# Blade.net
KiCad netlist of a schematic drawn in EAGLE
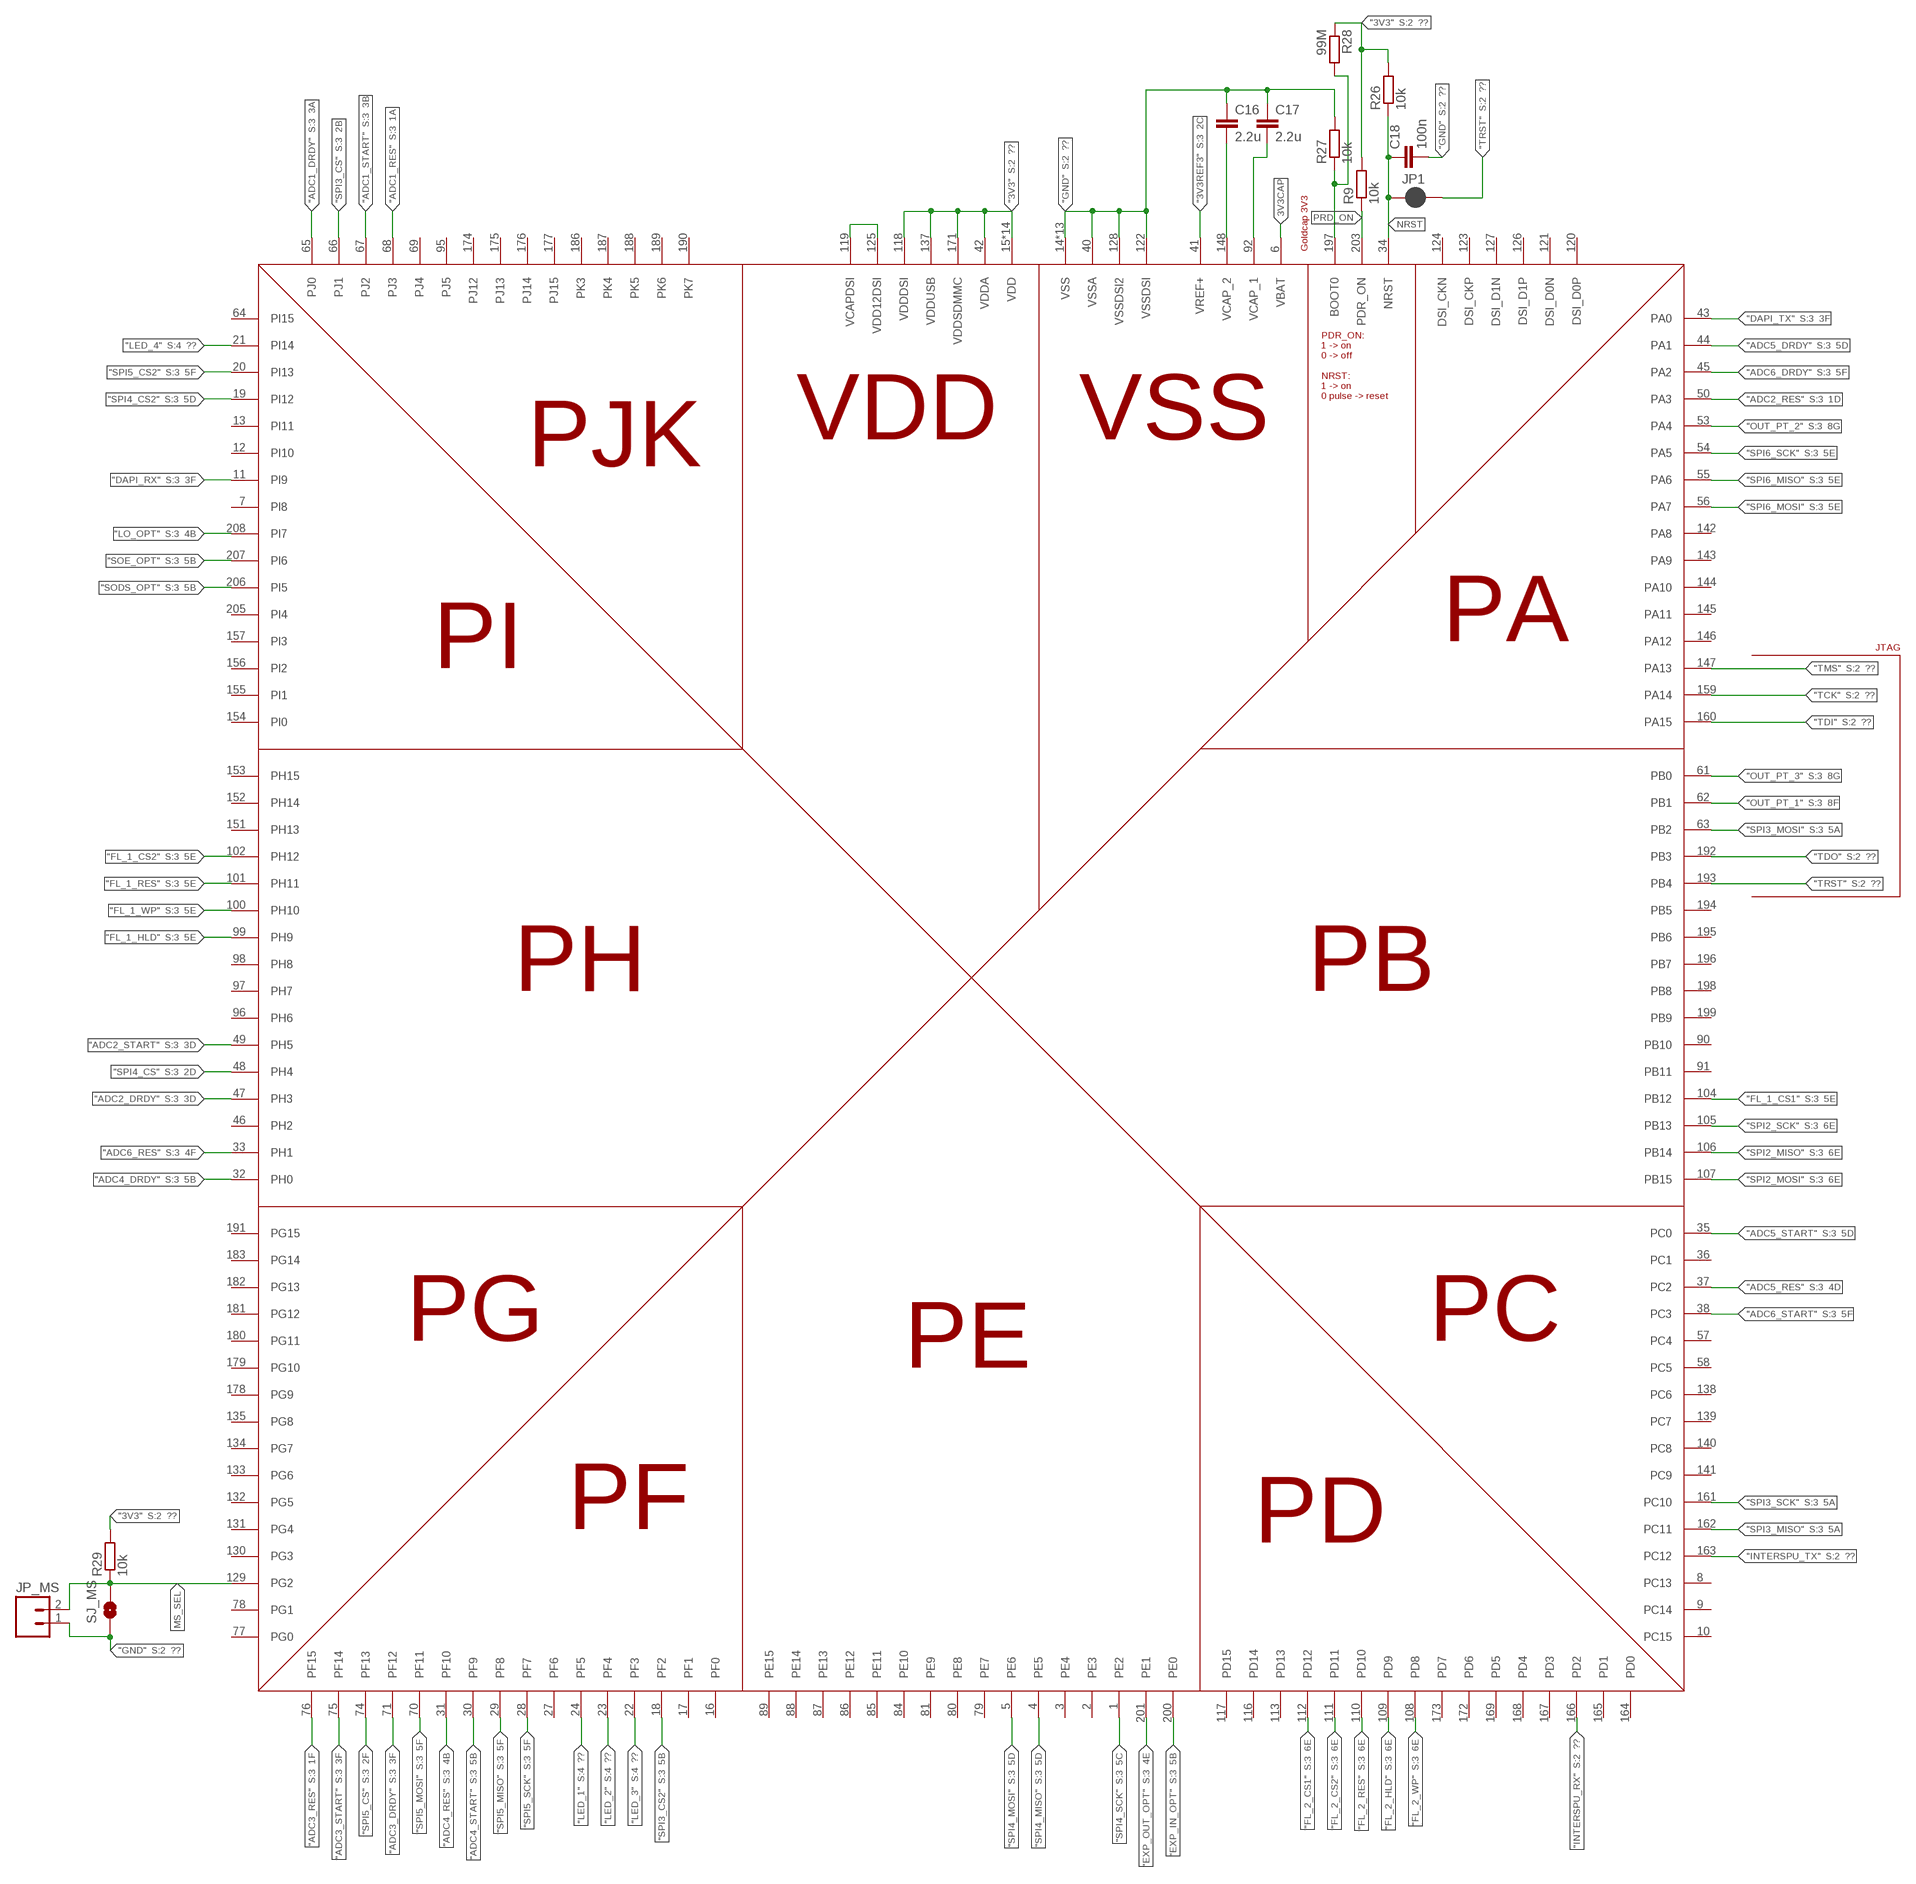
[diagram p0: schematic, sheet 1]
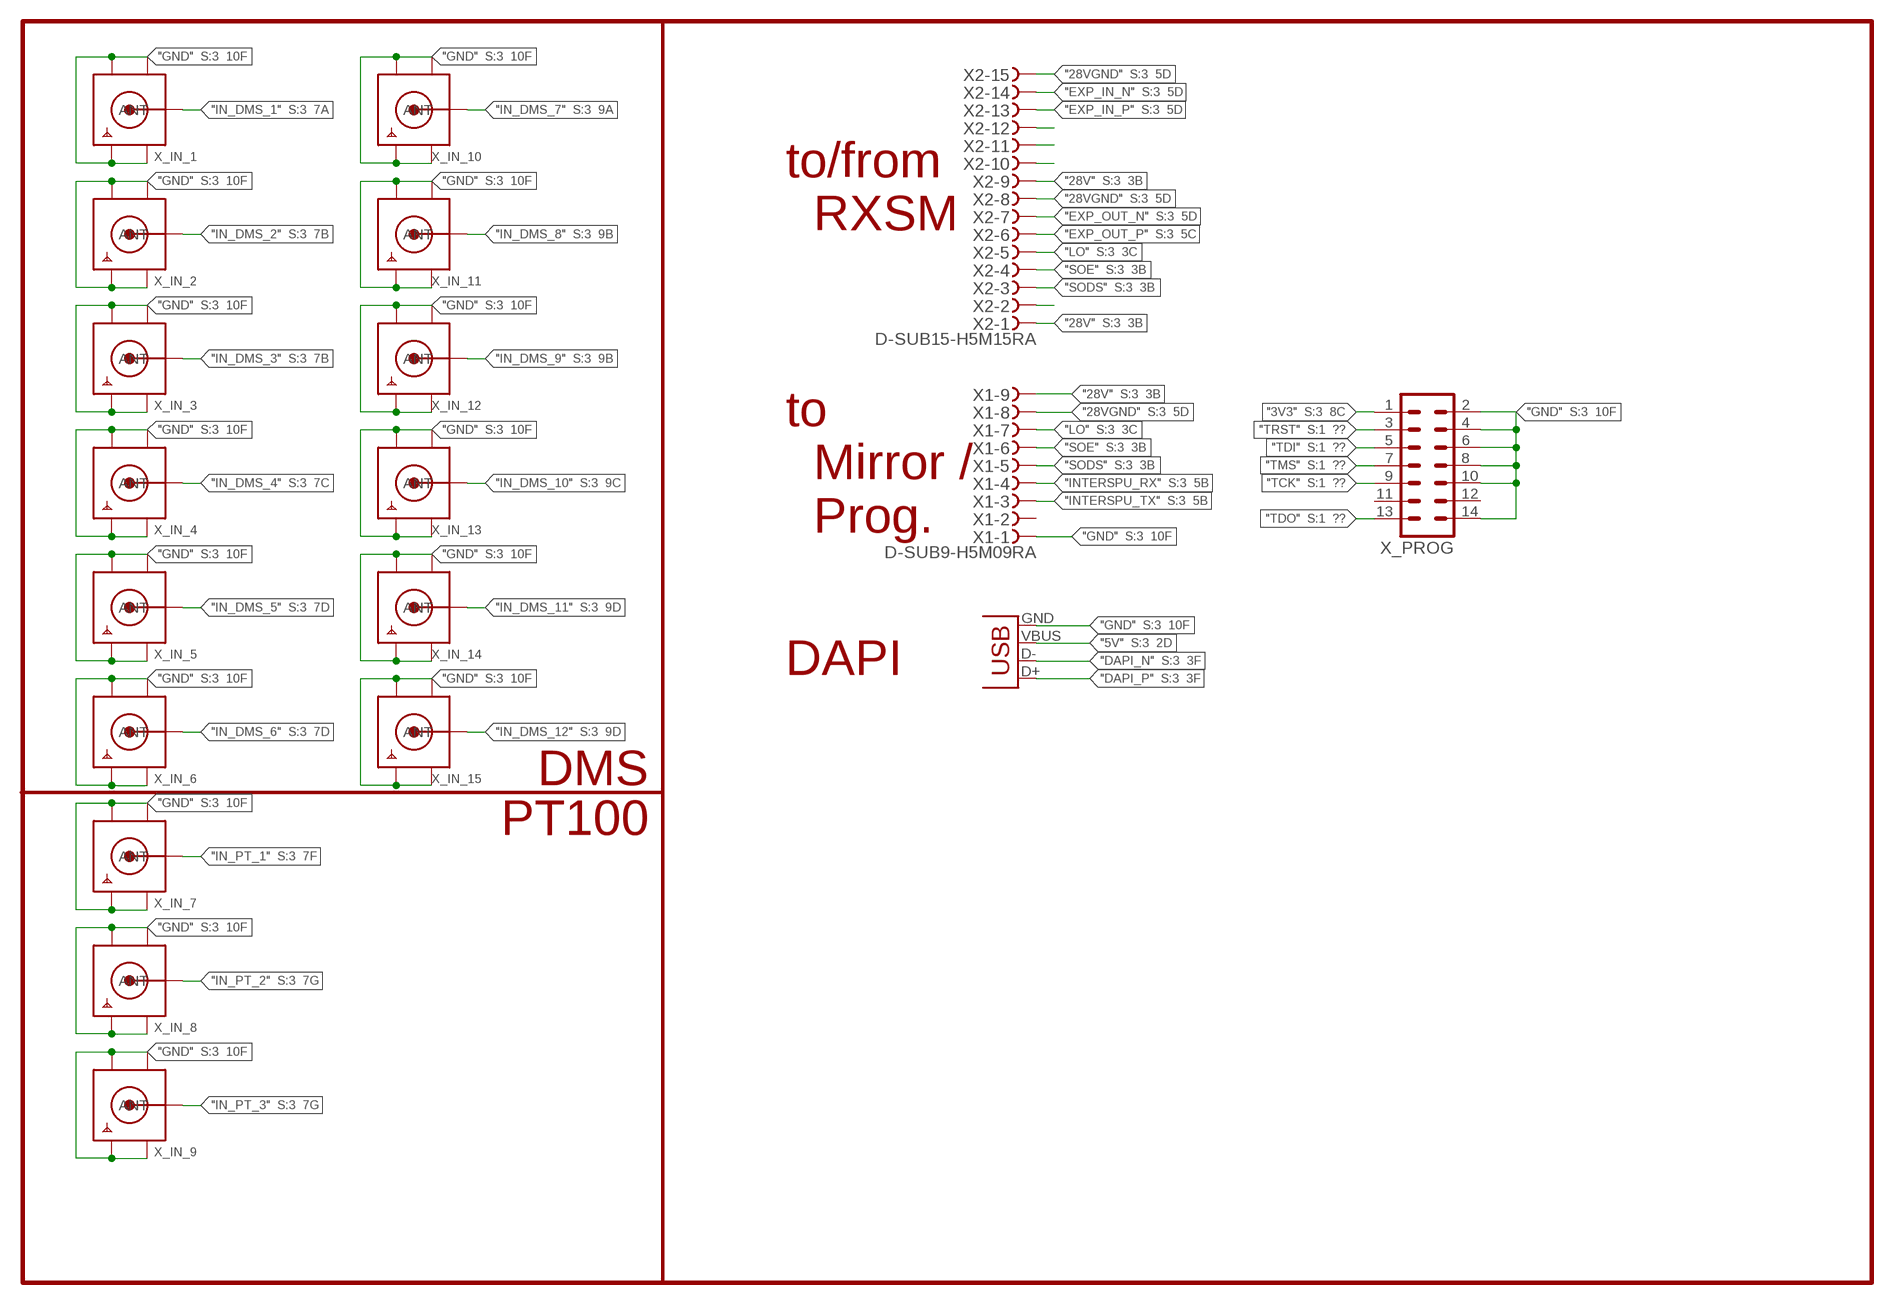
[diagram p1: schematic, sheet 2]
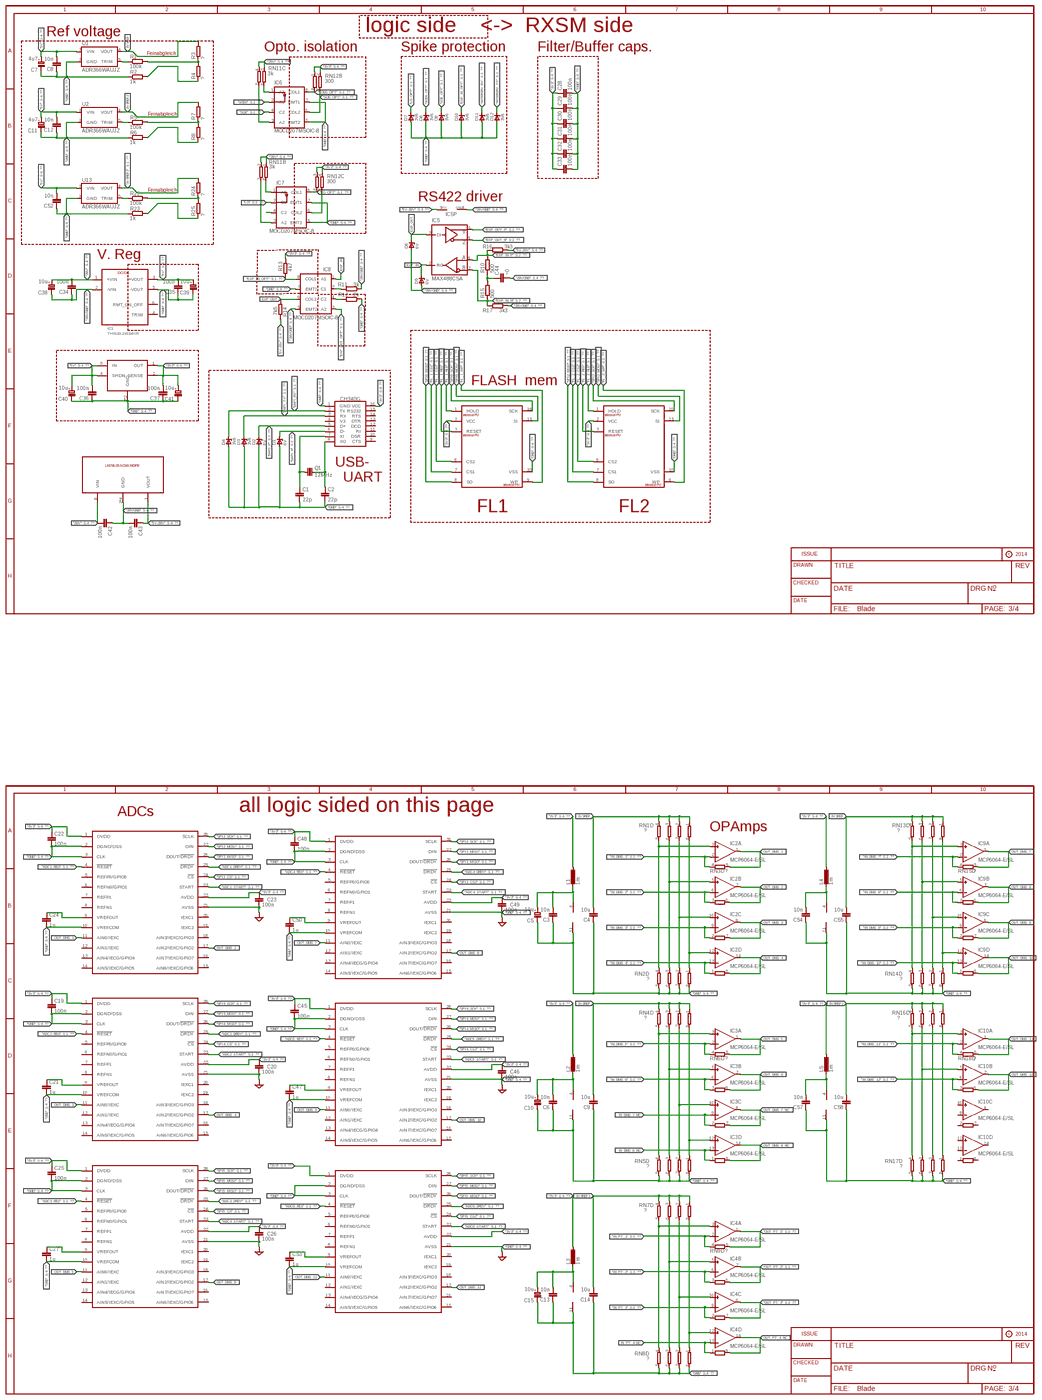
[diagram p2: schematic, sheet 3, overview]
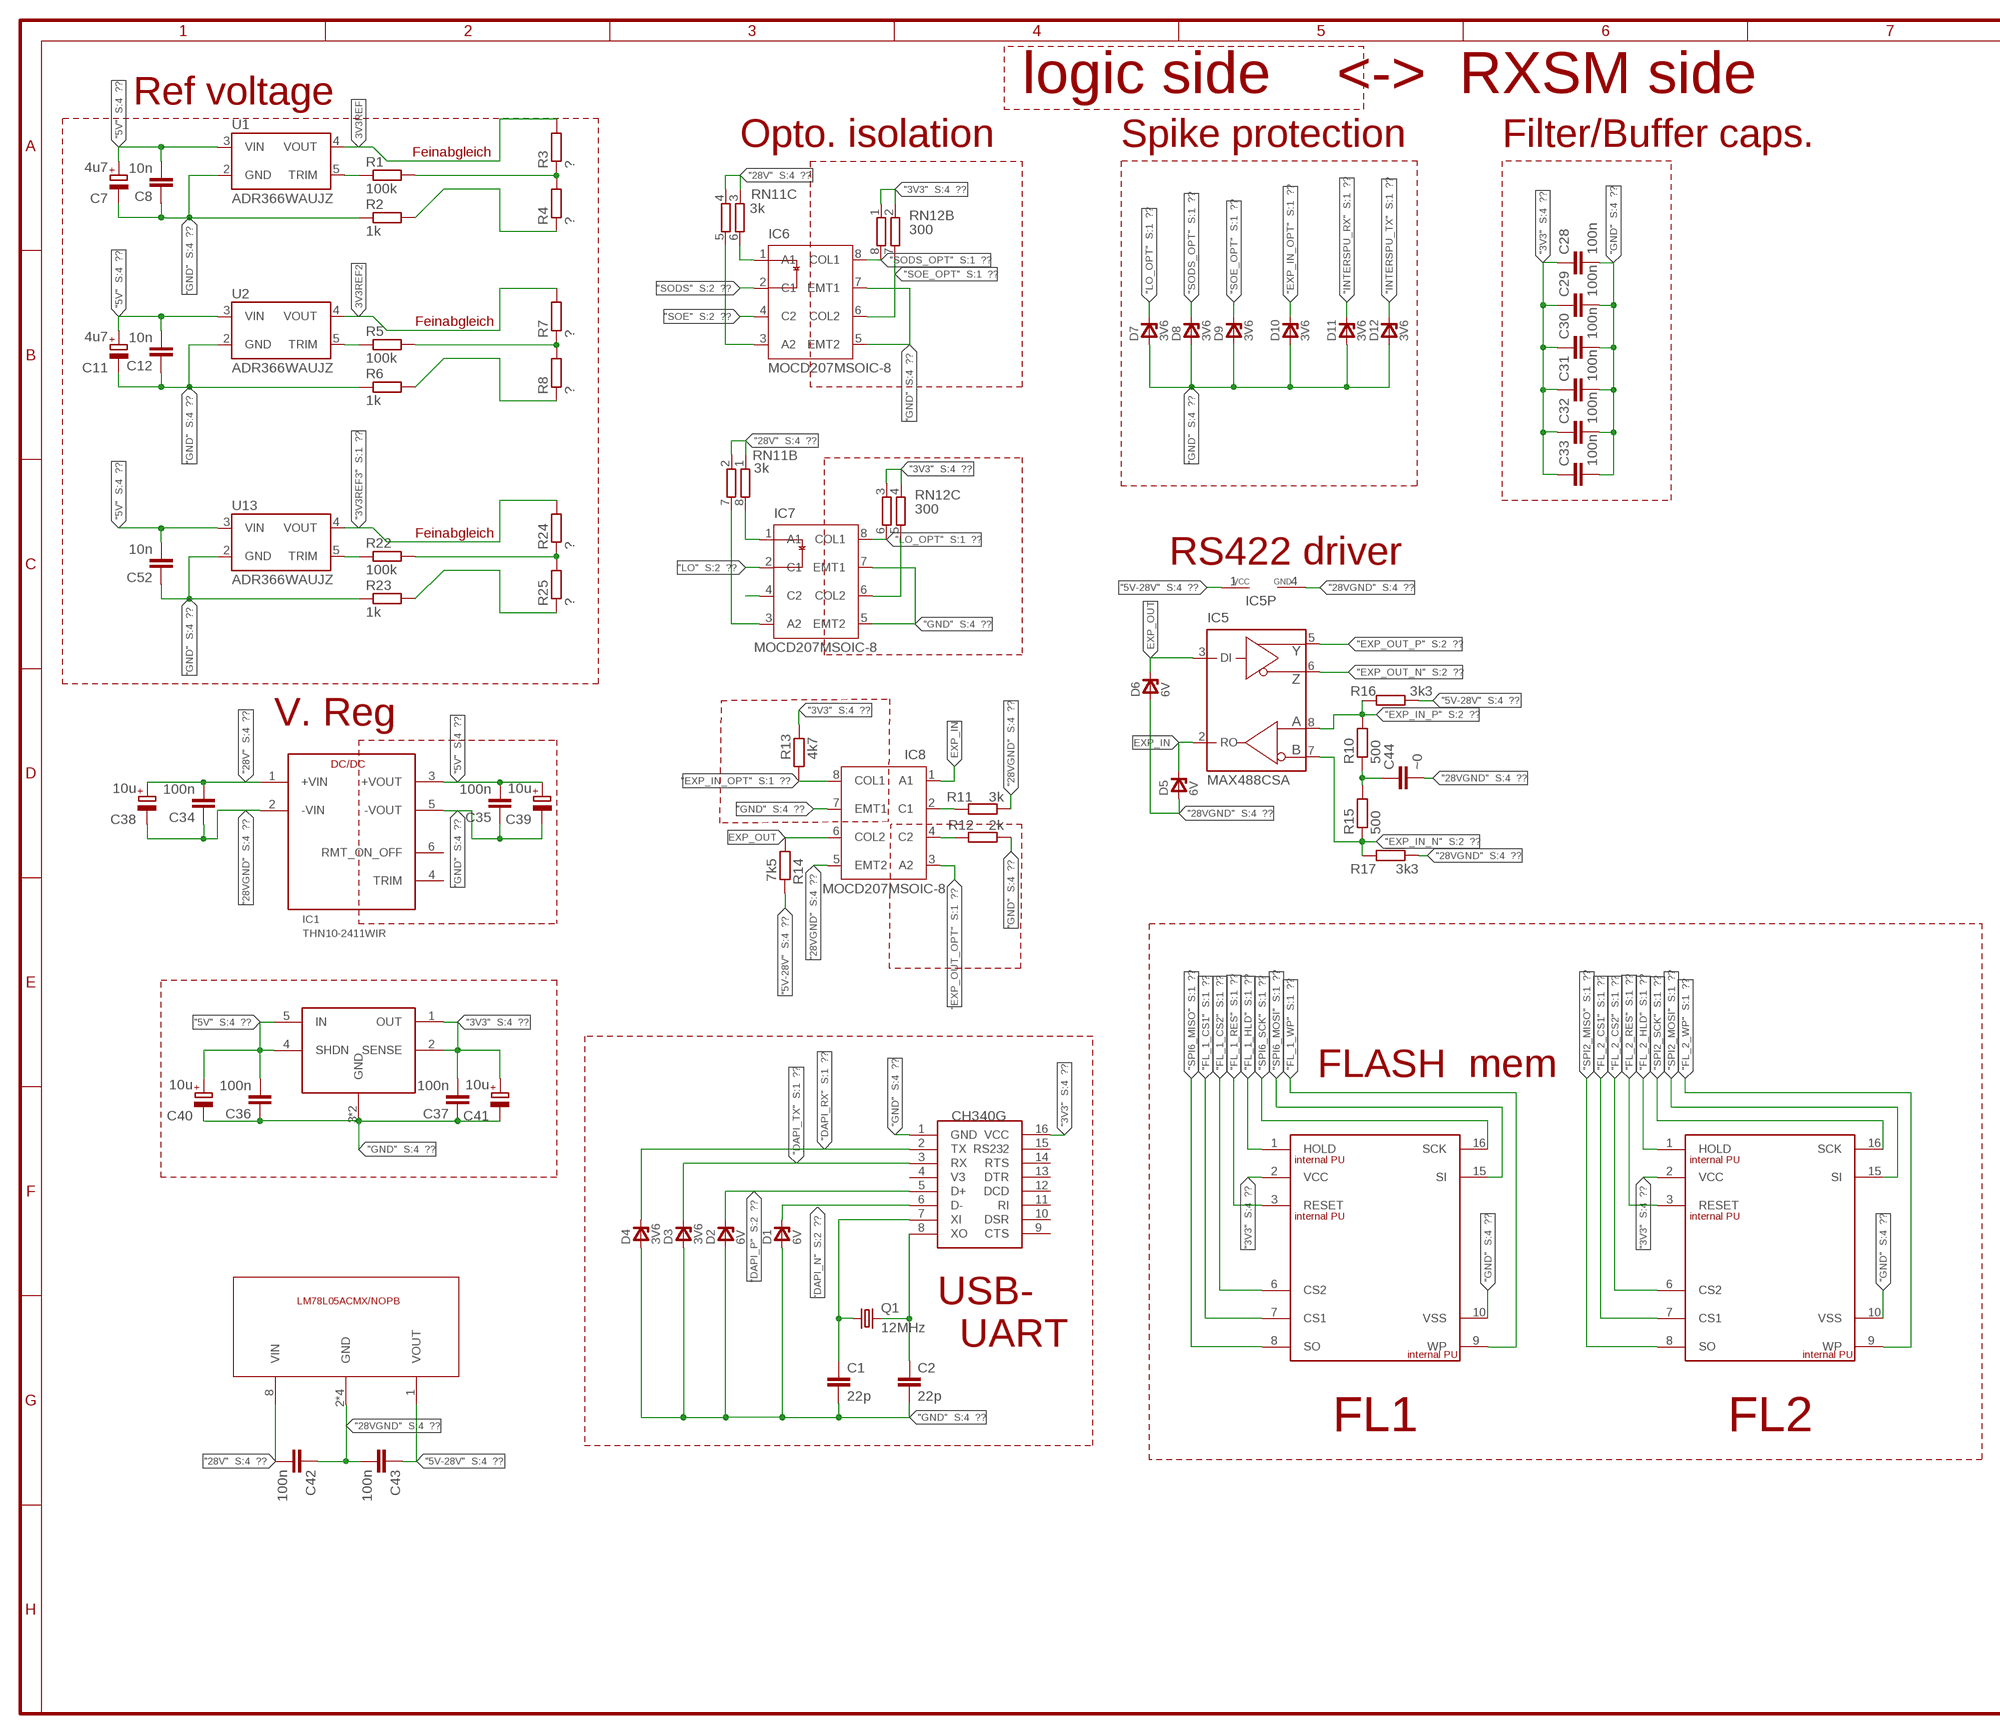
[diagram p3: schematic, sheet 3, part 1 of 4]
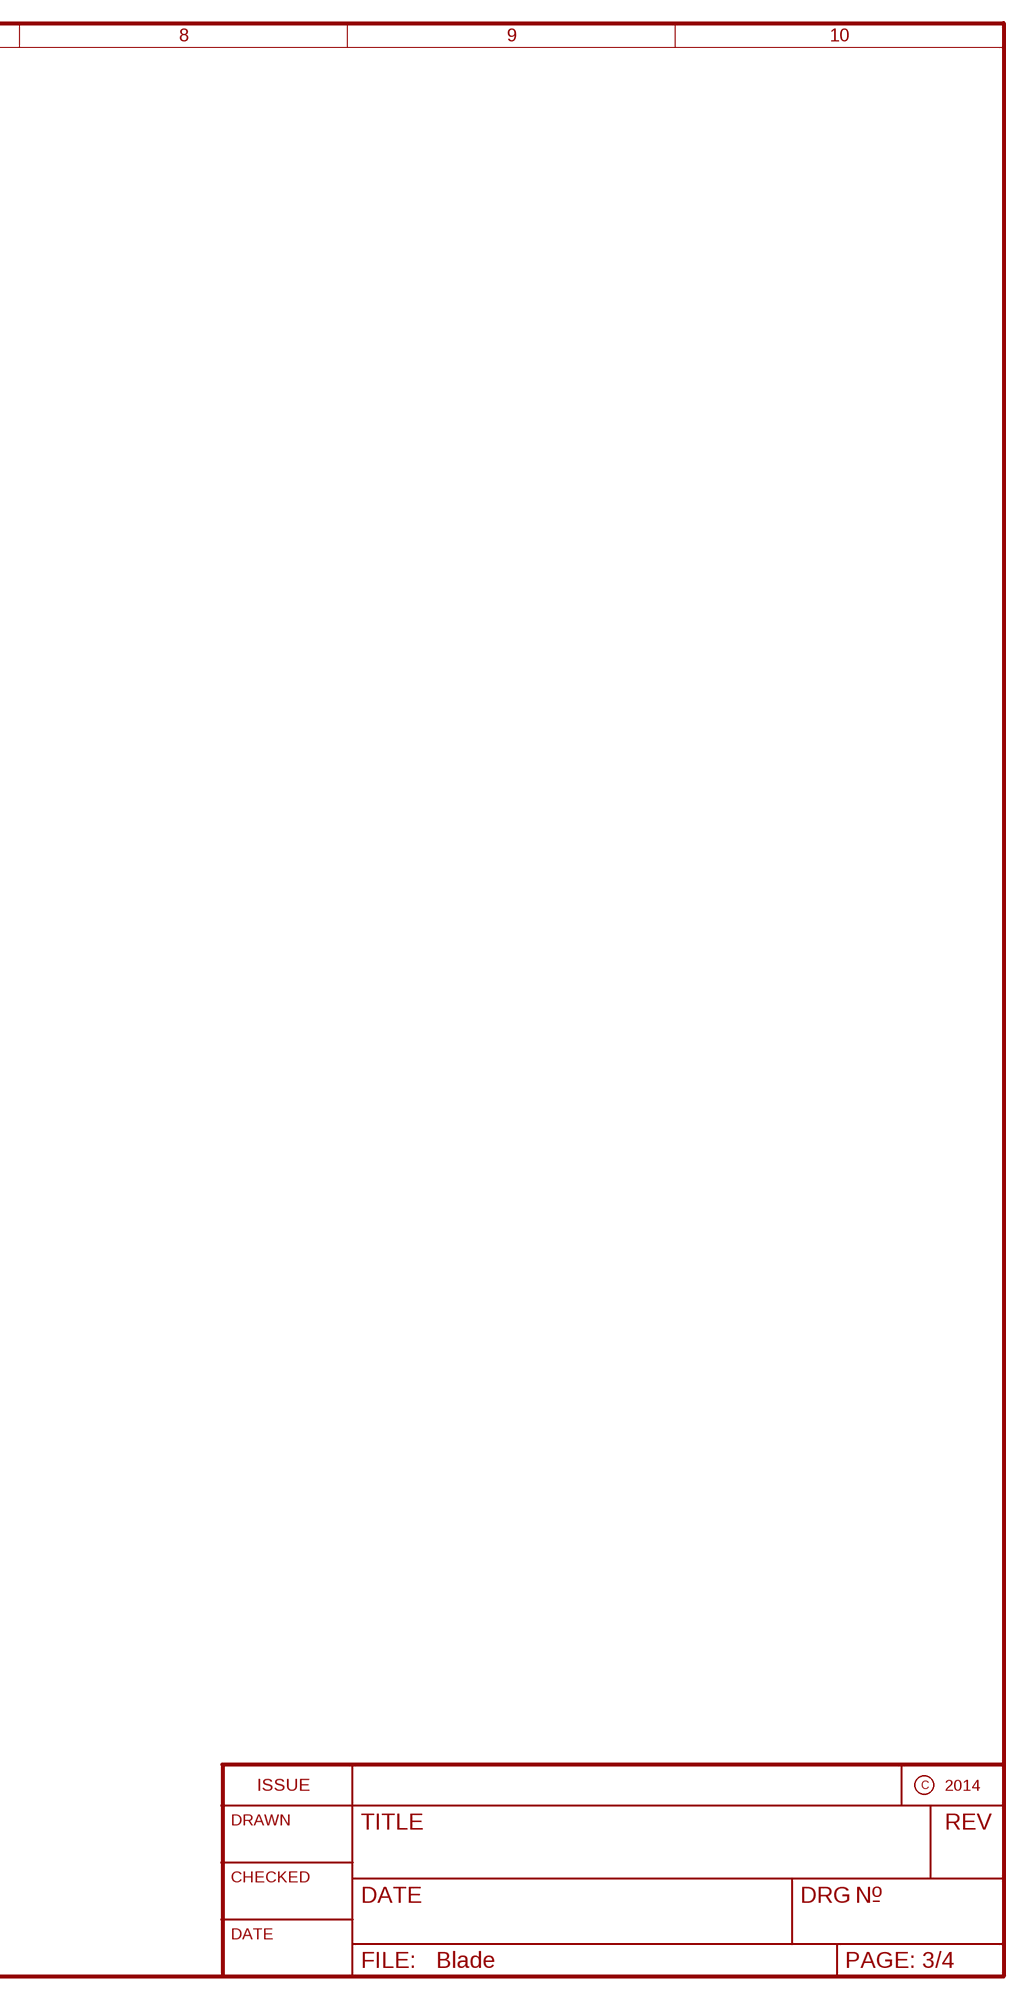
[diagram p4: schematic, sheet 3, part 2 of 4]
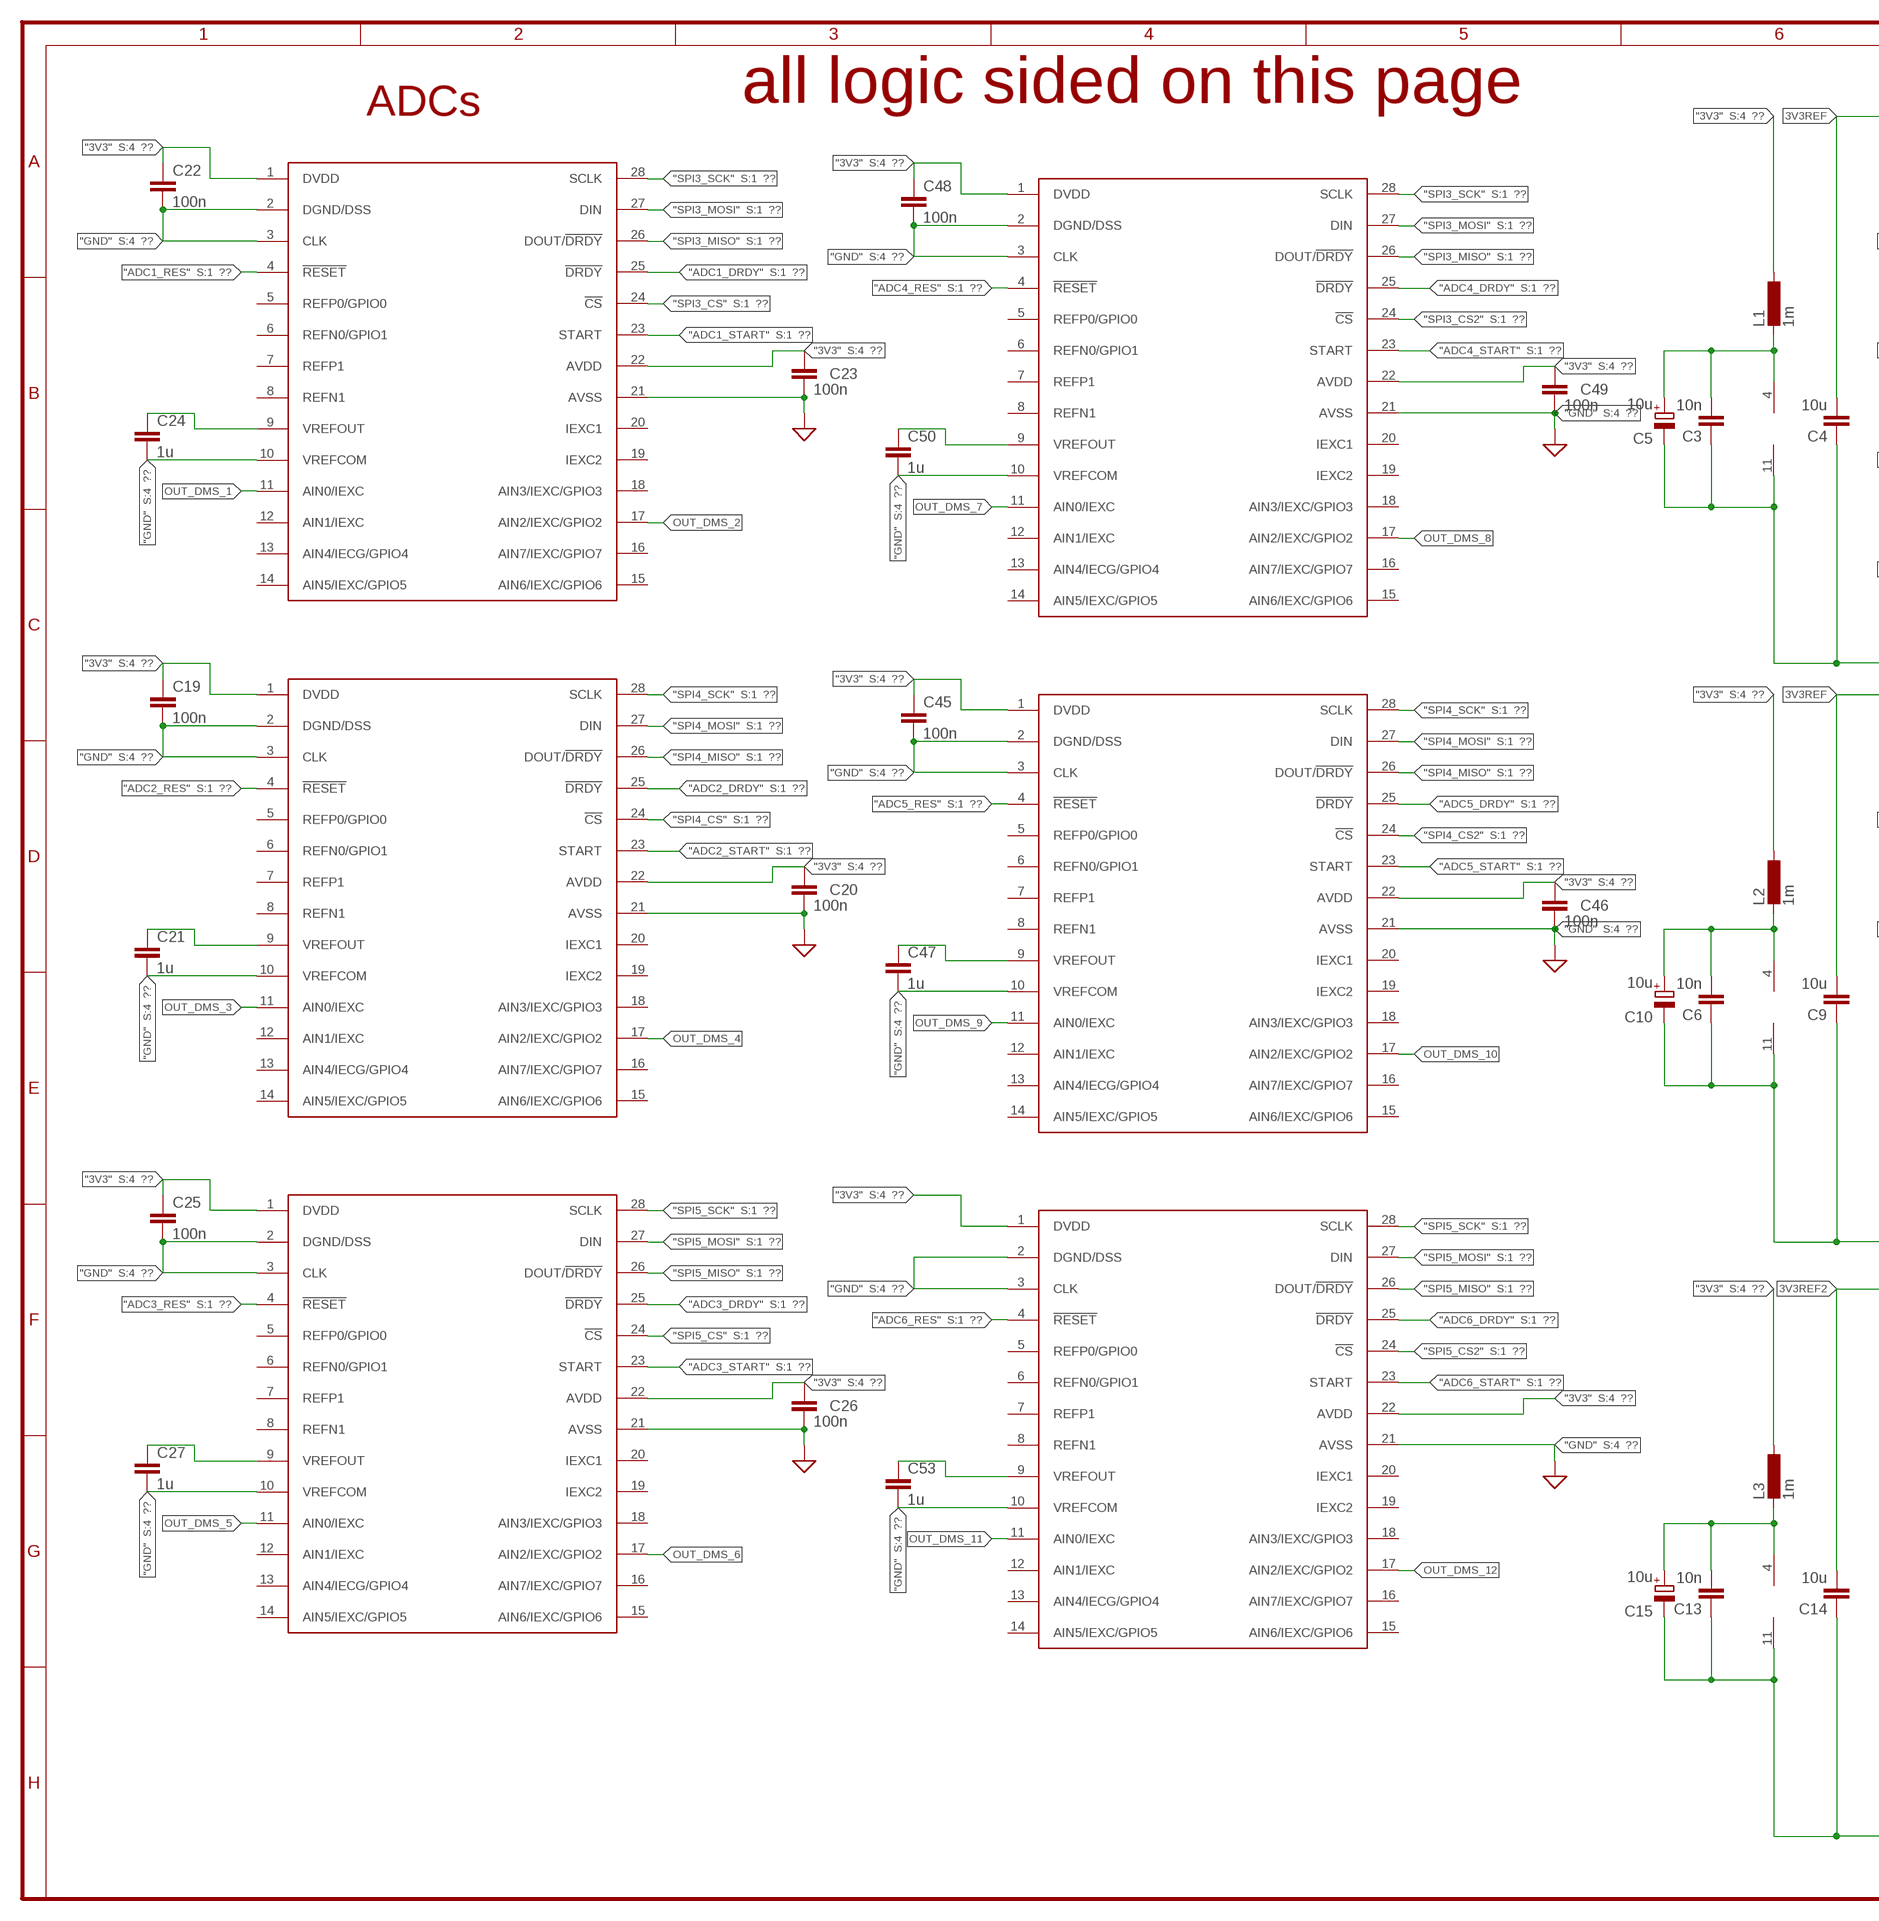
[diagram p5: schematic, sheet 3, part 3 of 4]
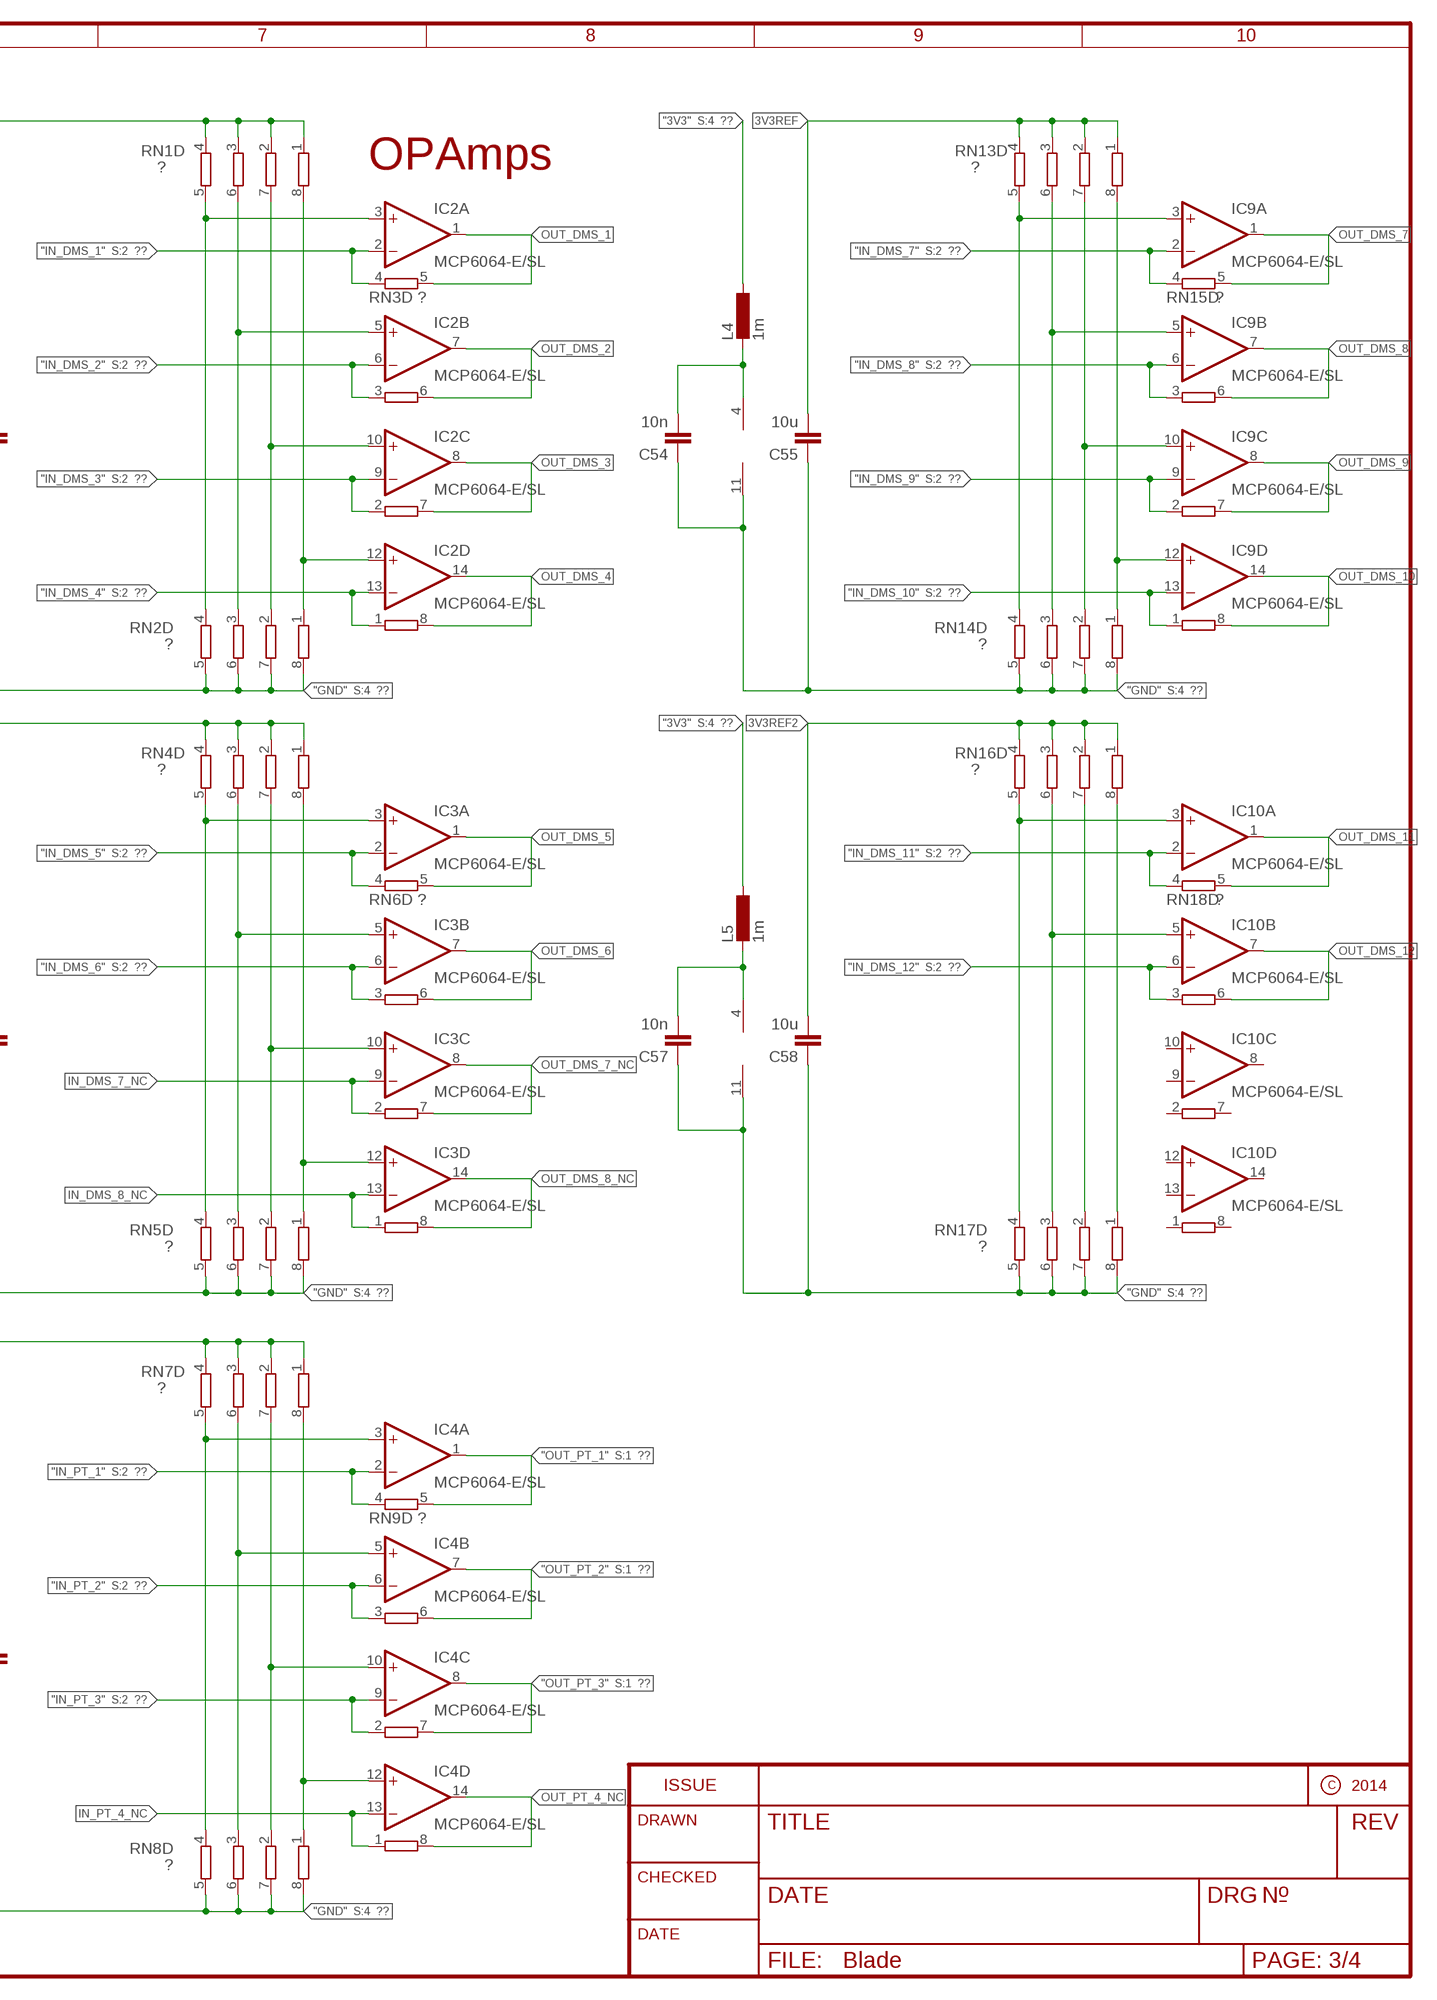
[diagram p6: schematic, sheet 3, part 4 of 4]
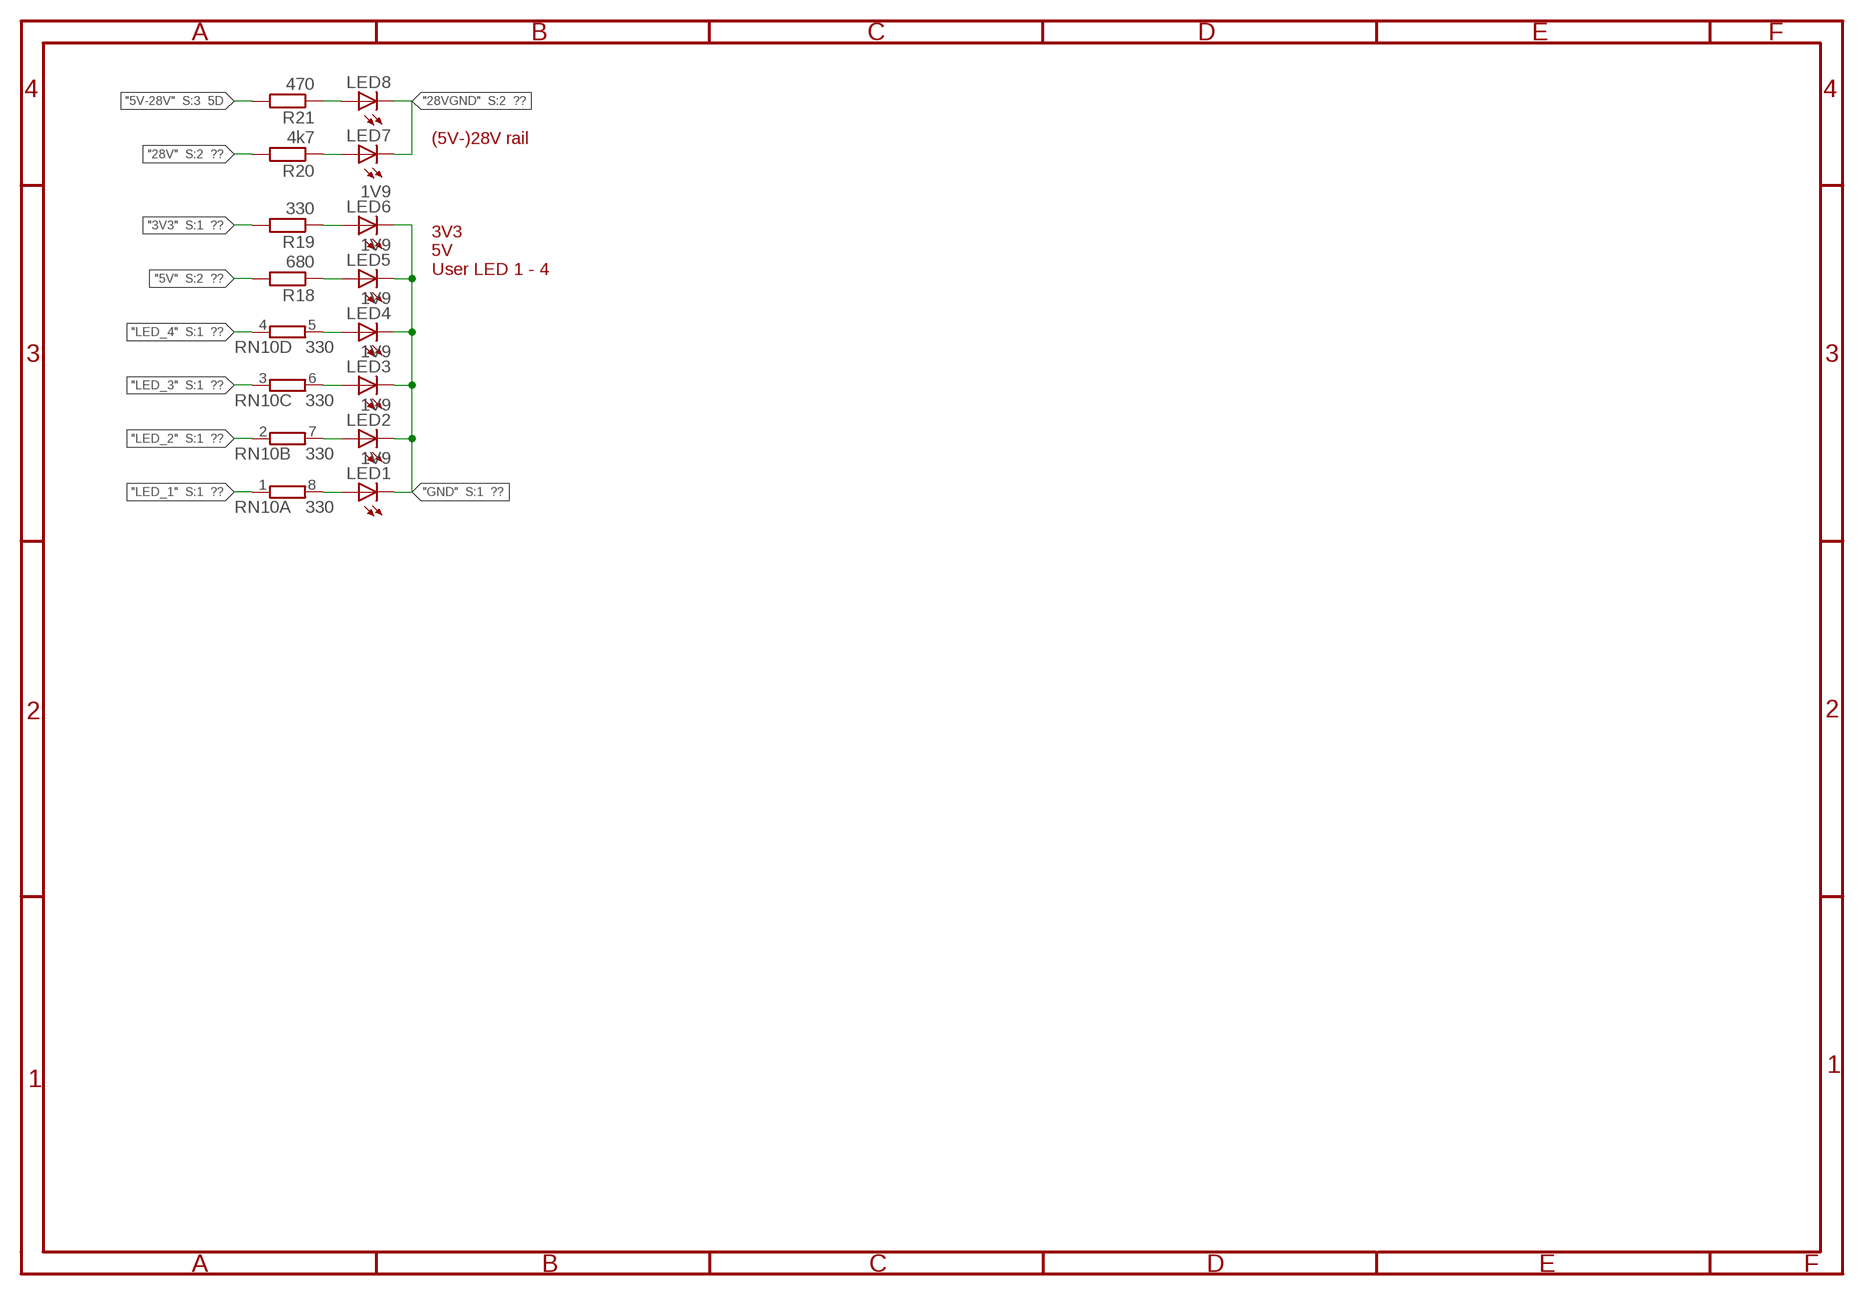
[diagram p7: schematic, sheet 4]

(export (version "E")
  (design (tool "Eeschema 10.0.6"))
  (components
    (comp (ref "LED1")
      (value "1V9")
      (footprint "eagle-import:CHIP-LED0603")
      (libsource (lib "eagle-import") (part "LEDCHIP-LED0603"))
    )
    (comp (ref "LED2")
      (value "1V9")
      (footprint "eagle-import:CHIP-LED0603")
      (libsource (lib "eagle-import") (part "LEDCHIP-LED0603"))
    )
    (comp (ref "LED3")
      (value "1V9")
      (footprint "eagle-import:CHIP-LED0603")
      (libsource (lib "eagle-import") (part "LEDCHIP-LED0603"))
    )
    (comp (ref "LED4")
      (value "1V9")
      (footprint "eagle-import:CHIP-LED0603")
      (libsource (lib "eagle-import") (part "LEDCHIP-LED0603"))
    )
    (comp (ref "LED5")
      (value "1V9")
      (footprint "eagle-import:CHIP-LED0603")
      (libsource (lib "eagle-import") (part "LEDCHIP-LED0603"))
    )
    (comp (ref "LED6")
      (value "1V9")
      (footprint "eagle-import:CHIP-LED0603")
      (libsource (lib "eagle-import") (part "LEDCHIP-LED0603"))
    )
    (comp (ref "LED7")
      (value "LEDCHIP-LED0603")
      (footprint "eagle-import:CHIP-LED0603")
      (libsource (lib "eagle-import") (part "LEDCHIP-LED0603"))
    )
    (comp (ref "LED8")
      (value "LEDCHIP-LED0603")
      (footprint "eagle-import:CHIP-LED0603")
      (libsource (lib "eagle-import") (part "LEDCHIP-LED0603"))
    )
    (comp (ref "R18")
      (value "680")
      (footprint "eagle-import:R0805")
      (libsource (lib "eagle-import") (part "rcl_334_R-EU_R0805"))
    )
    (comp (ref "R19")
      (value "330")
      (footprint "eagle-import:R0805")
      (libsource (lib "eagle-import") (part "rcl_334_R-EU_R0805"))
    )
    (comp (ref "R20")
      (value "4k7")
      (footprint "eagle-import:R0805")
      (libsource (lib "eagle-import") (part "rcl_334_R-EU_R0805"))
    )
    (comp (ref "R21")
      (value "470")
      (footprint "eagle-import:R0805")
      (libsource (lib "eagle-import") (part "rcl_334_R-EU_R0805"))
    )
    (comp (ref "RN10")
      (value "330")
      (footprint "eagle-import:EXBS8V")
      (libsource (lib "eagle-import") (part "4R-NEXBS8V"))
    )
    (comp (ref "X1")
      (value "D-SUB9-H5M09RA")
      (footprint "eagle-import:H5M09RA")
      (libsource (lib "eagle-import") (part "D-SUB9-H5M09RA"))
    )
    (comp (ref "X2")
      (value "D-SUB15-H5M15RA")
      (footprint "eagle-import:H5M15RA")
      (fields (field (name "MF") "TYCO ELECTRONICS") (field (name "MPN") "H5M15RA29C"))
      (libsource (lib "eagle-import") (part "D-SUB15-H5M15RA"))
    )
    (comp (ref "X3")
      (value "USBPTH")
      (footprint "eagle-import:USB-B-PTH")
      (libsource (lib "eagle-import") (part "USBPTH"))
    )
    (comp (ref "X_IN_1")
      (value "SMACONNECTOR_EDGE")
      (footprint "eagle-import:SMA_EDGELAUNCH")
      (libsource (lib "eagle-import") (part "SMACONNECTOR_EDGE"))
    )
    (comp (ref "X_IN_2")
      (value "SMACONNECTOR_EDGE")
      (footprint "eagle-import:SMA_EDGELAUNCH")
      (libsource (lib "eagle-import") (part "SMACONNECTOR_EDGE"))
    )
    (comp (ref "X_IN_3")
      (value "SMACONNECTOR_EDGE")
      (footprint "eagle-import:SMA_EDGELAUNCH")
      (libsource (lib "eagle-import") (part "SMACONNECTOR_EDGE"))
    )
    (comp (ref "X_IN_4")
      (value "SMACONNECTOR_EDGE")
      (footprint "eagle-import:SMA_EDGELAUNCH")
      (libsource (lib "eagle-import") (part "SMACONNECTOR_EDGE"))
    )
    (comp (ref "X_IN_5")
      (value "SMACONNECTOR_EDGE")
      (footprint "eagle-import:SMA_EDGELAUNCH")
      (libsource (lib "eagle-import") (part "SMACONNECTOR_EDGE"))
    )
    (comp (ref "X_IN_6")
      (value "SMACONNECTOR_EDGE")
      (footprint "eagle-import:SMA_EDGELAUNCH")
      (libsource (lib "eagle-import") (part "SMACONNECTOR_EDGE"))
    )
    (comp (ref "X_IN_7")
      (value "SMACONNECTOR_EDGE")
      (footprint "eagle-import:SMA_EDGELAUNCH")
      (libsource (lib "eagle-import") (part "SMACONNECTOR_EDGE"))
    )
    (comp (ref "X_IN_8")
      (value "SMACONNECTOR_EDGE")
      (footprint "eagle-import:SMA_EDGELAUNCH")
      (libsource (lib "eagle-import") (part "SMACONNECTOR_EDGE"))
    )
    (comp (ref "X_IN_9")
      (value "SMACONNECTOR_EDGE")
      (footprint "eagle-import:SMA_EDGELAUNCH")
      (libsource (lib "eagle-import") (part "SMACONNECTOR_EDGE"))
    )
    (comp (ref "X_IN_10")
      (value "SMACONNECTOR_EDGE")
      (footprint "eagle-import:SMA_EDGELAUNCH")
      (libsource (lib "eagle-import") (part "SMACONNECTOR_EDGE"))
    )
    (comp (ref "X_IN_11")
      (value "SMACONNECTOR_EDGE")
      (footprint "eagle-import:SMA_EDGELAUNCH")
      (libsource (lib "eagle-import") (part "SMACONNECTOR_EDGE"))
    )
    (comp (ref "X_IN_12")
      (value "SMACONNECTOR_EDGE")
      (footprint "eagle-import:SMA_EDGELAUNCH")
      (libsource (lib "eagle-import") (part "SMACONNECTOR_EDGE"))
    )
    (comp (ref "X_IN_13")
      (value "SMACONNECTOR_EDGE")
      (footprint "eagle-import:SMA_EDGELAUNCH")
      (libsource (lib "eagle-import") (part "SMACONNECTOR_EDGE"))
    )
    (comp (ref "X_IN_14")
      (value "SMACONNECTOR_EDGE")
      (footprint "eagle-import:SMA_EDGELAUNCH")
      (libsource (lib "eagle-import") (part "SMACONNECTOR_EDGE"))
    )
    (comp (ref "X_IN_15")
      (value "SMACONNECTOR_EDGE")
      (footprint "eagle-import:SMA_EDGELAUNCH")
      (libsource (lib "eagle-import") (part "SMACONNECTOR_EDGE"))
    )
    (comp (ref "X_PROG")
      (value "MA07-2")
      (footprint "eagle-import:MA07-2")
      (libsource (lib "eagle-import") (part "MA07-2"))
    )
    (comp (ref "C16")
      (value "2.2u")
      (footprint "eagle-import:C1206")
      (libsource (lib "eagle-import") (part "rcl_334_C-EUC1206"))
    )
    (comp (ref "C17")
      (value "2.2u")
      (footprint "eagle-import:C1206")
      (libsource (lib "eagle-import") (part "rcl_334_C-EUC1206"))
    )
    (comp (ref "C18")
      (value "100n")
      (footprint "eagle-import:0603-CAP")
      (libsource (lib "eagle-import") (part "CAP0603-CAP"))
    )
    (comp (ref "JP1")
      (value "JUMPER-SMT_2_NC_PASTE_SILK")
      (footprint "eagle-import:SMT-JUMPER_2_NC_PASTE_SILK")
      (libsource (lib "eagle-import") (part "JUMPER-SMT_2_NC_PASTE_SILK"))
    )
    (comp (ref "JP_MS")
      (value "M02PTH")
      (footprint "eagle-import:1X02")
      (libsource (lib "eagle-import") (part "M02PTH"))
    )
    (comp (ref "R9")
      (value "10k")
      (footprint "eagle-import:R0805")
      (libsource (lib "eagle-import") (part "rcl_334_R-EU_R0805"))
    )
    (comp (ref "R26")
      (value "10k")
      (footprint "eagle-import:R0805")
      (libsource (lib "eagle-import") (part "rcl_334_R-EU_R0805"))
    )
    (comp (ref "R27")
      (value "10k")
      (footprint "eagle-import:R0805")
      (libsource (lib "eagle-import") (part "rcl_334_R-EU_R0805"))
    )
    (comp (ref "R28")
      (value "99M")
      (footprint "eagle-import:R0805")
      (libsource (lib "eagle-import") (part "rcl_334_R-EU_R0805"))
    )
    (comp (ref "R29")
      (value "10k")
      (footprint "eagle-import:R0805")
      (libsource (lib "eagle-import") (part "rcl_334_R-EU_R0805"))
    )
    (comp (ref "SJ_MS")
      (value "SOLDERJUMPERNO")
      (footprint "eagle-import:SJ_2S-NO")
      (libsource (lib "eagle-import") (part "SOLDERJUMPERNO"))
    )
    (comp (ref "U9")
      (value "STM32F77XXXLQFP208")
      (footprint "eagle-import:QFP50P3060X3060X385-208")
      (libsource (lib "eagle-import") (part "STM32F77XXXLQFP208"))
    )
    (comp (ref "C1")
      (value "22p")
      (footprint "eagle-import:C0603")
      (libsource (lib "eagle-import") (part "C-EUC0603"))
    )
    (comp (ref "C2")
      (value "22p")
      (footprint "eagle-import:C0603")
      (libsource (lib "eagle-import") (part "C-EUC0603"))
    )
    (comp (ref "C3")
      (value "10n")
      (footprint "eagle-import:C0805")
      (libsource (lib "eagle-import") (part "rcl_334_C-EUC0805"))
    )
    (comp (ref "C4")
      (value "10u")
      (footprint "eagle-import:C0805")
      (libsource (lib "eagle-import") (part "rcl_334_C-EUC0805"))
    )
    (comp (ref "C5")
      (value "10u")
      (footprint "eagle-import:153CLV-0810")
      (libsource (lib "eagle-import") (part "CPOL-EU153CLV-0810"))
    )
    (comp (ref "C6")
      (value "10n")
      (footprint "eagle-import:C0805")
      (libsource (lib "eagle-import") (part "rcl_334_C-EUC0805"))
    )
    (comp (ref "C7")
      (value "4u7")
      (footprint "eagle-import:153CLV-0810")
      (libsource (lib "eagle-import") (part "CPOL-EU153CLV-0810"))
    )
    (comp (ref "C8")
      (value "10n")
      (footprint "eagle-import:C0805")
      (libsource (lib "eagle-import") (part "rcl_334_C-EUC0805"))
    )
    (comp (ref "C9")
      (value "10u")
      (footprint "eagle-import:C0805")
      (libsource (lib "eagle-import") (part "rcl_334_C-EUC0805"))
    )
    (comp (ref "C10")
      (value "10u")
      (footprint "eagle-import:153CLV-0810")
      (libsource (lib "eagle-import") (part "CPOL-EU153CLV-0810"))
    )
    (comp (ref "C11")
      (value "4u7")
      (footprint "eagle-import:153CLV-0810")
      (libsource (lib "eagle-import") (part "CPOL-EU153CLV-0810"))
    )
    (comp (ref "C12")
      (value "10n")
      (footprint "eagle-import:C0805")
      (libsource (lib "eagle-import") (part "rcl_334_C-EUC0805"))
    )
    (comp (ref "C13")
      (value "10n")
      (footprint "eagle-import:C0805")
      (libsource (lib "eagle-import") (part "rcl_334_C-EUC0805"))
    )
    (comp (ref "C14")
      (value "10u")
      (footprint "eagle-import:C0805")
      (libsource (lib "eagle-import") (part "rcl_334_C-EUC0805"))
    )
    (comp (ref "C15")
      (value "10u")
      (footprint "eagle-import:153CLV-0810")
      (libsource (lib "eagle-import") (part "CPOL-EU153CLV-0810"))
    )
    (comp (ref "C19")
      (value "100n")
      (footprint "eagle-import:C0805")
      (libsource (lib "eagle-import") (part "rcl_334_C-EUC0805"))
    )
    (comp (ref "C20")
      (value "100n")
      (footprint "eagle-import:C0805")
      (libsource (lib "eagle-import") (part "rcl_334_C-EUC0805"))
    )
    (comp (ref "C21")
      (value "1u")
      (footprint "eagle-import:C0805")
      (libsource (lib "eagle-import") (part "rcl_334_C-EUC0805"))
    )
    (comp (ref "C22")
      (value "100n")
      (footprint "eagle-import:C0805")
      (libsource (lib "eagle-import") (part "rcl_334_C-EUC0805"))
    )
    (comp (ref "C23")
      (value "100n")
      (footprint "eagle-import:C0805")
      (libsource (lib "eagle-import") (part "rcl_334_C-EUC0805"))
    )
    (comp (ref "C24")
      (value "1u")
      (footprint "eagle-import:C0805")
      (libsource (lib "eagle-import") (part "rcl_334_C-EUC0805"))
    )
    (comp (ref "C25")
      (value "100n")
      (footprint "eagle-import:C0805")
      (libsource (lib "eagle-import") (part "rcl_334_C-EUC0805"))
    )
    (comp (ref "C26")
      (value "100n")
      (footprint "eagle-import:C0805")
      (libsource (lib "eagle-import") (part "rcl_334_C-EUC0805"))
    )
    (comp (ref "C27")
      (value "1u")
      (footprint "eagle-import:C0805")
      (libsource (lib "eagle-import") (part "rcl_334_C-EUC0805"))
    )
    (comp (ref "C28")
      (value "100n")
      (footprint "eagle-import:C0805")
      (libsource (lib "eagle-import") (part "rcl_334_C-EUC0805"))
    )
    (comp (ref "C29")
      (value "100n")
      (footprint "eagle-import:C0805")
      (libsource (lib "eagle-import") (part "rcl_334_C-EUC0805"))
    )
    (comp (ref "C30")
      (value "100n")
      (footprint "eagle-import:C0805")
      (libsource (lib "eagle-import") (part "rcl_334_C-EUC0805"))
    )
    (comp (ref "C31")
      (value "100n")
      (footprint "eagle-import:C0805")
      (libsource (lib "eagle-import") (part "rcl_334_C-EUC0805"))
    )
    (comp (ref "C32")
      (value "100n")
      (footprint "eagle-import:C0805")
      (libsource (lib "eagle-import") (part "rcl_334_C-EUC0805"))
    )
    (comp (ref "C33")
      (value "100n")
      (footprint "eagle-import:C0805")
      (libsource (lib "eagle-import") (part "rcl_334_C-EUC0805"))
    )
    (comp (ref "C34")
      (value "100n")
      (footprint "eagle-import:C0805")
      (libsource (lib "eagle-import") (part "rcl_334_C-EUC0805"))
    )
    (comp (ref "C35")
      (value "100n")
      (footprint "eagle-import:C0805")
      (libsource (lib "eagle-import") (part "rcl_334_C-EUC0805"))
    )
    (comp (ref "C36")
      (value "100n")
      (footprint "eagle-import:C0805")
      (libsource (lib "eagle-import") (part "rcl_334_C-EUC0805"))
    )
    (comp (ref "C37")
      (value "100n")
      (footprint "eagle-import:C0805")
      (libsource (lib "eagle-import") (part "rcl_334_C-EUC0805"))
    )
    (comp (ref "C38")
      (value "10u")
      (footprint "eagle-import:153CLV-0810")
      (libsource (lib "eagle-import") (part "CPOL-EU153CLV-0810"))
    )
    (comp (ref "C39")
      (value "10u")
      (footprint "eagle-import:153CLV-0810")
      (libsource (lib "eagle-import") (part "CPOL-EU153CLV-0810"))
    )
    (comp (ref "C40")
      (value "10u")
      (footprint "eagle-import:153CLV-0810")
      (libsource (lib "eagle-import") (part "CPOL-EU153CLV-0810"))
    )
    (comp (ref "C41")
      (value "10u")
      (footprint "eagle-import:153CLV-0810")
      (libsource (lib "eagle-import") (part "CPOL-EU153CLV-0810"))
    )
    (comp (ref "C42")
      (value "100n")
      (footprint "eagle-import:C0805")
      (libsource (lib "eagle-import") (part "rcl_334_C-EUC0805"))
    )
    (comp (ref "C43")
      (value "100n")
      (footprint "eagle-import:C0805")
      (libsource (lib "eagle-import") (part "rcl_334_C-EUC0805"))
    )
    (comp (ref "C44")
      (value "~0")
      (footprint "eagle-import:C0805")
      (libsource (lib "eagle-import") (part "rcl_334_C-EUC0805"))
    )
    (comp (ref "C45")
      (value "100n")
      (footprint "eagle-import:C0805")
      (libsource (lib "eagle-import") (part "rcl_334_C-EUC0805"))
    )
    (comp (ref "C46")
      (value "100n")
      (footprint "eagle-import:C0805")
      (libsource (lib "eagle-import") (part "rcl_334_C-EUC0805"))
    )
    (comp (ref "C47")
      (value "1u")
      (footprint "eagle-import:C0805")
      (libsource (lib "eagle-import") (part "rcl_334_C-EUC0805"))
    )
    (comp (ref "C48")
      (value "100n")
      (footprint "eagle-import:C0805")
      (libsource (lib "eagle-import") (part "rcl_334_C-EUC0805"))
    )
    (comp (ref "C49")
      (value "100n")
      (footprint "eagle-import:C0805")
      (libsource (lib "eagle-import") (part "rcl_334_C-EUC0805"))
    )
    (comp (ref "C50")
      (value "1u")
      (footprint "eagle-import:C0805")
      (libsource (lib "eagle-import") (part "rcl_334_C-EUC0805"))
    )
    (comp (ref "C52")
      (value "10n")
      (footprint "eagle-import:C0805")
      (libsource (lib "eagle-import") (part "rcl_334_C-EUC0805"))
    )
    (comp (ref "C53")
      (value "1u")
      (footprint "eagle-import:C0805")
      (libsource (lib "eagle-import") (part "rcl_334_C-EUC0805"))
    )
    (comp (ref "C54")
      (value "10n")
      (footprint "eagle-import:C0805")
      (libsource (lib "eagle-import") (part "rcl_334_C-EUC0805"))
    )
    (comp (ref "C55")
      (value "10u")
      (footprint "eagle-import:C0805")
      (libsource (lib "eagle-import") (part "rcl_334_C-EUC0805"))
    )
    (comp (ref "C57")
      (value "10n")
      (footprint "eagle-import:C0805")
      (libsource (lib "eagle-import") (part "rcl_334_C-EUC0805"))
    )
    (comp (ref "C58")
      (value "10u")
      (footprint "eagle-import:C0805")
      (libsource (lib "eagle-import") (part "rcl_334_C-EUC0805"))
    )
    (comp (ref "D1")
      (value "6V")
      (footprint "eagle-import:DMELF")
      (libsource (lib "eagle-import") (part "DZMELF"))
    )
    (comp (ref "D2")
      (value "6V")
      (footprint "eagle-import:DMELF")
      (libsource (lib "eagle-import") (part "DZMELF"))
    )
    (comp (ref "D3")
      (value "3V6")
      (footprint "eagle-import:DMELF")
      (libsource (lib "eagle-import") (part "DZMELF"))
    )
    (comp (ref "D4")
      (value "3V6")
      (footprint "eagle-import:DMELF")
      (libsource (lib "eagle-import") (part "DZMELF"))
    )
    (comp (ref "D5")
      (value "6V")
      (footprint "eagle-import:DMELF")
      (libsource (lib "eagle-import") (part "DZMELF"))
    )
    (comp (ref "D6")
      (value "6V")
      (footprint "eagle-import:DMELF")
      (libsource (lib "eagle-import") (part "DZMELF"))
    )
    (comp (ref "D7")
      (value "3V6")
      (footprint "eagle-import:DMELF")
      (libsource (lib "eagle-import") (part "DZMELF"))
    )
    (comp (ref "D8")
      (value "3V6")
      (footprint "eagle-import:DMELF")
      (libsource (lib "eagle-import") (part "DZMELF"))
    )
    (comp (ref "D9")
      (value "3V6")
      (footprint "eagle-import:DMELF")
      (libsource (lib "eagle-import") (part "DZMELF"))
    )
    (comp (ref "D10")
      (value "3V6")
      (footprint "eagle-import:DMELF")
      (libsource (lib "eagle-import") (part "DZMELF"))
    )
    (comp (ref "D11")
      (value "3V6")
      (footprint "eagle-import:DMELF")
      (libsource (lib "eagle-import") (part "DZMELF"))
    )
    (comp (ref "D12")
      (value "3V6")
      (footprint "eagle-import:DMELF")
      (libsource (lib "eagle-import") (part "DZMELF"))
    )
    (comp (ref "IC1")
      (value "THN10-2411WIR")
      (footprint "eagle-import:THL_20WI_SERIES")
      (libsource (lib "eagle-import") (part "THL_20WI_SERIES"))
    )
    (comp (ref "IC2")
      (value "MCP6064-E/SL")
      (footprint "eagle-import:SO14")
      (libsource (lib "eagle-import") (part "MCP604SL"))
    )
    (comp (ref "IC3")
      (value "MCP6064-E/SL")
      (footprint "eagle-import:SO14")
      (libsource (lib "eagle-import") (part "MCP604SL"))
    )
    (comp (ref "IC4")
      (value "MCP6064-E/SL")
      (footprint "eagle-import:SO14")
      (libsource (lib "eagle-import") (part "MCP604SL"))
    )
    (comp (ref "IC5")
      (value "MAX488CSA")
      (footprint "eagle-import:SO08")
      (fields (field (name "MF") "MAXIM"))
      (libsource (lib "eagle-import") (part "MAX488CSA"))
    )
    (comp (ref "IC6")
      (value "MOCD207MSOIC-8")
      (footprint "eagle-import:SOIC127P594X363-8N")
      (fields (field (name "MANUFACTURER") "ON Semiconductor") (field (name "MPN") "MOCD207M"))
      (libsource (lib "eagle-import") (part "MOCD207MSOIC-8"))
    )
    (comp (ref "IC7")
      (value "MOCD207MSOIC-8")
      (footprint "eagle-import:SOIC127P594X363-8N")
      (fields (field (name "MANUFACTURER") "ON Semiconductor") (field (name "MPN") "MOCD207M"))
      (libsource (lib "eagle-import") (part "MOCD207MSOIC-8"))
    )
    (comp (ref "IC8")
      (value "MOCD207MSOIC-8")
      (footprint "eagle-import:SOIC127P594X363-8N")
      (fields (field (name "MANUFACTURER") "ON Semiconductor") (field (name "MPN") "MOCD207M"))
      (libsource (lib "eagle-import") (part "MOCD207MSOIC-8"))
    )
    (comp (ref "IC9")
      (value "MCP6064-E/SL")
      (footprint "eagle-import:SO14")
      (libsource (lib "eagle-import") (part "MCP604SL"))
    )
    (comp (ref "IC10")
      (value "MCP6064-E/SL")
      (footprint "eagle-import:SO14")
      (libsource (lib "eagle-import") (part "MCP604SL"))
    )
    (comp (ref "IC12")
      (value "LM78L05ACMX/NOPB")
      (footprint "eagle-import:SOIC8")
      (libsource (lib "eagle-import") (part "LM78L05ACMX/NOPB"))
    )
    (comp (ref "IC13")
      (value "CH340G")
      (footprint "eagle-import:SOIC16")
      (libsource (lib "eagle-import") (part "CH340G"))
    )
    (comp (ref "L1")
      (value "1m")
      (footprint "eagle-import:L5650M")
      (libsource (lib "eagle-import") (part "L-EUL5650M"))
    )
    (comp (ref "L2")
      (value "1m")
      (footprint "eagle-import:L5650M")
      (libsource (lib "eagle-import") (part "L-EUL5650M"))
    )
    (comp (ref "L3")
      (value "1m")
      (footprint "eagle-import:L5650M")
      (libsource (lib "eagle-import") (part "L-EUL5650M"))
    )
    (comp (ref "L4")
      (value "1m")
      (footprint "eagle-import:L5650M")
      (libsource (lib "eagle-import") (part "L-EUL5650M"))
    )
    (comp (ref "L5")
      (value "1m")
      (footprint "eagle-import:L5650M")
      (libsource (lib "eagle-import") (part "L-EUL5650M"))
    )
    (comp (ref "Q1")
      (value "12MHz")
      (footprint "eagle-import:SM49")
      (libsource (lib "eagle-import") (part "CRYSTALSM49"))
    )
    (comp (ref "R1")
      (value "100k")
      (footprint "eagle-import:R0805")
      (libsource (lib "eagle-import") (part "rcl_334_R-EU_R0805"))
    )
    (comp (ref "R2")
      (value "1k")
      (footprint "eagle-import:R0805")
      (libsource (lib "eagle-import") (part "rcl_334_R-EU_R0805"))
    )
    (comp (ref "R3")
      (value "?")
      (footprint "eagle-import:R0805")
      (libsource (lib "eagle-import") (part "rcl_334_R-EU_R0805"))
    )
    (comp (ref "R4")
      (value "?")
      (footprint "eagle-import:R0805")
      (libsource (lib "eagle-import") (part "rcl_334_R-EU_R0805"))
    )
    (comp (ref "R5")
      (value "100k")
      (footprint "eagle-import:R0805")
      (libsource (lib "eagle-import") (part "rcl_334_R-EU_R0805"))
    )
    (comp (ref "R6")
      (value "1k")
      (footprint "eagle-import:R0805")
      (libsource (lib "eagle-import") (part "rcl_334_R-EU_R0805"))
    )
    (comp (ref "R7")
      (value "?")
      (footprint "eagle-import:R0805")
      (libsource (lib "eagle-import") (part "rcl_334_R-EU_R0805"))
    )
    (comp (ref "R8")
      (value "?")
      (footprint "eagle-import:R0805")
      (libsource (lib "eagle-import") (part "rcl_334_R-EU_R0805"))
    )
    (comp (ref "R10")
      (value "500")
      (footprint "eagle-import:R0805")
      (libsource (lib "eagle-import") (part "R-EU_R0805"))
    )
    (comp (ref "R11")
      (value "3k")
      (footprint "eagle-import:R0805")
      (libsource (lib "eagle-import") (part "rcl_334_R-EU_R0805"))
    )
    (comp (ref "R12")
      (value "2k")
      (footprint "eagle-import:R0805")
      (libsource (lib "eagle-import") (part "rcl_334_R-EU_R0805"))
    )
    (comp (ref "R13")
      (value "4k7")
      (footprint "eagle-import:R0805")
      (libsource (lib "eagle-import") (part "rcl_334_R-EU_R0805"))
    )
    (comp (ref "R14")
      (value "7k5")
      (footprint "eagle-import:R0805")
      (libsource (lib "eagle-import") (part "rcl_334_R-EU_R0805"))
    )
    (comp (ref "R15")
      (value "500")
      (footprint "eagle-import:R0805")
      (libsource (lib "eagle-import") (part "R-EU_R0805"))
    )
    (comp (ref "R16")
      (value "3k3")
      (footprint "eagle-import:R0805")
      (libsource (lib "eagle-import") (part "R-EU_R0805"))
    )
    (comp (ref "R17")
      (value "3k3")
      (footprint "eagle-import:R0805")
      (libsource (lib "eagle-import") (part "R-EU_R0805"))
    )
    (comp (ref "R22")
      (value "100k")
      (footprint "eagle-import:R0805")
      (libsource (lib "eagle-import") (part "rcl_334_R-EU_R0805"))
    )
    (comp (ref "R23")
      (value "1k")
      (footprint "eagle-import:R0805")
      (libsource (lib "eagle-import") (part "rcl_334_R-EU_R0805"))
    )
    (comp (ref "R24")
      (value "?")
      (footprint "eagle-import:R0805")
      (libsource (lib "eagle-import") (part "rcl_334_R-EU_R0805"))
    )
    (comp (ref "R25")
      (value "?")
      (footprint "eagle-import:R0805")
      (libsource (lib "eagle-import") (part "rcl_334_R-EU_R0805"))
    )
    (comp (ref "RN1")
      (value "?")
      (footprint "eagle-import:EXBS8V")
      (libsource (lib "eagle-import") (part "4R-NEXBS8V"))
    )
    (comp (ref "RN2")
      (value "?")
      (footprint "eagle-import:EXBS8V")
      (libsource (lib "eagle-import") (part "4R-NEXBS8V"))
    )
    (comp (ref "RN3")
      (value "?")
      (footprint "eagle-import:EXBS8V")
      (libsource (lib "eagle-import") (part "4R-NEXBS8V"))
    )
    (comp (ref "RN4")
      (value "?")
      (footprint "eagle-import:EXBS8V")
      (libsource (lib "eagle-import") (part "4R-NEXBS8V"))
    )
    (comp (ref "RN5")
      (value "?")
      (footprint "eagle-import:EXBS8V")
      (libsource (lib "eagle-import") (part "4R-NEXBS8V"))
    )
    (comp (ref "RN6")
      (value "?")
      (footprint "eagle-import:EXBS8V")
      (libsource (lib "eagle-import") (part "4R-NEXBS8V"))
    )
    (comp (ref "RN7")
      (value "?")
      (footprint "eagle-import:EXBS8V")
      (libsource (lib "eagle-import") (part "4R-NEXBS8V"))
    )
    (comp (ref "RN8")
      (value "?")
      (footprint "eagle-import:EXBS8V")
      (libsource (lib "eagle-import") (part "4R-NEXBS8V"))
    )
    (comp (ref "RN9")
      (value "?")
      (footprint "eagle-import:EXBS8V")
      (libsource (lib "eagle-import") (part "4R-NEXBS8V"))
    )
    (comp (ref "RN11")
      (value "3k")
      (footprint "eagle-import:EXBS8V")
      (libsource (lib "eagle-import") (part "4R-NEXBS8V"))
    )
    (comp (ref "RN12")
      (value "300")
      (footprint "eagle-import:EXBS8V")
      (libsource (lib "eagle-import") (part "4R-NEXBS8V"))
    )
    (comp (ref "RN13")
      (value "?")
      (footprint "eagle-import:EXBS8V")
      (libsource (lib "eagle-import") (part "4R-NEXBS8V"))
    )
    (comp (ref "RN14")
      (value "?")
      (footprint "eagle-import:EXBS8V")
      (libsource (lib "eagle-import") (part "4R-NEXBS8V"))
    )
    (comp (ref "RN15")
      (value "?")
      (footprint "eagle-import:EXBS8V")
      (libsource (lib "eagle-import") (part "4R-NEXBS8V"))
    )
    (comp (ref "RN16")
      (value "?")
      (footprint "eagle-import:EXBS8V")
      (libsource (lib "eagle-import") (part "4R-NEXBS8V"))
    )
    (comp (ref "RN17")
      (value "?")
      (footprint "eagle-import:EXBS8V")
      (libsource (lib "eagle-import") (part "4R-NEXBS8V"))
    )
    (comp (ref "RN18")
      (value "?")
      (footprint "eagle-import:EXBS8V")
      (libsource (lib "eagle-import") (part "4R-NEXBS8V"))
    )
    (comp (ref "U1")
      (value "ADR366WAUJZ")
      (footprint "eagle-import:SOT23-5")
      (libsource (lib "eagle-import") (part "ADR36UJZ_"))
    )
    (comp (ref "U2")
      (value "ADR366WAUJZ")
      (footprint "eagle-import:SOT23-5")
      (libsource (lib "eagle-import") (part "ADR36UJZ_"))
    )
    (comp (ref "U3")
      (value "ADS1148QPWRQ1")
      (footprint "eagle-import:TSSOP28")
      (libsource (lib "eagle-import") (part "ADS1148QPWRQ1"))
    )
    (comp (ref "U4")
      (value "ADS1148QPWRQ1")
      (footprint "eagle-import:TSSOP28")
      (libsource (lib "eagle-import") (part "ADS1148QPWRQ1"))
    )
    (comp (ref "U5")
      (value "ADS1148QPWRQ1")
      (footprint "eagle-import:TSSOP28")
      (libsource (lib "eagle-import") (part "ADS1148QPWRQ1"))
    )
    (comp (ref "U6")
      (value "LT1528")
      (footprint "eagle-import:Q5-DD")
      (libsource (lib "eagle-import") (part "LT1528"))
    )
    (comp (ref "U7")
      (value "S70FL01GS")
      (footprint "eagle-import:SO16")
      (libsource (lib "eagle-import") (part "S70FL01GS"))
    )
    (comp (ref "U8")
      (value "S70FL01GS")
      (footprint "eagle-import:SO16")
      (libsource (lib "eagle-import") (part "S70FL01GS"))
    )
    (comp (ref "U10")
      (value "ADS1148QPWRQ1")
      (footprint "eagle-import:TSSOP28")
      (libsource (lib "eagle-import") (part "ADS1148QPWRQ1"))
    )
    (comp (ref "U11")
      (value "ADS1148QPWRQ1")
      (footprint "eagle-import:TSSOP28")
      (libsource (lib "eagle-import") (part "ADS1148QPWRQ1"))
    )
    (comp (ref "U12")
      (value "ADS1148QPWRQ1")
      (footprint "eagle-import:TSSOP28")
      (libsource (lib "eagle-import") (part "ADS1148QPWRQ1"))
    )
    (comp (ref "U13")
      (value "ADR366WAUJZ")
      (footprint "eagle-import:SOT23-5")
      (libsource (lib "eagle-import") (part "ADR36UJZ_"))
    )
  )
  (nets
    (net (code "1") (name "3V3") (class "Default")
      (node (ref "C19") (pin "1") (pinfunction "1_1") (pintype "passive"))
      (node (ref "C20") (pin "1") (pinfunction "1_1") (pintype "passive"))
      (node (ref "C22") (pin "1") (pinfunction "1_1") (pintype "passive"))
      (node (ref "C23") (pin "1") (pinfunction "1_1") (pintype "passive"))
      (node (ref "C25") (pin "1") (pinfunction "1_1") (pintype "passive"))
      (node (ref "C26") (pin "1") (pinfunction "1_1") (pintype "passive"))
      (node (ref "C28") (pin "1") (pinfunction "1_1") (pintype "passive"))
      (node (ref "C29") (pin "1") (pinfunction "1_1") (pintype "passive"))
      (node (ref "C30") (pin "1") (pinfunction "1_1") (pintype "passive"))
      (node (ref "C31") (pin "1") (pinfunction "1_1") (pintype "passive"))
      (node (ref "C32") (pin "1") (pinfunction "1_1") (pintype "passive"))
      (node (ref "C33") (pin "1") (pinfunction "1_1") (pintype "passive"))
      (node (ref "C37") (pin "2") (pinfunction "2_2") (pintype "passive"))
      (node (ref "C41") (pin "+") (pinfunction "+_+") (pintype "passive"))
      (node (ref "C45") (pin "1") (pinfunction "1_1") (pintype "passive"))
      (node (ref "C46") (pin "1") (pinfunction "1_1") (pintype "passive"))
      (node (ref "C48") (pin "1") (pinfunction "1_1") (pintype "passive"))
      (node (ref "C49") (pin "1") (pinfunction "1_1") (pintype "passive"))
      (node (ref "IC13") (pin "16") (pinfunction "VCC_16") (pintype "bidirectional"))
      (node (ref "L1") (pin "1") (pinfunction "1_1") (pintype "passive"))
      (node (ref "L2") (pin "1") (pinfunction "1_1") (pintype "passive"))
      (node (ref "L3") (pin "1") (pinfunction "1_1") (pintype "passive"))
      (node (ref "L4") (pin "1") (pinfunction "1_1") (pintype "passive"))
      (node (ref "L5") (pin "1") (pinfunction "1_1") (pintype "passive"))
      (node (ref "R13") (pin "2") (pinfunction "2_2") (pintype "passive"))
      (node (ref "R19") (pin "2") (pinfunction "2_2") (pintype "passive"))
      (node (ref "R26") (pin "2") (pinfunction "2_2") (pintype "passive"))
      (node (ref "R28") (pin "1") (pinfunction "1_1") (pintype "passive"))
      (node (ref "R29") (pin "2") (pinfunction "2_2") (pintype "passive"))
      (node (ref "R9") (pin "2") (pinfunction "2_2") (pintype "passive"))
      (node (ref "RN12") (pin "1") (pinfunction "1_1") (pintype "passive"))
      (node (ref "RN12") (pin "2") (pinfunction "1_2") (pintype "passive"))
      (node (ref "RN12") (pin "3") (pinfunction "1_3") (pintype "passive"))
      (node (ref "RN12") (pin "4") (pinfunction "1_4") (pintype "passive"))
      (node (ref "U10") (pin "1") (pinfunction "DVDD_1") (pintype "bidirectional"))
      (node (ref "U10") (pin "22") (pinfunction "AVDD_22") (pintype "bidirectional"))
      (node (ref "U11") (pin "1") (pinfunction "DVDD_1") (pintype "bidirectional"))
      (node (ref "U11") (pin "22") (pinfunction "AVDD_22") (pintype "bidirectional"))
      (node (ref "U12") (pin "1") (pinfunction "DVDD_1") (pintype "bidirectional"))
      (node (ref "U12") (pin "22") (pinfunction "AVDD_22") (pintype "bidirectional"))
      (node (ref "U3") (pin "1") (pinfunction "DVDD_1") (pintype "bidirectional"))
      (node (ref "U3") (pin "22") (pinfunction "AVDD_22") (pintype "bidirectional"))
      (node (ref "U4") (pin "1") (pinfunction "DVDD_1") (pintype "bidirectional"))
      (node (ref "U4") (pin "22") (pinfunction "AVDD_22") (pintype "bidirectional"))
      (node (ref "U5") (pin "1") (pinfunction "DVDD_1") (pintype "bidirectional"))
      (node (ref "U5") (pin "22") (pinfunction "AVDD_22") (pintype "bidirectional"))
      (node (ref "U6") (pin "1") (pinfunction "OUT_1") (pintype "bidirectional"))
      (node (ref "U6") (pin "2") (pinfunction "SENSE_2") (pintype "bidirectional"))
      (node (ref "U7") (pin "2") (pinfunction "VCC_2") (pintype "bidirectional"))
      (node (ref "U8") (pin "2") (pinfunction "VCC_2") (pintype "bidirectional"))
      (node (ref "U9") (pin "103") (pinfunction "VDD_103") (pintype "bidirectional"))
      (node (ref "U9") (pin "115") (pinfunction "VDD_115") (pintype "bidirectional"))
      (node (ref "U9") (pin "118") (pinfunction "VDDDSI_118") (pintype "bidirectional"))
      (node (ref "U9") (pin "137") (pinfunction "VDDUSB_137") (pintype "bidirectional"))
      (node (ref "U9") (pin "15") (pinfunction "VDD_15") (pintype "bidirectional"))
      (node (ref "U9") (pin "150") (pinfunction "VDD_150") (pintype "bidirectional"))
      (node (ref "U9") (pin "158") (pinfunction "VDD_158") (pintype "bidirectional"))
      (node (ref "U9") (pin "171") (pinfunction "VDDSDMMC_171") (pintype "bidirectional"))
      (node (ref "U9") (pin "185") (pinfunction "VDD_185") (pintype "bidirectional"))
      (node (ref "U9") (pin "204") (pinfunction "VDD_204") (pintype "bidirectional"))
      (node (ref "U9") (pin "26") (pinfunction "VDD_26") (pintype "bidirectional"))
      (node (ref "U9") (pin "39") (pinfunction "VDD_39") (pintype "bidirectional"))
      (node (ref "U9") (pin "42") (pinfunction "VDDA_42") (pintype "bidirectional"))
      (node (ref "U9") (pin "52") (pinfunction "VDD_52") (pintype "bidirectional"))
      (node (ref "U9") (pin "59") (pinfunction "VDD_59") (pintype "bidirectional"))
      (node (ref "U9") (pin "73") (pinfunction "VDD_73") (pintype "bidirectional"))
      (node (ref "U9") (pin "83") (pinfunction "VDD_83") (pintype "bidirectional"))
      (node (ref "U9") (pin "94") (pinfunction "VDD_94") (pintype "bidirectional"))
      (node (ref "X_PROG") (pin "1") (pinfunction "1_1") (pintype "passive"))
    )
    (net (code "2") (name "3V3CAP") (class "Default")
      (node (ref "U9") (pin "6") (pinfunction "VBAT_6") (pintype "bidirectional"))
    )
    (net (code "3") (name "3V3REF") (class "Default")
      (node (ref "C4") (pin "2") (pinfunction "2_2") (pintype "passive"))
      (node (ref "C55") (pin "2") (pinfunction "2_2") (pintype "passive"))
      (node (ref "C9") (pin "2") (pinfunction "2_2") (pintype "passive"))
      (node (ref "R3") (pin "2") (pinfunction "2_2") (pintype "passive"))
      (node (ref "RN1") (pin "1") (pinfunction "1_1") (pintype "passive"))
      (node (ref "RN1") (pin "2") (pinfunction "1_2") (pintype "passive"))
      (node (ref "RN1") (pin "3") (pinfunction "1_3") (pintype "passive"))
      (node (ref "RN1") (pin "4") (pinfunction "1_4") (pintype "passive"))
      (node (ref "RN13") (pin "1") (pinfunction "1_1") (pintype "passive"))
      (node (ref "RN13") (pin "2") (pinfunction "1_2") (pintype "passive"))
      (node (ref "RN13") (pin "3") (pinfunction "1_3") (pintype "passive"))
      (node (ref "RN13") (pin "4") (pinfunction "1_4") (pintype "passive"))
      (node (ref "RN4") (pin "1") (pinfunction "1_1") (pintype "passive"))
      (node (ref "RN4") (pin "2") (pinfunction "1_2") (pintype "passive"))
      (node (ref "RN4") (pin "3") (pinfunction "1_3") (pintype "passive"))
      (node (ref "RN4") (pin "4") (pinfunction "1_4") (pintype "passive"))
      (node (ref "U1") (pin "4") (pinfunction "VOUT_4") (pintype "power_in"))
    )
    (net (code "4") (name "3V3REF2") (class "Default")
      (node (ref "C14") (pin "2") (pinfunction "2_2") (pintype "passive"))
      (node (ref "C58") (pin "2") (pinfunction "2_2") (pintype "passive"))
      (node (ref "R7") (pin "2") (pinfunction "2_2") (pintype "passive"))
      (node (ref "RN16") (pin "1") (pinfunction "1_1") (pintype "passive"))
      (node (ref "RN16") (pin "2") (pinfunction "1_2") (pintype "passive"))
      (node (ref "RN16") (pin "3") (pinfunction "1_3") (pintype "passive"))
      (node (ref "RN16") (pin "4") (pinfunction "1_4") (pintype "passive"))
      (node (ref "RN7") (pin "1") (pinfunction "1_1") (pintype "passive"))
      (node (ref "RN7") (pin "2") (pinfunction "1_2") (pintype "passive"))
      (node (ref "RN7") (pin "3") (pinfunction "1_3") (pintype "passive"))
      (node (ref "RN7") (pin "4") (pinfunction "1_4") (pintype "passive"))
      (node (ref "U2") (pin "4") (pinfunction "VOUT_4") (pintype "power_in"))
    )
    (net (code "5") (name "3V3REF3") (class "Default")
      (node (ref "R24") (pin "2") (pinfunction "2_2") (pintype "passive"))
      (node (ref "U13") (pin "4") (pinfunction "VOUT_4") (pintype "power_in"))
      (node (ref "U9") (pin "41") (pinfunction "VREF+_41") (pintype "bidirectional"))
    )
    (net (code "6") (name "5V") (class "Default")
      (node (ref "C11") (pin "+") (pinfunction "+_+") (pintype "passive"))
      (node (ref "C12") (pin "2") (pinfunction "2_2") (pintype "passive"))
      (node (ref "C35") (pin "2") (pinfunction "2_2") (pintype "passive"))
      (node (ref "C36") (pin "2") (pinfunction "2_2") (pintype "passive"))
      (node (ref "C39") (pin "+") (pinfunction "+_+") (pintype "passive"))
      (node (ref "C40") (pin "+") (pinfunction "+_+") (pintype "passive"))
      (node (ref "C52") (pin "2") (pinfunction "2_2") (pintype "passive"))
      (node (ref "C7") (pin "+") (pinfunction "+_+") (pintype "passive"))
      (node (ref "C8") (pin "2") (pinfunction "2_2") (pintype "passive"))
      (node (ref "IC1") (pin "3") (pinfunction "+VOUT_3") (pintype "passive"))
      (node (ref "R18") (pin "2") (pinfunction "2_2") (pintype "passive"))
      (node (ref "U1") (pin "3") (pinfunction "VIN_3") (pintype "power_in"))
      (node (ref "U13") (pin "3") (pinfunction "VIN_3") (pintype "power_in"))
      (node (ref "U2") (pin "3") (pinfunction "VIN_3") (pintype "power_in"))
      (node (ref "U6") (pin "4") (pinfunction "SHDN_4") (pintype "bidirectional"))
      (node (ref "U6") (pin "5") (pinfunction "IN_5") (pintype "bidirectional"))
      (node (ref "X3") (pin "VBUS") (pinfunction "VBUS_VBUS") (pintype "bidirectional"))
    )
    (net (code "7") (name "5V-28V") (class "Default")
      (node (ref "C43") (pin "1") (pinfunction "1_1") (pintype "passive"))
      (node (ref "IC12") (pin "1") (pinfunction "VOUT_1") (pintype "bidirectional"))
      (node (ref "IC5") (pin "1") (pinfunction "VCC_1") (pintype "power_in"))
      (node (ref "R14") (pin "2") (pinfunction "2_2") (pintype "passive"))
      (node (ref "R16") (pin "1") (pinfunction "1_1") (pintype "passive"))
      (node (ref "R21") (pin "2") (pinfunction "2_2") (pintype "passive"))
    )
    (net (code "8") (name "28V") (class "Default")
      (node (ref "C34") (pin "2") (pinfunction "2_2") (pintype "passive"))
      (node (ref "C38") (pin "+") (pinfunction "+_+") (pintype "passive"))
      (node (ref "C42") (pin "2") (pinfunction "2_2") (pintype "passive"))
      (node (ref "IC1") (pin "1") (pinfunction "+VIN_1") (pintype "input"))
      (node (ref "IC12") (pin "8") (pinfunction "VIN_8") (pintype "bidirectional"))
      (node (ref "R20") (pin "2") (pinfunction "2_2") (pintype "passive"))
      (node (ref "RN11") (pin "1") (pinfunction "1_1") (pintype "passive"))
      (node (ref "RN11") (pin "2") (pinfunction "1_2") (pintype "passive"))
      (node (ref "RN11") (pin "3") (pinfunction "1_3") (pintype "passive"))
      (node (ref "RN11") (pin "4") (pinfunction "1_4") (pintype "passive"))
      (node (ref "X1") (pin "9") (pinfunction "F_9") (pintype "passive"))
      (node (ref "X2") (pin "1") (pinfunction "F_1") (pintype "passive"))
      (node (ref "X2") (pin "9") (pinfunction "F_9") (pintype "passive"))
    )
    (net (code "9") (name "28VGND") (class "Default")
      (node (ref "C34") (pin "1") (pinfunction "1_1") (pintype "passive"))
      (node (ref "C38") (pin "-") (pinfunction "-_-") (pintype "passive"))
      (node (ref "C42") (pin "1") (pinfunction "1_1") (pintype "passive"))
      (node (ref "C43") (pin "2") (pinfunction "2_2") (pintype "passive"))
      (node (ref "C44") (pin "2") (pinfunction "2_2") (pintype "passive"))
      (node (ref "D5") (pin "A") (pinfunction "A_A") (pintype "passive"))
      (node (ref "D6") (pin "A") (pinfunction "A_A") (pintype "passive"))
      (node (ref "IC1") (pin "2") (pinfunction "-VIN_2") (pintype "input"))
      (node (ref "IC12") (pin "2") (pinfunction "GND_2") (pintype "bidirectional"))
      (node (ref "IC12") (pin "3") (pinfunction "GND_3") (pintype "bidirectional"))
      (node (ref "IC12") (pin "6") (pinfunction "GND_6") (pintype "bidirectional"))
      (node (ref "IC12") (pin "7") (pinfunction "GND_7") (pintype "bidirectional"))
      (node (ref "IC5") (pin "4") (pinfunction "GND_4") (pintype "power_in"))
      (node (ref "IC8") (pin "5") (pinfunction "EMT2_5") (pintype "output"))
      (node (ref "LED7") (pin "C") (pinfunction "C_C") (pintype "passive"))
      (node (ref "LED8") (pin "C") (pinfunction "C_C") (pintype "passive"))
      (node (ref "R11") (pin "1") (pinfunction "1_1") (pintype "passive"))
      (node (ref "R17") (pin "1") (pinfunction "1_1") (pintype "passive"))
      (node (ref "X1") (pin "8") (pinfunction "F_8") (pintype "passive"))
      (node (ref "X2") (pin "15") (pinfunction "F_15") (pintype "passive"))
      (node (ref "X2") (pin "8") (pinfunction "F_8") (pintype "passive"))
    )
    (net (code "10") (name "ADC1_DRDY") (class "Default")
      (node (ref "U4") (pin "25") (pinfunction "~{DRDY}_25") (pintype "bidirectional"))
      (node (ref "U9") (pin "65") (pinfunction "PJ0_65") (pintype "bidirectional"))
    )
    (net (code "11") (name "ADC1_RES") (class "Default")
      (node (ref "U4") (pin "4") (pinfunction "~{RESET}_4") (pintype "bidirectional"))
      (node (ref "U9") (pin "68") (pinfunction "PJ3_68") (pintype "bidirectional"))
    )
    (net (code "12") (name "ADC1_START") (class "Default")
      (node (ref "U4") (pin "23") (pinfunction "START_23") (pintype "bidirectional"))
      (node (ref "U9") (pin "67") (pinfunction "PJ2_67") (pintype "bidirectional"))
    )
    (net (code "13") (name "ADC2_DRDY") (class "Default")
      (node (ref "U3") (pin "25") (pinfunction "~{DRDY}_25") (pintype "bidirectional"))
      (node (ref "U9") (pin "47") (pinfunction "PH3_47") (pintype "bidirectional"))
    )
    (net (code "14") (name "ADC2_RES") (class "Default")
      (node (ref "U3") (pin "4") (pinfunction "~{RESET}_4") (pintype "bidirectional"))
      (node (ref "U9") (pin "50") (pinfunction "PA3_50") (pintype "bidirectional"))
    )
    (net (code "15") (name "ADC2_START") (class "Default")
      (node (ref "U3") (pin "23") (pinfunction "START_23") (pintype "bidirectional"))
      (node (ref "U9") (pin "49") (pinfunction "PH5_49") (pintype "bidirectional"))
    )
    (net (code "16") (name "ADC3_DRDY") (class "Default")
      (node (ref "U5") (pin "25") (pinfunction "~{DRDY}_25") (pintype "bidirectional"))
      (node (ref "U9") (pin "71") (pinfunction "PF12_71") (pintype "bidirectional"))
    )
    (net (code "17") (name "ADC3_RES") (class "Default")
      (node (ref "U5") (pin "4") (pinfunction "~{RESET}_4") (pintype "bidirectional"))
      (node (ref "U9") (pin "76") (pinfunction "PF15_76") (pintype "bidirectional"))
    )
    (net (code "18") (name "ADC3_START") (class "Default")
      (node (ref "U5") (pin "23") (pinfunction "START_23") (pintype "bidirectional"))
      (node (ref "U9") (pin "75") (pinfunction "PF14_75") (pintype "bidirectional"))
    )
    (net (code "19") (name "ADC4_DRDY") (class "Default")
      (node (ref "U11") (pin "25") (pinfunction "~{DRDY}_25") (pintype "bidirectional"))
      (node (ref "U9") (pin "32") (pinfunction "PH0_32") (pintype "bidirectional"))
    )
    (net (code "20") (name "ADC4_RES") (class "Default")
      (node (ref "U11") (pin "4") (pinfunction "~{RESET}_4") (pintype "bidirectional"))
      (node (ref "U9") (pin "31") (pinfunction "PF10_31") (pintype "bidirectional"))
    )
    (net (code "21") (name "ADC4_START") (class "Default")
      (node (ref "U11") (pin "23") (pinfunction "START_23") (pintype "bidirectional"))
      (node (ref "U9") (pin "30") (pinfunction "PF9_30") (pintype "bidirectional"))
    )
    (net (code "22") (name "ADC5_DRDY") (class "Default")
      (node (ref "U10") (pin "25") (pinfunction "~{DRDY}_25") (pintype "bidirectional"))
      (node (ref "U9") (pin "44") (pinfunction "PA1_44") (pintype "bidirectional"))
    )
    (net (code "23") (name "ADC5_RES") (class "Default")
      (node (ref "U10") (pin "4") (pinfunction "~{RESET}_4") (pintype "bidirectional"))
      (node (ref "U9") (pin "37") (pinfunction "PC2_37") (pintype "bidirectional"))
    )
    (net (code "24") (name "ADC5_START") (class "Default")
      (node (ref "U10") (pin "23") (pinfunction "START_23") (pintype "bidirectional"))
      (node (ref "U9") (pin "35") (pinfunction "PC0_35") (pintype "bidirectional"))
    )
    (net (code "25") (name "ADC6_DRDY") (class "Default")
      (node (ref "U12") (pin "25") (pinfunction "~{DRDY}_25") (pintype "bidirectional"))
      (node (ref "U9") (pin "45") (pinfunction "PA2_45") (pintype "bidirectional"))
    )
    (net (code "26") (name "ADC6_RES") (class "Default")
      (node (ref "U12") (pin "4") (pinfunction "~{RESET}_4") (pintype "bidirectional"))
      (node (ref "U9") (pin "33") (pinfunction "PH1_33") (pintype "bidirectional"))
    )
    (net (code "27") (name "ADC6_START") (class "Default")
      (node (ref "U12") (pin "23") (pinfunction "START_23") (pintype "bidirectional"))
      (node (ref "U9") (pin "38") (pinfunction "PC3_38") (pintype "bidirectional"))
    )
    (net (code "28") (name "DAPI_N") (class "Default")
      (node (ref "D1") (pin "C") (pinfunction "C_C") (pintype "passive"))
      (node (ref "IC13") (pin "6") (pinfunction "D-_6") (pintype "bidirectional"))
      (node (ref "X3") (pin "D-") (pinfunction "D-_D-") (pintype "bidirectional"))
    )
    (net (code "29") (name "DAPI_P") (class "Default")
      (node (ref "D2") (pin "C") (pinfunction "C_C") (pintype "passive"))
      (node (ref "IC13") (pin "5") (pinfunction "D+_5") (pintype "bidirectional"))
      (node (ref "X3") (pin "D+") (pinfunction "D+_D+") (pintype "bidirectional"))
    )
    (net (code "30") (name "DAPI_RX") (class "Default")
      (node (ref "D4") (pin "C") (pinfunction "C_C") (pintype "passive"))
      (node (ref "IC13") (pin "2") (pinfunction "TX_2") (pintype "bidirectional"))
      (node (ref "U9") (pin "11") (pinfunction "PI9_11") (pintype "bidirectional"))
    )
    (net (code "31") (name "DAPI_TX") (class "Default")
      (node (ref "D3") (pin "C") (pinfunction "C_C") (pintype "passive"))
      (node (ref "IC13") (pin "3") (pinfunction "RX_3") (pintype "bidirectional"))
      (node (ref "U9") (pin "43") (pinfunction "PA0_43") (pintype "bidirectional"))
    )
    (net (code "32") (name "EXP_IN") (class "Default")
      (node (ref "D5") (pin "C") (pinfunction "C_C") (pintype "passive"))
      (node (ref "IC5") (pin "2") (pinfunction "RO_2") (pintype "output"))
      (node (ref "IC8") (pin "1") (pinfunction "A1_1") (pintype "bidirectional"))
    )
    (net (code "33") (name "EXP_IN_N") (class "Default")
      (node (ref "IC5") (pin "7") (pinfunction "B_7") (pintype "input"))
      (node (ref "R15") (pin "1") (pinfunction "1_1") (pintype "passive"))
      (node (ref "R17") (pin "2") (pinfunction "2_2") (pintype "passive"))
      (node (ref "X2") (pin "14") (pinfunction "F_14") (pintype "passive"))
    )
    (net (code "34") (name "EXP_IN_OPT") (class "Default")
      (node (ref "D10") (pin "C") (pinfunction "C_C") (pintype "passive"))
      (node (ref "IC8") (pin "8") (pinfunction "COL1_8") (pintype "input"))
      (node (ref "R13") (pin "1") (pinfunction "1_1") (pintype "passive"))
      (node (ref "U9") (pin "200") (pinfunction "PE0_200") (pintype "bidirectional"))
    )
    (net (code "35") (name "EXP_IN_P") (class "Default")
      (node (ref "IC5") (pin "8") (pinfunction "A_8") (pintype "input"))
      (node (ref "R10") (pin "2") (pinfunction "2_2") (pintype "passive"))
      (node (ref "R16") (pin "2") (pinfunction "2_2") (pintype "passive"))
      (node (ref "X2") (pin "13") (pinfunction "F_13") (pintype "passive"))
    )
    (net (code "36") (name "EXP_OUT") (class "Default")
      (node (ref "D6") (pin "C") (pinfunction "C_C") (pintype "passive"))
      (node (ref "IC5") (pin "3") (pinfunction "DI_3") (pintype "input"))
      (node (ref "IC8") (pin "6") (pinfunction "COL2_6") (pintype "input"))
      (node (ref "R14") (pin "1") (pinfunction "1_1") (pintype "passive"))
    )
    (net (code "37") (name "EXP_OUT_N") (class "Default")
      (node (ref "IC5") (pin "6") (pinfunction "Z_6") (pintype "output"))
      (node (ref "X2") (pin "7") (pinfunction "F_7") (pintype "passive"))
    )
    (net (code "38") (name "EXP_OUT_OPT") (class "Default")
      (node (ref "IC8") (pin "3") (pinfunction "A2_3") (pintype "bidirectional"))
      (node (ref "U9") (pin "201") (pinfunction "PE1_201") (pintype "bidirectional"))
    )
    (net (code "39") (name "EXP_OUT_P") (class "Default")
      (node (ref "IC5") (pin "5") (pinfunction "Y_5") (pintype "output"))
      (node (ref "X2") (pin "6") (pinfunction "F_6") (pintype "passive"))
    )
    (net (code "40") (name "FL_1_CS1") (class "Default")
      (node (ref "U7") (pin "7") (pinfunction "CS1_7") (pintype "bidirectional"))
      (node (ref "U9") (pin "104") (pinfunction "PB12_104") (pintype "bidirectional"))
    )
    (net (code "41") (name "FL_1_CS2") (class "Default")
      (node (ref "U7") (pin "6") (pinfunction "CS2_6") (pintype "bidirectional"))
      (node (ref "U9") (pin "102") (pinfunction "PH12_102") (pintype "bidirectional"))
    )
    (net (code "42") (name "FL_1_HLD") (class "Default")
      (node (ref "U7") (pin "1") (pinfunction "HOLD_1") (pintype "bidirectional"))
      (node (ref "U9") (pin "99") (pinfunction "PH9_99") (pintype "bidirectional"))
    )
    (net (code "43") (name "FL_1_RES") (class "Default")
      (node (ref "U7") (pin "3") (pinfunction "RESET_3") (pintype "bidirectional"))
      (node (ref "U9") (pin "101") (pinfunction "PH11_101") (pintype "bidirectional"))
    )
    (net (code "44") (name "FL_1_WP") (class "Default")
      (node (ref "U7") (pin "9") (pinfunction "WP_9") (pintype "bidirectional"))
      (node (ref "U9") (pin "100") (pinfunction "PH10_100") (pintype "bidirectional"))
    )
    (net (code "45") (name "FL_2_CS1") (class "Default")
      (node (ref "U8") (pin "7") (pinfunction "CS1_7") (pintype "bidirectional"))
      (node (ref "U9") (pin "112") (pinfunction "PD12_112") (pintype "bidirectional"))
    )
    (net (code "46") (name "FL_2_CS2") (class "Default")
      (node (ref "U8") (pin "6") (pinfunction "CS2_6") (pintype "bidirectional"))
      (node (ref "U9") (pin "111") (pinfunction "PD11_111") (pintype "bidirectional"))
    )
    (net (code "47") (name "FL_2_HLD") (class "Default")
      (node (ref "U8") (pin "1") (pinfunction "HOLD_1") (pintype "bidirectional"))
      (node (ref "U9") (pin "109") (pinfunction "PD9_109") (pintype "bidirectional"))
    )
    (net (code "48") (name "FL_2_RES") (class "Default")
      (node (ref "U8") (pin "3") (pinfunction "RESET_3") (pintype "bidirectional"))
      (node (ref "U9") (pin "110") (pinfunction "PD10_110") (pintype "bidirectional"))
    )
    (net (code "49") (name "FL_2_WP") (class "Default")
      (node (ref "U8") (pin "9") (pinfunction "WP_9") (pintype "bidirectional"))
      (node (ref "U9") (pin "108") (pinfunction "PD8_108") (pintype "bidirectional"))
    )
    (net (code "50") (name "GND") (class "Default")
      (node (ref "C1") (pin "2") (pinfunction "2_2") (pintype "passive"))
      (node (ref "C10") (pin "-") (pinfunction "-_-") (pintype "passive"))
      (node (ref "C11") (pin "-") (pinfunction "-_-") (pintype "passive"))
      (node (ref "C12") (pin "1") (pinfunction "1_1") (pintype "passive"))
      (node (ref "C13") (pin "1") (pinfunction "1_1") (pintype "passive"))
      (node (ref "C14") (pin "1") (pinfunction "1_1") (pintype "passive"))
      (node (ref "C15") (pin "-") (pinfunction "-_-") (pintype "passive"))
      (node (ref "C16") (pin "1") (pinfunction "1_1") (pintype "passive"))
      (node (ref "C17") (pin "1") (pinfunction "1_1") (pintype "passive"))
      (node (ref "C18") (pin "2") (pinfunction "2_2") (pintype "passive"))
      (node (ref "C19") (pin "2") (pinfunction "2_2") (pintype "passive"))
      (node (ref "C2") (pin "2") (pinfunction "2_2") (pintype "passive"))
      (node (ref "C20") (pin "2") (pinfunction "2_2") (pintype "passive"))
      (node (ref "C21") (pin "2") (pinfunction "2_2") (pintype "passive"))
      (node (ref "C22") (pin "2") (pinfunction "2_2") (pintype "passive"))
      (node (ref "C23") (pin "2") (pinfunction "2_2") (pintype "passive"))
      (node (ref "C24") (pin "2") (pinfunction "2_2") (pintype "passive"))
      (node (ref "C25") (pin "2") (pinfunction "2_2") (pintype "passive"))
      (node (ref "C26") (pin "2") (pinfunction "2_2") (pintype "passive"))
      (node (ref "C27") (pin "2") (pinfunction "2_2") (pintype "passive"))
      (node (ref "C28") (pin "2") (pinfunction "2_2") (pintype "passive"))
      (node (ref "C29") (pin "2") (pinfunction "2_2") (pintype "passive"))
      (node (ref "C3") (pin "1") (pinfunction "1_1") (pintype "passive"))
      (node (ref "C30") (pin "2") (pinfunction "2_2") (pintype "passive"))
      (node (ref "C31") (pin "2") (pinfunction "2_2") (pintype "passive"))
      (node (ref "C32") (pin "2") (pinfunction "2_2") (pintype "passive"))
      (node (ref "C33") (pin "2") (pinfunction "2_2") (pintype "passive"))
      (node (ref "C35") (pin "1") (pinfunction "1_1") (pintype "passive"))
      (node (ref "C36") (pin "1") (pinfunction "1_1") (pintype "passive"))
      (node (ref "C37") (pin "1") (pinfunction "1_1") (pintype "passive"))
      (node (ref "C39") (pin "-") (pinfunction "-_-") (pintype "passive"))
      (node (ref "C4") (pin "1") (pinfunction "1_1") (pintype "passive"))
      (node (ref "C40") (pin "-") (pinfunction "-_-") (pintype "passive"))
      (node (ref "C41") (pin "-") (pinfunction "-_-") (pintype "passive"))
      (node (ref "C45") (pin "2") (pinfunction "2_2") (pintype "passive"))
      (node (ref "C46") (pin "2") (pinfunction "2_2") (pintype "passive"))
      (node (ref "C47") (pin "2") (pinfunction "2_2") (pintype "passive"))
      (node (ref "C48") (pin "2") (pinfunction "2_2") (pintype "passive"))
      (node (ref "C49") (pin "2") (pinfunction "2_2") (pintype "passive"))
      (node (ref "C5") (pin "-") (pinfunction "-_-") (pintype "passive"))
      (node (ref "C50") (pin "2") (pinfunction "2_2") (pintype "passive"))
      (node (ref "C52") (pin "1") (pinfunction "1_1") (pintype "passive"))
      (node (ref "C53") (pin "2") (pinfunction "2_2") (pintype "passive"))
      (node (ref "C54") (pin "1") (pinfunction "1_1") (pintype "passive"))
      (node (ref "C55") (pin "1") (pinfunction "1_1") (pintype "passive"))
      (node (ref "C57") (pin "1") (pinfunction "1_1") (pintype "passive"))
      (node (ref "C58") (pin "1") (pinfunction "1_1") (pintype "passive"))
      (node (ref "C6") (pin "1") (pinfunction "1_1") (pintype "passive"))
      (node (ref "C7") (pin "-") (pinfunction "-_-") (pintype "passive"))
      (node (ref "C8") (pin "1") (pinfunction "1_1") (pintype "passive"))
      (node (ref "C9") (pin "1") (pinfunction "1_1") (pintype "passive"))
      (node (ref "D1") (pin "A") (pinfunction "A_A") (pintype "passive"))
      (node (ref "D10") (pin "A") (pinfunction "A_A") (pintype "passive"))
      (node (ref "D11") (pin "A") (pinfunction "A_A") (pintype "passive"))
      (node (ref "D12") (pin "A") (pinfunction "A_A") (pintype "passive"))
      (node (ref "D2") (pin "A") (pinfunction "A_A") (pintype "passive"))
      (node (ref "D3") (pin "A") (pinfunction "A_A") (pintype "passive"))
      (node (ref "D4") (pin "A") (pinfunction "A_A") (pintype "passive"))
      (node (ref "D7") (pin "A") (pinfunction "A_A") (pintype "passive"))
      (node (ref "D8") (pin "A") (pinfunction "A_A") (pintype "passive"))
      (node (ref "D9") (pin "A") (pinfunction "A_A") (pintype "passive"))
      (node (ref "IC1") (pin "5") (pinfunction "-VOUT_5") (pintype "passive"))
      (node (ref "IC10") (pin "11") (pinfunction "V-_11") (pintype "power_in"))
      (node (ref "IC13") (pin "1") (pinfunction "GND_1") (pintype "bidirectional"))
      (node (ref "IC2") (pin "11") (pinfunction "V-_11") (pintype "power_in"))
      (node (ref "IC3") (pin "11") (pinfunction "V-_11") (pintype "power_in"))
      (node (ref "IC4") (pin "11") (pinfunction "V-_11") (pintype "power_in"))
      (node (ref "IC6") (pin "5") (pinfunction "EMT2_5") (pintype "output"))
      (node (ref "IC6") (pin "7") (pinfunction "EMT1_7") (pintype "output"))
      (node (ref "IC7") (pin "5") (pinfunction "EMT2_5") (pintype "output"))
      (node (ref "IC7") (pin "7") (pinfunction "EMT1_7") (pintype "output"))
      (node (ref "IC8") (pin "7") (pinfunction "EMT1_7") (pintype "output"))
      (node (ref "IC9") (pin "11") (pinfunction "V-_11") (pintype "power_in"))
      (node (ref "JP_MS") (pin "1") (pinfunction "1_1") (pintype "passive"))
      (node (ref "LED1") (pin "C") (pinfunction "C_C") (pintype "passive"))
      (node (ref "LED2") (pin "C") (pinfunction "C_C") (pintype "passive"))
      (node (ref "LED3") (pin "C") (pinfunction "C_C") (pintype "passive"))
      (node (ref "LED4") (pin "C") (pinfunction "C_C") (pintype "passive"))
      (node (ref "LED5") (pin "C") (pinfunction "C_C") (pintype "passive"))
      (node (ref "LED6") (pin "C") (pinfunction "C_C") (pintype "passive"))
      (node (ref "R12") (pin "1") (pinfunction "1_1") (pintype "passive"))
      (node (ref "R2") (pin "1") (pinfunction "1_1") (pintype "passive"))
      (node (ref "R23") (pin "1") (pinfunction "1_1") (pintype "passive"))
      (node (ref "R27") (pin "2") (pinfunction "2_2") (pintype "passive"))
      (node (ref "R6") (pin "1") (pinfunction "1_1") (pintype "passive"))
      (node (ref "RN14") (pin "5") (pinfunction "2_5") (pintype "passive"))
      (node (ref "RN14") (pin "6") (pinfunction "2_6") (pintype "passive"))
      (node (ref "RN14") (pin "7") (pinfunction "2_7") (pintype "passive"))
      (node (ref "RN14") (pin "8") (pinfunction "2_8") (pintype "passive"))
      (node (ref "RN17") (pin "5") (pinfunction "2_5") (pintype "passive"))
      (node (ref "RN17") (pin "6") (pinfunction "2_6") (pintype "passive"))
      (node (ref "RN17") (pin "7") (pinfunction "2_7") (pintype "passive"))
      (node (ref "RN17") (pin "8") (pinfunction "2_8") (pintype "passive"))
      (node (ref "RN2") (pin "5") (pinfunction "2_5") (pintype "passive"))
      (node (ref "RN2") (pin "6") (pinfunction "2_6") (pintype "passive"))
      (node (ref "RN2") (pin "7") (pinfunction "2_7") (pintype "passive"))
      (node (ref "RN2") (pin "8") (pinfunction "2_8") (pintype "passive"))
      (node (ref "RN5") (pin "5") (pinfunction "2_5") (pintype "passive"))
      (node (ref "RN5") (pin "6") (pinfunction "2_6") (pintype "passive"))
      (node (ref "RN5") (pin "7") (pinfunction "2_7") (pintype "passive"))
      (node (ref "RN5") (pin "8") (pinfunction "2_8") (pintype "passive"))
      (node (ref "RN8") (pin "5") (pinfunction "2_5") (pintype "passive"))
      (node (ref "RN8") (pin "6") (pinfunction "2_6") (pintype "passive"))
      (node (ref "RN8") (pin "7") (pinfunction "2_7") (pintype "passive"))
      (node (ref "RN8") (pin "8") (pinfunction "2_8") (pintype "passive"))
      (node (ref "SJ_MS") (pin "1") (pinfunction "1_1") (pintype "passive"))
      (node (ref "U1") (pin "2") (pinfunction "GND_2") (pintype "power_in"))
      (node (ref "U10") (pin "10") (pinfunction "VREFCOM_10") (pintype "bidirectional"))
      (node (ref "U10") (pin "2") (pinfunction "DGND/DSS_2") (pintype "bidirectional"))
      (node (ref "U10") (pin "21") (pinfunction "AVSS_21") (pintype "bidirectional"))
      (node (ref "U10") (pin "3") (pinfunction "CLK_3") (pintype "bidirectional"))
      (node (ref "U11") (pin "10") (pinfunction "VREFCOM_10") (pintype "bidirectional"))
      (node (ref "U11") (pin "2") (pinfunction "DGND/DSS_2") (pintype "bidirectional"))
      (node (ref "U11") (pin "21") (pinfunction "AVSS_21") (pintype "bidirectional"))
      (node (ref "U11") (pin "3") (pinfunction "CLK_3") (pintype "bidirectional"))
      (node (ref "U12") (pin "10") (pinfunction "VREFCOM_10") (pintype "bidirectional"))
      (node (ref "U12") (pin "2") (pinfunction "DGND/DSS_2") (pintype "bidirectional"))
      (node (ref "U12") (pin "21") (pinfunction "AVSS_21") (pintype "bidirectional"))
      (node (ref "U12") (pin "3") (pinfunction "CLK_3") (pintype "bidirectional"))
      (node (ref "U13") (pin "2") (pinfunction "GND_2") (pintype "power_in"))
      (node (ref "U2") (pin "2") (pinfunction "GND_2") (pintype "power_in"))
      (node (ref "U3") (pin "10") (pinfunction "VREFCOM_10") (pintype "bidirectional"))
      (node (ref "U3") (pin "2") (pinfunction "DGND/DSS_2") (pintype "bidirectional"))
      (node (ref "U3") (pin "21") (pinfunction "AVSS_21") (pintype "bidirectional"))
      (node (ref "U3") (pin "3") (pinfunction "CLK_3") (pintype "bidirectional"))
      (node (ref "U4") (pin "10") (pinfunction "VREFCOM_10") (pintype "bidirectional"))
      (node (ref "U4") (pin "2") (pinfunction "DGND/DSS_2") (pintype "bidirectional"))
      (node (ref "U4") (pin "21") (pinfunction "AVSS_21") (pintype "bidirectional"))
      (node (ref "U4") (pin "3") (pinfunction "CLK_3") (pintype "bidirectional"))
      (node (ref "U5") (pin "10") (pinfunction "VREFCOM_10") (pintype "bidirectional"))
      (node (ref "U5") (pin "2") (pinfunction "DGND/DSS_2") (pintype "bidirectional"))
      (node (ref "U5") (pin "21") (pinfunction "AVSS_21") (pintype "bidirectional"))
      (node (ref "U5") (pin "3") (pinfunction "CLK_3") (pintype "bidirectional"))
      (node (ref "U6") (pin "3") (pinfunction "GND_3") (pintype "bidirectional"))
      (node (ref "U6") (pin "6") (pinfunction "GND_6") (pintype "bidirectional"))
      (node (ref "U7") (pin "10") (pinfunction "VSS_10") (pintype "bidirectional"))
      (node (ref "U8") (pin "10") (pinfunction "VSS_10") (pintype "bidirectional"))
      (node (ref "U9") (pin "114") (pinfunction "VSS_114") (pintype "bidirectional"))
      (node (ref "U9") (pin "122") (pinfunction "VSSDSI_122") (pintype "bidirectional"))
      (node (ref "U9") (pin "128") (pinfunction "VSSDSI2_128") (pintype "bidirectional"))
      (node (ref "U9") (pin "136") (pinfunction "VSS_136") (pintype "bidirectional"))
      (node (ref "U9") (pin "14") (pinfunction "VSS_14") (pintype "bidirectional"))
      (node (ref "U9") (pin "149") (pinfunction "VSS_149") (pintype "bidirectional"))
      (node (ref "U9") (pin "170") (pinfunction "VSS_170") (pintype "bidirectional"))
      (node (ref "U9") (pin "184") (pinfunction "VSS_184") (pintype "bidirectional"))
      (node (ref "U9") (pin "202") (pinfunction "VSS_202") (pintype "bidirectional"))
      (node (ref "U9") (pin "25") (pinfunction "VSS_25") (pintype "bidirectional"))
      (node (ref "U9") (pin "40") (pinfunction "VSSA_40") (pintype "bidirectional"))
      (node (ref "U9") (pin "51") (pinfunction "VSS_51") (pintype "bidirectional"))
      (node (ref "U9") (pin "60") (pinfunction "VSS_60") (pintype "bidirectional"))
      (node (ref "U9") (pin "72") (pinfunction "VSS_72") (pintype "bidirectional"))
      (node (ref "U9") (pin "82") (pinfunction "VSS_82") (pintype "bidirectional"))
      (node (ref "U9") (pin "93") (pinfunction "VSS_93") (pintype "bidirectional"))
      (node (ref "X1") (pin "1") (pinfunction "F_1") (pintype "passive"))
      (node (ref "X3") (pin "GND") (pinfunction "GND_GND") (pintype "bidirectional"))
      (node (ref "X_IN_1") (pin "GND@1") (pinfunction "GND4_GND@1") (pintype "power_in"))
      (node (ref "X_IN_1") (pin "GND@2") (pinfunction "GND3_GND@2") (pintype "power_in"))
      (node (ref "X_IN_1") (pin "GND@3") (pinfunction "GND2_GND@3") (pintype "power_in"))
      (node (ref "X_IN_1") (pin "GND@4") (pinfunction "GND1_GND@4") (pintype "power_in"))
      (node (ref "X_IN_10") (pin "GND@1") (pinfunction "GND4_GND@1") (pintype "power_in"))
      (node (ref "X_IN_10") (pin "GND@2") (pinfunction "GND3_GND@2") (pintype "power_in"))
      (node (ref "X_IN_10") (pin "GND@3") (pinfunction "GND2_GND@3") (pintype "power_in"))
      (node (ref "X_IN_10") (pin "GND@4") (pinfunction "GND1_GND@4") (pintype "power_in"))
      (node (ref "X_IN_11") (pin "GND@1") (pinfunction "GND4_GND@1") (pintype "power_in"))
      (node (ref "X_IN_11") (pin "GND@2") (pinfunction "GND3_GND@2") (pintype "power_in"))
      (node (ref "X_IN_11") (pin "GND@3") (pinfunction "GND2_GND@3") (pintype "power_in"))
      (node (ref "X_IN_11") (pin "GND@4") (pinfunction "GND1_GND@4") (pintype "power_in"))
      (node (ref "X_IN_12") (pin "GND@1") (pinfunction "GND4_GND@1") (pintype "power_in"))
      (node (ref "X_IN_12") (pin "GND@2") (pinfunction "GND3_GND@2") (pintype "power_in"))
      (node (ref "X_IN_12") (pin "GND@3") (pinfunction "GND2_GND@3") (pintype "power_in"))
      (node (ref "X_IN_12") (pin "GND@4") (pinfunction "GND1_GND@4") (pintype "power_in"))
      (node (ref "X_IN_13") (pin "GND@1") (pinfunction "GND4_GND@1") (pintype "power_in"))
      (node (ref "X_IN_13") (pin "GND@2") (pinfunction "GND3_GND@2") (pintype "power_in"))
      (node (ref "X_IN_13") (pin "GND@3") (pinfunction "GND2_GND@3") (pintype "power_in"))
      (node (ref "X_IN_13") (pin "GND@4") (pinfunction "GND1_GND@4") (pintype "power_in"))
      (node (ref "X_IN_14") (pin "GND@1") (pinfunction "GND4_GND@1") (pintype "power_in"))
      (node (ref "X_IN_14") (pin "GND@2") (pinfunction "GND3_GND@2") (pintype "power_in"))
      (node (ref "X_IN_14") (pin "GND@3") (pinfunction "GND2_GND@3") (pintype "power_in"))
      (node (ref "X_IN_14") (pin "GND@4") (pinfunction "GND1_GND@4") (pintype "power_in"))
      (node (ref "X_IN_15") (pin "GND@1") (pinfunction "GND4_GND@1") (pintype "power_in"))
      (node (ref "X_IN_15") (pin "GND@2") (pinfunction "GND3_GND@2") (pintype "power_in"))
      (node (ref "X_IN_15") (pin "GND@3") (pinfunction "GND2_GND@3") (pintype "power_in"))
      (node (ref "X_IN_15") (pin "GND@4") (pinfunction "GND1_GND@4") (pintype "power_in"))
      (node (ref "X_IN_2") (pin "GND@1") (pinfunction "GND4_GND@1") (pintype "power_in"))
      (node (ref "X_IN_2") (pin "GND@2") (pinfunction "GND3_GND@2") (pintype "power_in"))
      (node (ref "X_IN_2") (pin "GND@3") (pinfunction "GND2_GND@3") (pintype "power_in"))
      (node (ref "X_IN_2") (pin "GND@4") (pinfunction "GND1_GND@4") (pintype "power_in"))
      (node (ref "X_IN_3") (pin "GND@1") (pinfunction "GND4_GND@1") (pintype "power_in"))
      (node (ref "X_IN_3") (pin "GND@2") (pinfunction "GND3_GND@2") (pintype "power_in"))
      (node (ref "X_IN_3") (pin "GND@3") (pinfunction "GND2_GND@3") (pintype "power_in"))
      (node (ref "X_IN_3") (pin "GND@4") (pinfunction "GND1_GND@4") (pintype "power_in"))
      (node (ref "X_IN_4") (pin "GND@1") (pinfunction "GND4_GND@1") (pintype "power_in"))
      (node (ref "X_IN_4") (pin "GND@2") (pinfunction "GND3_GND@2") (pintype "power_in"))
      (node (ref "X_IN_4") (pin "GND@3") (pinfunction "GND2_GND@3") (pintype "power_in"))
      (node (ref "X_IN_4") (pin "GND@4") (pinfunction "GND1_GND@4") (pintype "power_in"))
      (node (ref "X_IN_5") (pin "GND@1") (pinfunction "GND4_GND@1") (pintype "power_in"))
      (node (ref "X_IN_5") (pin "GND@2") (pinfunction "GND3_GND@2") (pintype "power_in"))
      (node (ref "X_IN_5") (pin "GND@3") (pinfunction "GND2_GND@3") (pintype "power_in"))
      (node (ref "X_IN_5") (pin "GND@4") (pinfunction "GND1_GND@4") (pintype "power_in"))
      (node (ref "X_IN_6") (pin "GND@1") (pinfunction "GND4_GND@1") (pintype "power_in"))
      (node (ref "X_IN_6") (pin "GND@2") (pinfunction "GND3_GND@2") (pintype "power_in"))
      (node (ref "X_IN_6") (pin "GND@3") (pinfunction "GND2_GND@3") (pintype "power_in"))
      (node (ref "X_IN_6") (pin "GND@4") (pinfunction "GND1_GND@4") (pintype "power_in"))
      (node (ref "X_IN_7") (pin "GND@1") (pinfunction "GND4_GND@1") (pintype "power_in"))
      (node (ref "X_IN_7") (pin "GND@2") (pinfunction "GND3_GND@2") (pintype "power_in"))
      (node (ref "X_IN_7") (pin "GND@3") (pinfunction "GND2_GND@3") (pintype "power_in"))
      (node (ref "X_IN_7") (pin "GND@4") (pinfunction "GND1_GND@4") (pintype "power_in"))
      (node (ref "X_IN_8") (pin "GND@1") (pinfunction "GND4_GND@1") (pintype "power_in"))
      (node (ref "X_IN_8") (pin "GND@2") (pinfunction "GND3_GND@2") (pintype "power_in"))
      (node (ref "X_IN_8") (pin "GND@3") (pinfunction "GND2_GND@3") (pintype "power_in"))
      (node (ref "X_IN_8") (pin "GND@4") (pinfunction "GND1_GND@4") (pintype "power_in"))
      (node (ref "X_IN_9") (pin "GND@1") (pinfunction "GND4_GND@1") (pintype "power_in"))
      (node (ref "X_IN_9") (pin "GND@2") (pinfunction "GND3_GND@2") (pintype "power_in"))
      (node (ref "X_IN_9") (pin "GND@3") (pinfunction "GND2_GND@3") (pintype "power_in"))
      (node (ref "X_IN_9") (pin "GND@4") (pinfunction "GND1_GND@4") (pintype "power_in"))
      (node (ref "X_PROG") (pin "10") (pinfunction "10_10") (pintype "passive"))
      (node (ref "X_PROG") (pin "14") (pinfunction "14_14") (pintype "passive"))
      (node (ref "X_PROG") (pin "2") (pinfunction "2_2") (pintype "passive"))
      (node (ref "X_PROG") (pin "4") (pinfunction "4_4") (pintype "passive"))
      (node (ref "X_PROG") (pin "6") (pinfunction "6_6") (pintype "passive"))
      (node (ref "X_PROG") (pin "8") (pinfunction "8_8") (pintype "passive"))
    )
    (net (code "51") (name "INTERSPU_RX") (class "Default")
      (node (ref "D11") (pin "C") (pinfunction "C_C") (pintype "passive"))
      (node (ref "U9") (pin "166") (pinfunction "PD2_166") (pintype "bidirectional"))
      (node (ref "X1") (pin "4") (pinfunction "F_4") (pintype "passive"))
    )
    (net (code "52") (name "INTERSPU_TX") (class "Default")
      (node (ref "D12") (pin "C") (pinfunction "C_C") (pintype "passive"))
      (node (ref "U9") (pin "163") (pinfunction "PC12_163") (pintype "bidirectional"))
      (node (ref "X1") (pin "3") (pinfunction "F_3") (pintype "passive"))
    )
    (net (code "53") (name "IN_DMS_1") (class "Default")
      (node (ref "IC2") (pin "2") (pinfunction "-IN_2") (pintype "input"))
      (node (ref "RN3") (pin "4") (pinfunction "1_4") (pintype "passive"))
      (node (ref "X_IN_1") (pin "P") (pinfunction "ANT_P") (pintype "bidirectional"))
    )
    (net (code "54") (name "IN_DMS_2") (class "Default")
      (node (ref "IC2") (pin "6") (pinfunction "-IN_6") (pintype "input"))
      (node (ref "RN3") (pin "3") (pinfunction "1_3") (pintype "passive"))
      (node (ref "X_IN_2") (pin "P") (pinfunction "ANT_P") (pintype "bidirectional"))
    )
    (net (code "55") (name "IN_DMS_3") (class "Default")
      (node (ref "IC2") (pin "9") (pinfunction "-IN_9") (pintype "input"))
      (node (ref "RN3") (pin "2") (pinfunction "1_2") (pintype "passive"))
      (node (ref "X_IN_3") (pin "P") (pinfunction "ANT_P") (pintype "bidirectional"))
    )
    (net (code "56") (name "IN_DMS_4") (class "Default")
      (node (ref "IC2") (pin "13") (pinfunction "-IN_13") (pintype "input"))
      (node (ref "RN3") (pin "1") (pinfunction "1_1") (pintype "passive"))
      (node (ref "X_IN_4") (pin "P") (pinfunction "ANT_P") (pintype "bidirectional"))
    )
    (net (code "57") (name "IN_DMS_5") (class "Default")
      (node (ref "IC3") (pin "2") (pinfunction "-IN_2") (pintype "input"))
      (node (ref "RN6") (pin "4") (pinfunction "1_4") (pintype "passive"))
      (node (ref "X_IN_5") (pin "P") (pinfunction "ANT_P") (pintype "bidirectional"))
    )
    (net (code "58") (name "IN_DMS_6") (class "Default")
      (node (ref "IC3") (pin "6") (pinfunction "-IN_6") (pintype "input"))
      (node (ref "RN6") (pin "3") (pinfunction "1_3") (pintype "passive"))
      (node (ref "X_IN_6") (pin "P") (pinfunction "ANT_P") (pintype "bidirectional"))
    )
    (net (code "59") (name "IN_DMS_7") (class "Default")
      (node (ref "IC9") (pin "2") (pinfunction "-IN_2") (pintype "input"))
      (node (ref "RN15") (pin "4") (pinfunction "1_4") (pintype "passive"))
      (node (ref "X_IN_10") (pin "P") (pinfunction "ANT_P") (pintype "bidirectional"))
    )
    (net (code "60") (name "IN_DMS_7_NC") (class "Default")
      (node (ref "IC3") (pin "9") (pinfunction "-IN_9") (pintype "input"))
      (node (ref "RN6") (pin "2") (pinfunction "1_2") (pintype "passive"))
    )
    (net (code "61") (name "IN_DMS_8") (class "Default")
      (node (ref "IC9") (pin "6") (pinfunction "-IN_6") (pintype "input"))
      (node (ref "RN15") (pin "3") (pinfunction "1_3") (pintype "passive"))
      (node (ref "X_IN_11") (pin "P") (pinfunction "ANT_P") (pintype "bidirectional"))
    )
    (net (code "62") (name "IN_DMS_8_NC") (class "Default")
      (node (ref "IC3") (pin "13") (pinfunction "-IN_13") (pintype "input"))
      (node (ref "RN6") (pin "1") (pinfunction "1_1") (pintype "passive"))
    )
    (net (code "63") (name "IN_DMS_9") (class "Default")
      (node (ref "IC9") (pin "9") (pinfunction "-IN_9") (pintype "input"))
      (node (ref "RN15") (pin "2") (pinfunction "1_2") (pintype "passive"))
      (node (ref "X_IN_12") (pin "P") (pinfunction "ANT_P") (pintype "bidirectional"))
    )
    (net (code "64") (name "IN_DMS_10") (class "Default")
      (node (ref "IC9") (pin "13") (pinfunction "-IN_13") (pintype "input"))
      (node (ref "RN15") (pin "1") (pinfunction "1_1") (pintype "passive"))
      (node (ref "X_IN_13") (pin "P") (pinfunction "ANT_P") (pintype "bidirectional"))
    )
    (net (code "65") (name "IN_DMS_11") (class "Default")
      (node (ref "IC10") (pin "2") (pinfunction "-IN_2") (pintype "input"))
      (node (ref "RN18") (pin "4") (pinfunction "1_4") (pintype "passive"))
      (node (ref "X_IN_14") (pin "P") (pinfunction "ANT_P") (pintype "bidirectional"))
    )
    (net (code "66") (name "IN_DMS_12") (class "Default")
      (node (ref "IC10") (pin "6") (pinfunction "-IN_6") (pintype "input"))
      (node (ref "RN18") (pin "3") (pinfunction "1_3") (pintype "passive"))
      (node (ref "X_IN_15") (pin "P") (pinfunction "ANT_P") (pintype "bidirectional"))
    )
    (net (code "67") (name "IN_PT_1") (class "Default")
      (node (ref "IC4") (pin "2") (pinfunction "-IN_2") (pintype "input"))
      (node (ref "RN9") (pin "4") (pinfunction "1_4") (pintype "passive"))
      (node (ref "X_IN_7") (pin "P") (pinfunction "ANT_P") (pintype "bidirectional"))
    )
    (net (code "68") (name "IN_PT_2") (class "Default")
      (node (ref "IC4") (pin "6") (pinfunction "-IN_6") (pintype "input"))
      (node (ref "RN9") (pin "3") (pinfunction "1_3") (pintype "passive"))
      (node (ref "X_IN_8") (pin "P") (pinfunction "ANT_P") (pintype "bidirectional"))
    )
    (net (code "69") (name "IN_PT_3") (class "Default")
      (node (ref "IC4") (pin "9") (pinfunction "-IN_9") (pintype "input"))
      (node (ref "RN9") (pin "2") (pinfunction "1_2") (pintype "passive"))
      (node (ref "X_IN_9") (pin "P") (pinfunction "ANT_P") (pintype "bidirectional"))
    )
    (net (code "70") (name "IN_PT_4_NC") (class "Default")
      (node (ref "IC4") (pin "13") (pinfunction "-IN_13") (pintype "input"))
      (node (ref "RN9") (pin "1") (pinfunction "1_1") (pintype "passive"))
    )
    (net (code "71") (name "LED_1") (class "Default")
      (node (ref "RN10") (pin "1") (pinfunction "1_1") (pintype "passive"))
      (node (ref "U9") (pin "24") (pinfunction "PF5_24") (pintype "bidirectional"))
    )
    (net (code "72") (name "LED_2") (class "Default")
      (node (ref "RN10") (pin "2") (pinfunction "1_2") (pintype "passive"))
      (node (ref "U9") (pin "23") (pinfunction "PF4_23") (pintype "bidirectional"))
    )
    (net (code "73") (name "LED_3") (class "Default")
      (node (ref "RN10") (pin "3") (pinfunction "1_3") (pintype "passive"))
      (node (ref "U9") (pin "22") (pinfunction "PF3_22") (pintype "bidirectional"))
    )
    (net (code "74") (name "LED_4") (class "Default")
      (node (ref "RN10") (pin "4") (pinfunction "1_4") (pintype "passive"))
      (node (ref "U9") (pin "21") (pinfunction "PI14_21") (pintype "bidirectional"))
    )
    (net (code "75") (name "LO") (class "Default")
      (node (ref "IC7") (pin "2") (pinfunction "C1_2") (pintype "bidirectional"))
      (node (ref "X1") (pin "7") (pinfunction "F_7") (pintype "passive"))
      (node (ref "X2") (pin "5") (pinfunction "F_5") (pintype "passive"))
    )
    (net (code "76") (name "LO_OPT") (class "Default")
      (node (ref "D7") (pin "C") (pinfunction "C_C") (pintype "passive"))
      (node (ref "IC7") (pin "8") (pinfunction "COL1_8") (pintype "input"))
      (node (ref "RN12") (pin "6") (pinfunction "2_6") (pintype "passive"))
      (node (ref "U9") (pin "208") (pinfunction "PI7_208") (pintype "bidirectional"))
    )
    (net (code "77") (name "MS_SEL") (class "Default")
      (node (ref "JP_MS") (pin "2") (pinfunction "2_2") (pintype "passive"))
      (node (ref "R29") (pin "1") (pinfunction "1_1") (pintype "passive"))
      (node (ref "SJ_MS") (pin "2") (pinfunction "2_2") (pintype "passive"))
      (node (ref "U9") (pin "129") (pinfunction "PG2_129") (pintype "bidirectional"))
    )
    (net (code "78") (name "NRST") (class "Default")
      (node (ref "C18") (pin "1") (pinfunction "1_1") (pintype "passive"))
      (node (ref "JP1") (pin "1") (pinfunction "1_1") (pintype "passive"))
      (node (ref "R26") (pin "1") (pinfunction "1_1") (pintype "passive"))
      (node (ref "U9") (pin "34") (pinfunction "NRST_34") (pintype "bidirectional"))
    )
    (net (code "79") (name "Net-(C44-Pad1)") (class "Default")
      (node (ref "C44") (pin "1") (pinfunction "1_1") (pintype "passive"))
      (node (ref "R10") (pin "1") (pinfunction "1_1") (pintype "passive"))
      (node (ref "R15") (pin "2") (pinfunction "2_2") (pintype "passive"))
    )
    (net (code "80") (name "Net-(IC2A-+IN)") (class "Default")
      (node (ref "IC2") (pin "3") (pinfunction "+IN_3") (pintype "input"))
      (node (ref "RN1") (pin "5") (pinfunction "2_5") (pintype "passive"))
      (node (ref "RN2") (pin "4") (pinfunction "1_4") (pintype "passive"))
    )
    (net (code "81") (name "Net-(IC2B-+IN)") (class "Default")
      (node (ref "IC2") (pin "5") (pinfunction "+IN_5") (pintype "input"))
      (node (ref "RN1") (pin "6") (pinfunction "2_6") (pintype "passive"))
      (node (ref "RN2") (pin "3") (pinfunction "1_3") (pintype "passive"))
    )
    (net (code "82") (name "Net-(IC2C-+IN)") (class "Default")
      (node (ref "IC2") (pin "10") (pinfunction "+IN_10") (pintype "input"))
      (node (ref "RN1") (pin "7") (pinfunction "2_7") (pintype "passive"))
      (node (ref "RN2") (pin "2") (pinfunction "1_2") (pintype "passive"))
    )
    (net (code "83") (name "Net-(IC2D-+IN)") (class "Default")
      (node (ref "IC2") (pin "12") (pinfunction "+IN_12") (pintype "input"))
      (node (ref "RN1") (pin "8") (pinfunction "2_8") (pintype "passive"))
      (node (ref "RN2") (pin "1") (pinfunction "1_1") (pintype "passive"))
    )
    (net (code "84") (name "Net-(IC2E-V+)") (class "Default")
      (node (ref "C3") (pin "2") (pinfunction "2_2") (pintype "passive"))
      (node (ref "C5") (pin "+") (pinfunction "+_+") (pintype "passive"))
      (node (ref "IC2") (pin "4") (pinfunction "V+_4") (pintype "power_in"))
      (node (ref "L1") (pin "2") (pinfunction "2_2") (pintype "passive"))
    )
    (net (code "85") (name "Net-(IC3A-+IN)") (class "Default")
      (node (ref "IC3") (pin "3") (pinfunction "+IN_3") (pintype "input"))
      (node (ref "RN4") (pin "5") (pinfunction "2_5") (pintype "passive"))
      (node (ref "RN5") (pin "4") (pinfunction "1_4") (pintype "passive"))
    )
    (net (code "86") (name "Net-(IC3B-+IN)") (class "Default")
      (node (ref "IC3") (pin "5") (pinfunction "+IN_5") (pintype "input"))
      (node (ref "RN4") (pin "6") (pinfunction "2_6") (pintype "passive"))
      (node (ref "RN5") (pin "3") (pinfunction "1_3") (pintype "passive"))
    )
    (net (code "87") (name "Net-(IC3C-+IN)") (class "Default")
      (node (ref "IC3") (pin "10") (pinfunction "+IN_10") (pintype "input"))
      (node (ref "RN4") (pin "7") (pinfunction "2_7") (pintype "passive"))
      (node (ref "RN5") (pin "2") (pinfunction "1_2") (pintype "passive"))
    )
    (net (code "88") (name "Net-(IC3D-+IN)") (class "Default")
      (node (ref "IC3") (pin "12") (pinfunction "+IN_12") (pintype "input"))
      (node (ref "RN4") (pin "8") (pinfunction "2_8") (pintype "passive"))
      (node (ref "RN5") (pin "1") (pinfunction "1_1") (pintype "passive"))
    )
    (net (code "89") (name "Net-(IC3E-V+)") (class "Default")
      (node (ref "C10") (pin "+") (pinfunction "+_+") (pintype "passive"))
      (node (ref "C6") (pin "2") (pinfunction "2_2") (pintype "passive"))
      (node (ref "IC3") (pin "4") (pinfunction "V+_4") (pintype "power_in"))
      (node (ref "L2") (pin "2") (pinfunction "2_2") (pintype "passive"))
    )
    (net (code "90") (name "Net-(IC4A-+IN)") (class "Default")
      (node (ref "IC4") (pin "3") (pinfunction "+IN_3") (pintype "input"))
      (node (ref "RN7") (pin "5") (pinfunction "2_5") (pintype "passive"))
      (node (ref "RN8") (pin "4") (pinfunction "1_4") (pintype "passive"))
    )
    (net (code "91") (name "Net-(IC4B-+IN)") (class "Default")
      (node (ref "IC4") (pin "5") (pinfunction "+IN_5") (pintype "input"))
      (node (ref "RN7") (pin "6") (pinfunction "2_6") (pintype "passive"))
      (node (ref "RN8") (pin "3") (pinfunction "1_3") (pintype "passive"))
    )
    (net (code "92") (name "Net-(IC4C-+IN)") (class "Default")
      (node (ref "IC4") (pin "10") (pinfunction "+IN_10") (pintype "input"))
      (node (ref "RN7") (pin "7") (pinfunction "2_7") (pintype "passive"))
      (node (ref "RN8") (pin "2") (pinfunction "1_2") (pintype "passive"))
    )
    (net (code "93") (name "Net-(IC4D-+IN)") (class "Default")
      (node (ref "IC4") (pin "12") (pinfunction "+IN_12") (pintype "input"))
      (node (ref "RN7") (pin "8") (pinfunction "2_8") (pintype "passive"))
      (node (ref "RN8") (pin "1") (pinfunction "1_1") (pintype "passive"))
    )
    (net (code "94") (name "Net-(IC4E-V+)") (class "Default")
      (node (ref "C13") (pin "2") (pinfunction "2_2") (pintype "passive"))
      (node (ref "C15") (pin "+") (pinfunction "+_+") (pintype "passive"))
      (node (ref "IC4") (pin "4") (pinfunction "V+_4") (pintype "power_in"))
      (node (ref "L3") (pin "2") (pinfunction "2_2") (pintype "passive"))
    )
    (net (code "95") (name "Net-(IC6-A1)") (class "Default")
      (node (ref "IC6") (pin "1") (pinfunction "A1_1") (pintype "bidirectional"))
      (node (ref "RN11") (pin "6") (pinfunction "2_6") (pintype "passive"))
    )
    (net (code "96") (name "Net-(IC6-A2)") (class "Default")
      (node (ref "IC6") (pin "3") (pinfunction "A2_3") (pintype "bidirectional"))
      (node (ref "RN11") (pin "5") (pinfunction "2_5") (pintype "passive"))
    )
    (net (code "97") (name "Net-(IC7-A1)") (class "Default")
      (node (ref "IC7") (pin "1") (pinfunction "A1_1") (pintype "bidirectional"))
      (node (ref "RN11") (pin "8") (pinfunction "2_8") (pintype "passive"))
    )
    (net (code "98") (name "Net-(IC7-A2)") (class "Default")
      (node (ref "IC7") (pin "3") (pinfunction "A2_3") (pintype "bidirectional"))
      (node (ref "RN11") (pin "7") (pinfunction "2_7") (pintype "passive"))
    )
    (net (code "99") (name "Net-(IC7-COL2)") (class "Default")
      (node (ref "IC7") (pin "6") (pinfunction "COL2_6") (pintype "input"))
      (node (ref "RN12") (pin "5") (pinfunction "2_5") (pintype "passive"))
    )
    (net (code "100") (name "Net-(IC8-C1)") (class "Default")
      (node (ref "IC8") (pin "2") (pinfunction "C1_2") (pintype "bidirectional"))
      (node (ref "R11") (pin "2") (pinfunction "2_2") (pintype "passive"))
    )
    (net (code "101") (name "Net-(IC8-C2)") (class "Default")
      (node (ref "IC8") (pin "4") (pinfunction "C2_4") (pintype "bidirectional"))
      (node (ref "R12") (pin "2") (pinfunction "2_2") (pintype "passive"))
    )
    (net (code "102") (name "Net-(IC9A-+IN)") (class "Default")
      (node (ref "IC9") (pin "3") (pinfunction "+IN_3") (pintype "input"))
      (node (ref "RN13") (pin "5") (pinfunction "2_5") (pintype "passive"))
      (node (ref "RN14") (pin "4") (pinfunction "1_4") (pintype "passive"))
    )
    (net (code "103") (name "Net-(IC9B-+IN)") (class "Default")
      (node (ref "IC9") (pin "5") (pinfunction "+IN_5") (pintype "input"))
      (node (ref "RN13") (pin "6") (pinfunction "2_6") (pintype "passive"))
      (node (ref "RN14") (pin "3") (pinfunction "1_3") (pintype "passive"))
    )
    (net (code "104") (name "Net-(IC9C-+IN)") (class "Default")
      (node (ref "IC9") (pin "10") (pinfunction "+IN_10") (pintype "input"))
      (node (ref "RN13") (pin "7") (pinfunction "2_7") (pintype "passive"))
      (node (ref "RN14") (pin "2") (pinfunction "1_2") (pintype "passive"))
    )
    (net (code "105") (name "Net-(IC9D-+IN)") (class "Default")
      (node (ref "IC9") (pin "12") (pinfunction "+IN_12") (pintype "input"))
      (node (ref "RN13") (pin "8") (pinfunction "2_8") (pintype "passive"))
      (node (ref "RN14") (pin "1") (pinfunction "1_1") (pintype "passive"))
    )
    (net (code "106") (name "Net-(IC9E-V+)") (class "Default")
      (node (ref "C54") (pin "2") (pinfunction "2_2") (pintype "passive"))
      (node (ref "IC9") (pin "4") (pinfunction "V+_4") (pintype "power_in"))
      (node (ref "L4") (pin "2") (pinfunction "2_2") (pintype "passive"))
    )
    (net (code "107") (name "Net-(IC10A-+IN)") (class "Default")
      (node (ref "IC10") (pin "3") (pinfunction "+IN_3") (pintype "input"))
      (node (ref "RN16") (pin "5") (pinfunction "2_5") (pintype "passive"))
      (node (ref "RN17") (pin "4") (pinfunction "1_4") (pintype "passive"))
    )
    (net (code "108") (name "Net-(IC10B-+IN)") (class "Default")
      (node (ref "IC10") (pin "5") (pinfunction "+IN_5") (pintype "input"))
      (node (ref "RN16") (pin "6") (pinfunction "2_6") (pintype "passive"))
      (node (ref "RN17") (pin "3") (pinfunction "1_3") (pintype "passive"))
    )
    (net (code "109") (name "Net-(IC10E-V+)") (class "Default")
      (node (ref "C57") (pin "2") (pinfunction "2_2") (pintype "passive"))
      (node (ref "IC10") (pin "4") (pinfunction "V+_4") (pintype "power_in"))
      (node (ref "L5") (pin "2") (pinfunction "2_2") (pintype "passive"))
    )
    (net (code "110") (name "Net-(IC13-XI)") (class "Default")
      (node (ref "C1") (pin "1") (pinfunction "1_1") (pintype "passive"))
      (node (ref "IC13") (pin "7") (pinfunction "XI_7") (pintype "bidirectional"))
      (node (ref "Q1") (pin "1") (pinfunction "1_1") (pintype "passive"))
    )
    (net (code "111") (name "Net-(IC13-XO)") (class "Default")
      (node (ref "C2") (pin "1") (pinfunction "1_1") (pintype "passive"))
      (node (ref "IC13") (pin "8") (pinfunction "XO_8") (pintype "bidirectional"))
      (node (ref "Q1") (pin "2") (pinfunction "2_2") (pintype "passive"))
    )
    (net (code "112") (name "Net-(LED5-PadA)") (class "Default")
      (node (ref "LED5") (pin "A") (pinfunction "A_A") (pintype "passive"))
      (node (ref "R18") (pin "1") (pinfunction "1_1") (pintype "passive"))
    )
    (net (code "113") (name "Net-(LED6-PadA)") (class "Default")
      (node (ref "LED6") (pin "A") (pinfunction "A_A") (pintype "passive"))
      (node (ref "R19") (pin "1") (pinfunction "1_1") (pintype "passive"))
    )
    (net (code "114") (name "Net-(LED7-PadA)") (class "Default")
      (node (ref "LED7") (pin "A") (pinfunction "A_A") (pintype "passive"))
      (node (ref "R20") (pin "1") (pinfunction "1_1") (pintype "passive"))
    )
    (net (code "115") (name "Net-(LED8-PadA)") (class "Default")
      (node (ref "LED8") (pin "A") (pinfunction "A_A") (pintype "passive"))
      (node (ref "R21") (pin "1") (pinfunction "1_1") (pintype "passive"))
    )
    (net (code "116") (name "Net-(R1-Pad2)") (class "Default")
      (node (ref "R1") (pin "2") (pinfunction "2_2") (pintype "passive"))
      (node (ref "R3") (pin "1") (pinfunction "1_1") (pintype "passive"))
      (node (ref "R4") (pin "2") (pinfunction "2_2") (pintype "passive"))
    )
    (net (code "117") (name "Net-(R2-Pad2)") (class "Default")
      (node (ref "R2") (pin "2") (pinfunction "2_2") (pintype "passive"))
      (node (ref "R4") (pin "1") (pinfunction "1_1") (pintype "passive"))
    )
    (net (code "118") (name "Net-(R5-Pad2)") (class "Default")
      (node (ref "R5") (pin "2") (pinfunction "2_2") (pintype "passive"))
      (node (ref "R7") (pin "1") (pinfunction "1_1") (pintype "passive"))
      (node (ref "R8") (pin "2") (pinfunction "2_2") (pintype "passive"))
    )
    (net (code "119") (name "Net-(R6-Pad2)") (class "Default")
      (node (ref "R6") (pin "2") (pinfunction "2_2") (pintype "passive"))
      (node (ref "R8") (pin "1") (pinfunction "1_1") (pintype "passive"))
    )
    (net (code "120") (name "Net-(R22-Pad2)") (class "Default")
      (node (ref "R22") (pin "2") (pinfunction "2_2") (pintype "passive"))
      (node (ref "R24") (pin "1") (pinfunction "1_1") (pintype "passive"))
      (node (ref "R25") (pin "2") (pinfunction "2_2") (pintype "passive"))
    )
    (net (code "121") (name "Net-(R23-Pad2)") (class "Default")
      (node (ref "R23") (pin "2") (pinfunction "2_2") (pintype "passive"))
      (node (ref "R25") (pin "1") (pinfunction "1_1") (pintype "passive"))
    )
    (net (code "122") (name "Net-(RN10A-2)") (class "Default")
      (node (ref "LED1") (pin "A") (pinfunction "A_A") (pintype "passive"))
      (node (ref "RN10") (pin "8") (pinfunction "2_8") (pintype "passive"))
    )
    (net (code "123") (name "Net-(RN10B-2)") (class "Default")
      (node (ref "LED2") (pin "A") (pinfunction "A_A") (pintype "passive"))
      (node (ref "RN10") (pin "7") (pinfunction "2_7") (pintype "passive"))
    )
    (net (code "124") (name "Net-(RN10C-2)") (class "Default")
      (node (ref "LED3") (pin "A") (pinfunction "A_A") (pintype "passive"))
      (node (ref "RN10") (pin "6") (pinfunction "2_6") (pintype "passive"))
    )
    (net (code "125") (name "Net-(RN10D-2)") (class "Default")
      (node (ref "LED4") (pin "A") (pinfunction "A_A") (pintype "passive"))
      (node (ref "RN10") (pin "5") (pinfunction "2_5") (pintype "passive"))
    )
    (net (code "126") (name "Net-(RN16A-2)") (class "Default")
      (node (ref "RN16") (pin "8") (pinfunction "2_8") (pintype "passive"))
      (node (ref "RN17") (pin "1") (pinfunction "1_1") (pintype "passive"))
    )
    (net (code "127") (name "Net-(RN16B-2)") (class "Default")
      (node (ref "RN16") (pin "7") (pinfunction "2_7") (pintype "passive"))
      (node (ref "RN17") (pin "2") (pinfunction "1_2") (pintype "passive"))
    )
    (net (code "128") (name "Net-(U1-TRIM)") (class "Default")
      (node (ref "R1") (pin "1") (pinfunction "1_1") (pintype "passive"))
      (node (ref "U1") (pin "5") (pinfunction "TRIM_5") (pintype "passive"))
    )
    (net (code "129") (name "Net-(U2-TRIM)") (class "Default")
      (node (ref "R5") (pin "1") (pinfunction "1_1") (pintype "passive"))
      (node (ref "U2") (pin "5") (pinfunction "TRIM_5") (pintype "passive"))
    )
    (net (code "130") (name "Net-(U3-VREFOUT)") (class "Default")
      (node (ref "C21") (pin "1") (pinfunction "1_1") (pintype "passive"))
      (node (ref "U3") (pin "9") (pinfunction "VREFOUT_9") (pintype "bidirectional"))
    )
    (net (code "131") (name "Net-(U4-VREFOUT)") (class "Default")
      (node (ref "C24") (pin "1") (pinfunction "1_1") (pintype "passive"))
      (node (ref "U4") (pin "9") (pinfunction "VREFOUT_9") (pintype "bidirectional"))
    )
    (net (code "132") (name "Net-(U5-VREFOUT)") (class "Default")
      (node (ref "C27") (pin "1") (pinfunction "1_1") (pintype "passive"))
      (node (ref "U5") (pin "9") (pinfunction "VREFOUT_9") (pintype "bidirectional"))
    )
    (net (code "133") (name "Net-(U9-BOOT0)") (class "Default")
      (node (ref "R27") (pin "1") (pinfunction "1_1") (pintype "passive"))
      (node (ref "R28") (pin "2") (pinfunction "2_2") (pintype "passive"))
      (node (ref "U9") (pin "197") (pinfunction "BOOT0_197") (pintype "bidirectional"))
    )
    (net (code "134") (name "Net-(U9-VCAPDSI)") (class "Default")
      (node (ref "U9") (pin "119") (pinfunction "VCAPDSI_119") (pintype "bidirectional"))
      (node (ref "U9") (pin "125") (pinfunction "VDD12DSI_125") (pintype "bidirectional"))
    )
    (net (code "135") (name "Net-(U9-VCAP_1)") (class "Default")
      (node (ref "C17") (pin "2") (pinfunction "2_2") (pintype "passive"))
      (node (ref "U9") (pin "92") (pinfunction "VCAP_1_92") (pintype "bidirectional"))
    )
    (net (code "136") (name "Net-(U9-VCAP_2)") (class "Default")
      (node (ref "C16") (pin "2") (pinfunction "2_2") (pintype "passive"))
      (node (ref "U9") (pin "148") (pinfunction "VCAP_2_148") (pintype "bidirectional"))
    )
    (net (code "137") (name "Net-(U10-VREFOUT)") (class "Default")
      (node (ref "C47") (pin "1") (pinfunction "1_1") (pintype "passive"))
      (node (ref "U10") (pin "9") (pinfunction "VREFOUT_9") (pintype "bidirectional"))
    )
    (net (code "138") (name "Net-(U11-VREFOUT)") (class "Default")
      (node (ref "C50") (pin "1") (pinfunction "1_1") (pintype "passive"))
      (node (ref "U11") (pin "9") (pinfunction "VREFOUT_9") (pintype "bidirectional"))
    )
    (net (code "139") (name "Net-(U12-VREFOUT)") (class "Default")
      (node (ref "C53") (pin "1") (pinfunction "1_1") (pintype "passive"))
      (node (ref "U12") (pin "9") (pinfunction "VREFOUT_9") (pintype "bidirectional"))
    )
    (net (code "140") (name "Net-(U13-TRIM)") (class "Default")
      (node (ref "R22") (pin "1") (pinfunction "1_1") (pintype "passive"))
      (node (ref "U13") (pin "5") (pinfunction "TRIM_5") (pintype "passive"))
    )
    (net (code "141") (name "OUT_DMS_1") (class "Default")
      (node (ref "IC2") (pin "1") (pinfunction "OUT_1") (pintype "output"))
      (node (ref "RN3") (pin "5") (pinfunction "2_5") (pintype "passive"))
      (node (ref "U4") (pin "11") (pinfunction "AIN0/IEXC_11") (pintype "bidirectional"))
    )
    (net (code "142") (name "OUT_DMS_2") (class "Default")
      (node (ref "IC2") (pin "7") (pinfunction "OUT_7") (pintype "output"))
      (node (ref "RN3") (pin "6") (pinfunction "2_6") (pintype "passive"))
      (node (ref "U4") (pin "17") (pinfunction "AIN2/IEXC/GPIO2_17") (pintype "bidirectional"))
    )
    (net (code "143") (name "OUT_DMS_3") (class "Default")
      (node (ref "IC2") (pin "8") (pinfunction "OUT_8") (pintype "output"))
      (node (ref "RN3") (pin "7") (pinfunction "2_7") (pintype "passive"))
      (node (ref "U3") (pin "11") (pinfunction "AIN0/IEXC_11") (pintype "bidirectional"))
    )
    (net (code "144") (name "OUT_DMS_4") (class "Default")
      (node (ref "IC2") (pin "14") (pinfunction "OUT_14") (pintype "output"))
      (node (ref "RN3") (pin "8") (pinfunction "2_8") (pintype "passive"))
      (node (ref "U3") (pin "17") (pinfunction "AIN2/IEXC/GPIO2_17") (pintype "bidirectional"))
    )
    (net (code "145") (name "OUT_DMS_5") (class "Default")
      (node (ref "IC3") (pin "1") (pinfunction "OUT_1") (pintype "output"))
      (node (ref "RN6") (pin "5") (pinfunction "2_5") (pintype "passive"))
      (node (ref "U5") (pin "11") (pinfunction "AIN0/IEXC_11") (pintype "bidirectional"))
    )
    (net (code "146") (name "OUT_DMS_6") (class "Default")
      (node (ref "IC3") (pin "7") (pinfunction "OUT_7") (pintype "output"))
      (node (ref "RN6") (pin "6") (pinfunction "2_6") (pintype "passive"))
      (node (ref "U5") (pin "17") (pinfunction "AIN2/IEXC/GPIO2_17") (pintype "bidirectional"))
    )
    (net (code "147") (name "OUT_DMS_7") (class "Default")
      (node (ref "IC9") (pin "1") (pinfunction "OUT_1") (pintype "output"))
      (node (ref "RN15") (pin "5") (pinfunction "2_5") (pintype "passive"))
      (node (ref "U11") (pin "11") (pinfunction "AIN0/IEXC_11") (pintype "bidirectional"))
    )
    (net (code "148") (name "OUT_DMS_7_NC") (class "Default")
      (node (ref "IC3") (pin "8") (pinfunction "OUT_8") (pintype "output"))
      (node (ref "RN6") (pin "7") (pinfunction "2_7") (pintype "passive"))
    )
    (net (code "149") (name "OUT_DMS_8") (class "Default")
      (node (ref "IC9") (pin "7") (pinfunction "OUT_7") (pintype "output"))
      (node (ref "RN15") (pin "6") (pinfunction "2_6") (pintype "passive"))
      (node (ref "U11") (pin "17") (pinfunction "AIN2/IEXC/GPIO2_17") (pintype "bidirectional"))
    )
    (net (code "150") (name "OUT_DMS_8_NC") (class "Default")
      (node (ref "IC3") (pin "14") (pinfunction "OUT_14") (pintype "output"))
      (node (ref "RN6") (pin "8") (pinfunction "2_8") (pintype "passive"))
    )
    (net (code "151") (name "OUT_DMS_9") (class "Default")
      (node (ref "IC9") (pin "8") (pinfunction "OUT_8") (pintype "output"))
      (node (ref "RN15") (pin "7") (pinfunction "2_7") (pintype "passive"))
      (node (ref "U10") (pin "11") (pinfunction "AIN0/IEXC_11") (pintype "bidirectional"))
    )
    (net (code "152") (name "OUT_DMS_10") (class "Default")
      (node (ref "IC9") (pin "14") (pinfunction "OUT_14") (pintype "output"))
      (node (ref "RN15") (pin "8") (pinfunction "2_8") (pintype "passive"))
      (node (ref "U10") (pin "17") (pinfunction "AIN2/IEXC/GPIO2_17") (pintype "bidirectional"))
    )
    (net (code "153") (name "OUT_DMS_11") (class "Default")
      (node (ref "IC10") (pin "1") (pinfunction "OUT_1") (pintype "output"))
      (node (ref "RN18") (pin "5") (pinfunction "2_5") (pintype "passive"))
      (node (ref "U12") (pin "11") (pinfunction "AIN0/IEXC_11") (pintype "bidirectional"))
    )
    (net (code "154") (name "OUT_DMS_12") (class "Default")
      (node (ref "IC10") (pin "7") (pinfunction "OUT_7") (pintype "output"))
      (node (ref "RN18") (pin "6") (pinfunction "2_6") (pintype "passive"))
      (node (ref "U12") (pin "17") (pinfunction "AIN2/IEXC/GPIO2_17") (pintype "bidirectional"))
    )
    (net (code "155") (name "OUT_PT_1") (class "Default")
      (node (ref "IC4") (pin "1") (pinfunction "OUT_1") (pintype "output"))
      (node (ref "RN9") (pin "5") (pinfunction "2_5") (pintype "passive"))
      (node (ref "U9") (pin "62") (pinfunction "PB1_62") (pintype "bidirectional"))
    )
    (net (code "156") (name "OUT_PT_2") (class "Default")
      (node (ref "IC4") (pin "7") (pinfunction "OUT_7") (pintype "output"))
      (node (ref "RN9") (pin "6") (pinfunction "2_6") (pintype "passive"))
      (node (ref "U9") (pin "53") (pinfunction "PA4_53") (pintype "bidirectional"))
    )
    (net (code "157") (name "OUT_PT_3") (class "Default")
      (node (ref "IC4") (pin "8") (pinfunction "OUT_8") (pintype "output"))
      (node (ref "RN9") (pin "7") (pinfunction "2_7") (pintype "passive"))
      (node (ref "U9") (pin "61") (pinfunction "PB0_61") (pintype "bidirectional"))
    )
    (net (code "158") (name "OUT_PT_4_NC") (class "Default")
      (node (ref "IC4") (pin "14") (pinfunction "OUT_14") (pintype "output"))
      (node (ref "RN9") (pin "8") (pinfunction "2_8") (pintype "passive"))
    )
    (net (code "159") (name "PRD_ON") (class "Default")
      (node (ref "R9") (pin "1") (pinfunction "1_1") (pintype "passive"))
      (node (ref "U9") (pin "203") (pinfunction "PDR_ON_203") (pintype "bidirectional"))
    )
    (net (code "160") (name "SODS") (class "Default")
      (node (ref "IC6") (pin "2") (pinfunction "C1_2") (pintype "bidirectional"))
      (node (ref "X1") (pin "5") (pinfunction "F_5") (pintype "passive"))
      (node (ref "X2") (pin "3") (pinfunction "F_3") (pintype "passive"))
    )
    (net (code "161") (name "SODS_OPT") (class "Default")
      (node (ref "D8") (pin "C") (pinfunction "C_C") (pintype "passive"))
      (node (ref "IC6") (pin "8") (pinfunction "COL1_8") (pintype "input"))
      (node (ref "RN12") (pin "8") (pinfunction "2_8") (pintype "passive"))
      (node (ref "U9") (pin "206") (pinfunction "PI5_206") (pintype "bidirectional"))
    )
    (net (code "162") (name "SOE") (class "Default")
      (node (ref "IC6") (pin "4") (pinfunction "C2_4") (pintype "bidirectional"))
      (node (ref "X1") (pin "6") (pinfunction "F_6") (pintype "passive"))
      (node (ref "X2") (pin "4") (pinfunction "F_4") (pintype "passive"))
    )
    (net (code "163") (name "SOE_OPT") (class "Default")
      (node (ref "D9") (pin "C") (pinfunction "C_C") (pintype "passive"))
      (node (ref "IC6") (pin "6") (pinfunction "COL2_6") (pintype "input"))
      (node (ref "RN12") (pin "7") (pinfunction "2_7") (pintype "passive"))
      (node (ref "U9") (pin "207") (pinfunction "PI6_207") (pintype "bidirectional"))
    )
    (net (code "164") (name "SPI2_MISO") (class "Default")
      (node (ref "U8") (pin "8") (pinfunction "SO_8") (pintype "bidirectional"))
      (node (ref "U9") (pin "106") (pinfunction "PB14_106") (pintype "bidirectional"))
    )
    (net (code "165") (name "SPI2_MOSI") (class "Default")
      (node (ref "U8") (pin "15") (pinfunction "SI_15") (pintype "bidirectional"))
      (node (ref "U9") (pin "107") (pinfunction "PB15_107") (pintype "bidirectional"))
    )
    (net (code "166") (name "SPI2_SCK") (class "Default")
      (node (ref "U8") (pin "16") (pinfunction "SCK_16") (pintype "bidirectional"))
      (node (ref "U9") (pin "105") (pinfunction "PB13_105") (pintype "bidirectional"))
    )
    (net (code "167") (name "SPI3_CS") (class "Default")
      (node (ref "U4") (pin "24") (pinfunction "~{CS}_24") (pintype "bidirectional"))
      (node (ref "U9") (pin "66") (pinfunction "PJ1_66") (pintype "bidirectional"))
    )
    (net (code "168") (name "SPI3_CS2") (class "Default")
      (node (ref "U11") (pin "24") (pinfunction "~{CS}_24") (pintype "bidirectional"))
      (node (ref "U9") (pin "18") (pinfunction "PF2_18") (pintype "bidirectional"))
    )
    (net (code "169") (name "SPI3_MISO") (class "Default")
      (node (ref "U11") (pin "26") (pinfunction "DOUT/~{DRDY}_26") (pintype "bidirectional"))
      (node (ref "U4") (pin "26") (pinfunction "DOUT/~{DRDY}_26") (pintype "bidirectional"))
      (node (ref "U9") (pin "162") (pinfunction "PC11_162") (pintype "bidirectional"))
    )
    (net (code "170") (name "SPI3_MOSI") (class "Default")
      (node (ref "U11") (pin "27") (pinfunction "DIN_27") (pintype "bidirectional"))
      (node (ref "U4") (pin "27") (pinfunction "DIN_27") (pintype "bidirectional"))
      (node (ref "U9") (pin "63") (pinfunction "PB2_63") (pintype "bidirectional"))
    )
    (net (code "171") (name "SPI3_SCK") (class "Default")
      (node (ref "U11") (pin "28") (pinfunction "SCLK_28") (pintype "bidirectional"))
      (node (ref "U4") (pin "28") (pinfunction "SCLK_28") (pintype "bidirectional"))
      (node (ref "U9") (pin "161") (pinfunction "PC10_161") (pintype "bidirectional"))
    )
    (net (code "172") (name "SPI4_CS") (class "Default")
      (node (ref "U3") (pin "24") (pinfunction "~{CS}_24") (pintype "bidirectional"))
      (node (ref "U9") (pin "48") (pinfunction "PH4_48") (pintype "bidirectional"))
    )
    (net (code "173") (name "SPI4_CS2") (class "Default")
      (node (ref "U10") (pin "24") (pinfunction "~{CS}_24") (pintype "bidirectional"))
      (node (ref "U9") (pin "19") (pinfunction "PI12_19") (pintype "bidirectional"))
    )
    (net (code "174") (name "SPI4_MISO") (class "Default")
      (node (ref "U10") (pin "26") (pinfunction "DOUT/~{DRDY}_26") (pintype "bidirectional"))
      (node (ref "U3") (pin "26") (pinfunction "DOUT/~{DRDY}_26") (pintype "bidirectional"))
      (node (ref "U9") (pin "4") (pinfunction "PE5_4") (pintype "bidirectional"))
    )
    (net (code "175") (name "SPI4_MOSI") (class "Default")
      (node (ref "U10") (pin "27") (pinfunction "DIN_27") (pintype "bidirectional"))
      (node (ref "U3") (pin "27") (pinfunction "DIN_27") (pintype "bidirectional"))
      (node (ref "U9") (pin "5") (pinfunction "PE6_5") (pintype "bidirectional"))
    )
    (net (code "176") (name "SPI4_SCK") (class "Default")
      (node (ref "U10") (pin "28") (pinfunction "SCLK_28") (pintype "bidirectional"))
      (node (ref "U3") (pin "28") (pinfunction "SCLK_28") (pintype "bidirectional"))
      (node (ref "U9") (pin "1") (pinfunction "PE2_1") (pintype "bidirectional"))
    )
    (net (code "177") (name "SPI5_CS") (class "Default")
      (node (ref "U5") (pin "24") (pinfunction "~{CS}_24") (pintype "bidirectional"))
      (node (ref "U9") (pin "74") (pinfunction "PF13_74") (pintype "bidirectional"))
    )
    (net (code "178") (name "SPI5_CS2") (class "Default")
      (node (ref "U12") (pin "24") (pinfunction "~{CS}_24") (pintype "bidirectional"))
      (node (ref "U9") (pin "20") (pinfunction "PI13_20") (pintype "bidirectional"))
    )
    (net (code "179") (name "SPI5_MISO") (class "Default")
      (node (ref "U12") (pin "26") (pinfunction "DOUT/~{DRDY}_26") (pintype "bidirectional"))
      (node (ref "U5") (pin "26") (pinfunction "DOUT/~{DRDY}_26") (pintype "bidirectional"))
      (node (ref "U9") (pin "29") (pinfunction "PF8_29") (pintype "bidirectional"))
    )
    (net (code "180") (name "SPI5_MOSI") (class "Default")
      (node (ref "U12") (pin "27") (pinfunction "DIN_27") (pintype "bidirectional"))
      (node (ref "U5") (pin "27") (pinfunction "DIN_27") (pintype "bidirectional"))
      (node (ref "U9") (pin "70") (pinfunction "PF11_70") (pintype "bidirectional"))
    )
    (net (code "181") (name "SPI5_SCK") (class "Default")
      (node (ref "U12") (pin "28") (pinfunction "SCLK_28") (pintype "bidirectional"))
      (node (ref "U5") (pin "28") (pinfunction "SCLK_28") (pintype "bidirectional"))
      (node (ref "U9") (pin "28") (pinfunction "PF7_28") (pintype "bidirectional"))
    )
    (net (code "182") (name "SPI6_MISO") (class "Default")
      (node (ref "U7") (pin "8") (pinfunction "SO_8") (pintype "bidirectional"))
      (node (ref "U9") (pin "55") (pinfunction "PA6_55") (pintype "bidirectional"))
    )
    (net (code "183") (name "SPI6_MOSI") (class "Default")
      (node (ref "U7") (pin "15") (pinfunction "SI_15") (pintype "bidirectional"))
      (node (ref "U9") (pin "56") (pinfunction "PA7_56") (pintype "bidirectional"))
    )
    (net (code "184") (name "SPI6_SCK") (class "Default")
      (node (ref "U7") (pin "16") (pinfunction "SCK_16") (pintype "bidirectional"))
      (node (ref "U9") (pin "54") (pinfunction "PA5_54") (pintype "bidirectional"))
    )
    (net (code "185") (name "TCK") (class "Default")
      (node (ref "U9") (pin "159") (pinfunction "PA14_159") (pintype "bidirectional"))
      (node (ref "X_PROG") (pin "9") (pinfunction "9_9") (pintype "passive"))
    )
    (net (code "186") (name "TDI") (class "Default")
      (node (ref "U9") (pin "160") (pinfunction "PA15_160") (pintype "bidirectional"))
      (node (ref "X_PROG") (pin "5") (pinfunction "5_5") (pintype "passive"))
    )
    (net (code "187") (name "TDO") (class "Default")
      (node (ref "U9") (pin "192") (pinfunction "PB3_192") (pintype "bidirectional"))
      (node (ref "X_PROG") (pin "13") (pinfunction "13_13") (pintype "passive"))
    )
    (net (code "188") (name "TMS") (class "Default")
      (node (ref "U9") (pin "147") (pinfunction "PA13_147") (pintype "bidirectional"))
      (node (ref "X_PROG") (pin "7") (pinfunction "7_7") (pintype "passive"))
    )
    (net (code "189") (name "TRST") (class "Default")
      (node (ref "JP1") (pin "2") (pinfunction "2_2") (pintype "passive"))
      (node (ref "U9") (pin "193") (pinfunction "PB4_193") (pintype "bidirectional"))
      (node (ref "X_PROG") (pin "3") (pinfunction "3_3") (pintype "passive"))
    )
    (net (code "190") (name "unconnected-(IC1-RMT_ON_OFF-Pad6)") (class "Default")
      (node (ref "IC1") (pin "6") (pinfunction "RMT_ON_OFF_6") (pintype "input"))
    )
    (net (code "191") (name "unconnected-(IC1-TRIM-Pad4)") (class "Default")
      (node (ref "IC1") (pin "4") (pinfunction "TRIM_4") (pintype "input"))
    )
    (net (code "192") (name "unconnected-(IC7-C2-Pad4)") (class "Default")
      (node (ref "IC7") (pin "4") (pinfunction "C2_4") (pintype "bidirectional"))
    )
    (net (code "193") (name "unconnected-(IC10C-+IN-Pad10)") (class "Default")
      (node (ref "IC10") (pin "10") (pinfunction "+IN_10") (pintype "input"))
    )
    (net (code "194") (name "unconnected-(IC10C--IN-Pad9)") (class "Default")
      (node (ref "IC10") (pin "9") (pinfunction "-IN_9") (pintype "input"))
    )
    (net (code "195") (name "unconnected-(IC10C-OUT-Pad8)") (class "Default")
      (node (ref "IC10") (pin "8") (pinfunction "OUT_8") (pintype "output"))
    )
    (net (code "196") (name "unconnected-(IC10D-+IN-Pad12)") (class "Default")
      (node (ref "IC10") (pin "12") (pinfunction "+IN_12") (pintype "input"))
    )
    (net (code "197") (name "unconnected-(IC10D--IN-Pad13)") (class "Default")
      (node (ref "IC10") (pin "13") (pinfunction "-IN_13") (pintype "input"))
    )
    (net (code "198") (name "unconnected-(IC10D-OUT-Pad14)") (class "Default")
      (node (ref "IC10") (pin "14") (pinfunction "OUT_14") (pintype "output"))
    )
    (net (code "199") (name "unconnected-(IC13-CTS-Pad9)") (class "Default")
      (node (ref "IC13") (pin "9") (pinfunction "CTS_9") (pintype "bidirectional"))
    )
    (net (code "200") (name "unconnected-(IC13-DCD-Pad12)") (class "Default")
      (node (ref "IC13") (pin "12") (pinfunction "DCD_12") (pintype "bidirectional"))
    )
    (net (code "201") (name "unconnected-(IC13-DSR-Pad10)") (class "Default")
      (node (ref "IC13") (pin "10") (pinfunction "DSR_10") (pintype "bidirectional"))
    )
    (net (code "202") (name "unconnected-(IC13-DTR-Pad13)") (class "Default")
      (node (ref "IC13") (pin "13") (pinfunction "DTR_13") (pintype "bidirectional"))
    )
    (net (code "203") (name "unconnected-(IC13-RI-Pad11)") (class "Default")
      (node (ref "IC13") (pin "11") (pinfunction "RI_11") (pintype "bidirectional"))
    )
    (net (code "204") (name "unconnected-(IC13-RS232-Pad15)") (class "Default")
      (node (ref "IC13") (pin "15") (pinfunction "RS232_15") (pintype "bidirectional"))
    )
    (net (code "205") (name "unconnected-(IC13-RTS-Pad14)") (class "Default")
      (node (ref "IC13") (pin "14") (pinfunction "RTS_14") (pintype "bidirectional"))
    )
    (net (code "206") (name "unconnected-(IC13-V3-Pad4)") (class "Default")
      (node (ref "IC13") (pin "4") (pinfunction "V3_4") (pintype "bidirectional"))
    )
    (net (code "207") (name "unconnected-(RN18-Pad1)") (class "Default")
      (node (ref "RN18") (pin "1") (pinfunction "1_1") (pintype "passive"))
    )
    (net (code "208") (name "unconnected-(RN18A-2-Pad8)") (class "Default")
      (node (ref "RN18") (pin "8") (pinfunction "2_8") (pintype "passive"))
    )
    (net (code "209") (name "unconnected-(RN18B-1-Pad2)") (class "Default")
      (node (ref "RN18") (pin "2") (pinfunction "1_2") (pintype "passive"))
    )
    (net (code "210") (name "unconnected-(RN18B-2-Pad7)") (class "Default")
      (node (ref "RN18") (pin "7") (pinfunction "2_7") (pintype "passive"))
    )
    (net (code "211") (name "unconnected-(U3-AIN1{slash}IEXC-Pad12)") (class "Default")
      (node (ref "U3") (pin "12") (pinfunction "AIN1/IEXC_12") (pintype "bidirectional"))
    )
    (net (code "212") (name "unconnected-(U3-AIN3{slash}IEXC{slash}GPIO3-Pad18)") (class "Default")
      (node (ref "U3") (pin "18") (pinfunction "AIN3/IEXC/GPIO3_18") (pintype "bidirectional"))
    )
    (net (code "213") (name "unconnected-(U3-AIN4{slash}IECG{slash}GPIO4-Pad13)") (class "Default")
      (node (ref "U3") (pin "13") (pinfunction "AIN4/IECG/GPIO4_13") (pintype "bidirectional"))
    )
    (net (code "214") (name "unconnected-(U3-AIN5{slash}IEXC{slash}GPIO5-Pad14)") (class "Default")
      (node (ref "U3") (pin "14") (pinfunction "AIN5/IEXC/GPIO5_14") (pintype "bidirectional"))
    )
    (net (code "215") (name "unconnected-(U3-AIN6{slash}IEXC{slash}GPIO6-Pad15)") (class "Default")
      (node (ref "U3") (pin "15") (pinfunction "AIN6/IEXC/GPIO6_15") (pintype "bidirectional"))
    )
    (net (code "216") (name "unconnected-(U3-AIN7{slash}IEXC{slash}GPIO7-Pad16)") (class "Default")
      (node (ref "U3") (pin "16") (pinfunction "AIN7/IEXC/GPIO7_16") (pintype "bidirectional"))
    )
    (net (code "217") (name "unconnected-(U3-IEXC1-Pad20)") (class "Default")
      (node (ref "U3") (pin "20") (pinfunction "IEXC1_20") (pintype "bidirectional"))
    )
    (net (code "218") (name "unconnected-(U3-IEXC2-Pad19)") (class "Default")
      (node (ref "U3") (pin "19") (pinfunction "IEXC2_19") (pintype "bidirectional"))
    )
    (net (code "219") (name "unconnected-(U3-REFN0{slash}GPIO1-Pad6)") (class "Default")
      (node (ref "U3") (pin "6") (pinfunction "REFN0/GPIO1_6") (pintype "bidirectional"))
    )
    (net (code "220") (name "unconnected-(U3-REFN1-Pad8)") (class "Default")
      (node (ref "U3") (pin "8") (pinfunction "REFN1_8") (pintype "bidirectional"))
    )
    (net (code "221") (name "unconnected-(U3-REFP0{slash}GPIO0-Pad5)") (class "Default")
      (node (ref "U3") (pin "5") (pinfunction "REFP0/GPIO0_5") (pintype "bidirectional"))
    )
    (net (code "222") (name "unconnected-(U3-REFP1-Pad7)") (class "Default")
      (node (ref "U3") (pin "7") (pinfunction "REFP1_7") (pintype "bidirectional"))
    )
    (net (code "223") (name "unconnected-(U4-AIN1{slash}IEXC-Pad12)") (class "Default")
      (node (ref "U4") (pin "12") (pinfunction "AIN1/IEXC_12") (pintype "bidirectional"))
    )
    (net (code "224") (name "unconnected-(U4-AIN3{slash}IEXC{slash}GPIO3-Pad18)") (class "Default")
      (node (ref "U4") (pin "18") (pinfunction "AIN3/IEXC/GPIO3_18") (pintype "bidirectional"))
    )
    (net (code "225") (name "unconnected-(U4-AIN4{slash}IECG{slash}GPIO4-Pad13)") (class "Default")
      (node (ref "U4") (pin "13") (pinfunction "AIN4/IECG/GPIO4_13") (pintype "bidirectional"))
    )
    (net (code "226") (name "unconnected-(U4-AIN5{slash}IEXC{slash}GPIO5-Pad14)") (class "Default")
      (node (ref "U4") (pin "14") (pinfunction "AIN5/IEXC/GPIO5_14") (pintype "bidirectional"))
    )
    (net (code "227") (name "unconnected-(U4-AIN6{slash}IEXC{slash}GPIO6-Pad15)") (class "Default")
      (node (ref "U4") (pin "15") (pinfunction "AIN6/IEXC/GPIO6_15") (pintype "bidirectional"))
    )
    (net (code "228") (name "unconnected-(U4-AIN7{slash}IEXC{slash}GPIO7-Pad16)") (class "Default")
      (node (ref "U4") (pin "16") (pinfunction "AIN7/IEXC/GPIO7_16") (pintype "bidirectional"))
    )
    (net (code "229") (name "unconnected-(U4-IEXC1-Pad20)") (class "Default")
      (node (ref "U4") (pin "20") (pinfunction "IEXC1_20") (pintype "bidirectional"))
    )
    (net (code "230") (name "unconnected-(U4-IEXC2-Pad19)") (class "Default")
      (node (ref "U4") (pin "19") (pinfunction "IEXC2_19") (pintype "bidirectional"))
    )
    (net (code "231") (name "unconnected-(U4-REFN0{slash}GPIO1-Pad6)") (class "Default")
      (node (ref "U4") (pin "6") (pinfunction "REFN0/GPIO1_6") (pintype "bidirectional"))
    )
    (net (code "232") (name "unconnected-(U4-REFN1-Pad8)") (class "Default")
      (node (ref "U4") (pin "8") (pinfunction "REFN1_8") (pintype "bidirectional"))
    )
    (net (code "233") (name "unconnected-(U4-REFP0{slash}GPIO0-Pad5)") (class "Default")
      (node (ref "U4") (pin "5") (pinfunction "REFP0/GPIO0_5") (pintype "bidirectional"))
    )
    (net (code "234") (name "unconnected-(U4-REFP1-Pad7)") (class "Default")
      (node (ref "U4") (pin "7") (pinfunction "REFP1_7") (pintype "bidirectional"))
    )
    (net (code "235") (name "unconnected-(U5-AIN1{slash}IEXC-Pad12)") (class "Default")
      (node (ref "U5") (pin "12") (pinfunction "AIN1/IEXC_12") (pintype "bidirectional"))
    )
    (net (code "236") (name "unconnected-(U5-AIN3{slash}IEXC{slash}GPIO3-Pad18)") (class "Default")
      (node (ref "U5") (pin "18") (pinfunction "AIN3/IEXC/GPIO3_18") (pintype "bidirectional"))
    )
    (net (code "237") (name "unconnected-(U5-AIN4{slash}IECG{slash}GPIO4-Pad13)") (class "Default")
      (node (ref "U5") (pin "13") (pinfunction "AIN4/IECG/GPIO4_13") (pintype "bidirectional"))
    )
    (net (code "238") (name "unconnected-(U5-AIN5{slash}IEXC{slash}GPIO5-Pad14)") (class "Default")
      (node (ref "U5") (pin "14") (pinfunction "AIN5/IEXC/GPIO5_14") (pintype "bidirectional"))
    )
    (net (code "239") (name "unconnected-(U5-AIN6{slash}IEXC{slash}GPIO6-Pad15)") (class "Default")
      (node (ref "U5") (pin "15") (pinfunction "AIN6/IEXC/GPIO6_15") (pintype "bidirectional"))
    )
    (net (code "240") (name "unconnected-(U5-AIN7{slash}IEXC{slash}GPIO7-Pad16)") (class "Default")
      (node (ref "U5") (pin "16") (pinfunction "AIN7/IEXC/GPIO7_16") (pintype "bidirectional"))
    )
    (net (code "241") (name "unconnected-(U5-IEXC1-Pad20)") (class "Default")
      (node (ref "U5") (pin "20") (pinfunction "IEXC1_20") (pintype "bidirectional"))
    )
    (net (code "242") (name "unconnected-(U5-IEXC2-Pad19)") (class "Default")
      (node (ref "U5") (pin "19") (pinfunction "IEXC2_19") (pintype "bidirectional"))
    )
    (net (code "243") (name "unconnected-(U5-REFN0{slash}GPIO1-Pad6)") (class "Default")
      (node (ref "U5") (pin "6") (pinfunction "REFN0/GPIO1_6") (pintype "bidirectional"))
    )
    (net (code "244") (name "unconnected-(U5-REFN1-Pad8)") (class "Default")
      (node (ref "U5") (pin "8") (pinfunction "REFN1_8") (pintype "bidirectional"))
    )
    (net (code "245") (name "unconnected-(U5-REFP0{slash}GPIO0-Pad5)") (class "Default")
      (node (ref "U5") (pin "5") (pinfunction "REFP0/GPIO0_5") (pintype "bidirectional"))
    )
    (net (code "246") (name "unconnected-(U5-REFP1-Pad7)") (class "Default")
      (node (ref "U5") (pin "7") (pinfunction "REFP1_7") (pintype "bidirectional"))
    )
    (net (code "247") (name "unconnected-(U9-DSI_CKN-Pad124)") (class "Default")
      (node (ref "U9") (pin "124") (pinfunction "DSI_CKN_124") (pintype "bidirectional"))
    )
    (net (code "248") (name "unconnected-(U9-DSI_CKP-Pad123)") (class "Default")
      (node (ref "U9") (pin "123") (pinfunction "DSI_CKP_123") (pintype "bidirectional"))
    )
    (net (code "249") (name "unconnected-(U9-DSI_D0N-Pad121)") (class "Default")
      (node (ref "U9") (pin "121") (pinfunction "DSI_D0N_121") (pintype "bidirectional"))
    )
    (net (code "250") (name "unconnected-(U9-DSI_D0P-Pad120)") (class "Default")
      (node (ref "U9") (pin "120") (pinfunction "DSI_D0P_120") (pintype "bidirectional"))
    )
    (net (code "251") (name "unconnected-(U9-DSI_D1N-Pad127)") (class "Default")
      (node (ref "U9") (pin "127") (pinfunction "DSI_D1N_127") (pintype "bidirectional"))
    )
    (net (code "252") (name "unconnected-(U9-DSI_D1P-Pad126)") (class "Default")
      (node (ref "U9") (pin "126") (pinfunction "DSI_D1P_126") (pintype "bidirectional"))
    )
    (net (code "253") (name "unconnected-(U9-PA8-Pad142)") (class "Default")
      (node (ref "U9") (pin "142") (pinfunction "PA8_142") (pintype "bidirectional"))
    )
    (net (code "254") (name "unconnected-(U9-PA9-Pad143)") (class "Default")
      (node (ref "U9") (pin "143") (pinfunction "PA9_143") (pintype "bidirectional"))
    )
    (net (code "255") (name "unconnected-(U9-PA10-Pad144)") (class "Default")
      (node (ref "U9") (pin "144") (pinfunction "PA10_144") (pintype "bidirectional"))
    )
    (net (code "256") (name "unconnected-(U9-PA11-Pad145)") (class "Default")
      (node (ref "U9") (pin "145") (pinfunction "PA11_145") (pintype "bidirectional"))
    )
    (net (code "257") (name "unconnected-(U9-PA12-Pad146)") (class "Default")
      (node (ref "U9") (pin "146") (pinfunction "PA12_146") (pintype "bidirectional"))
    )
    (net (code "258") (name "unconnected-(U9-PB5-Pad194)") (class "Default")
      (node (ref "U9") (pin "194") (pinfunction "PB5_194") (pintype "bidirectional"))
    )
    (net (code "259") (name "unconnected-(U9-PB6-Pad195)") (class "Default")
      (node (ref "U9") (pin "195") (pinfunction "PB6_195") (pintype "bidirectional"))
    )
    (net (code "260") (name "unconnected-(U9-PB7-Pad196)") (class "Default")
      (node (ref "U9") (pin "196") (pinfunction "PB7_196") (pintype "bidirectional"))
    )
    (net (code "261") (name "unconnected-(U9-PB8-Pad198)") (class "Default")
      (node (ref "U9") (pin "198") (pinfunction "PB8_198") (pintype "bidirectional"))
    )
    (net (code "262") (name "unconnected-(U9-PB9-Pad199)") (class "Default")
      (node (ref "U9") (pin "199") (pinfunction "PB9_199") (pintype "bidirectional"))
    )
    (net (code "263") (name "unconnected-(U9-PB10-Pad90)") (class "Default")
      (node (ref "U9") (pin "90") (pinfunction "PB10_90") (pintype "bidirectional"))
    )
    (net (code "264") (name "unconnected-(U9-PB11-Pad91)") (class "Default")
      (node (ref "U9") (pin "91") (pinfunction "PB11_91") (pintype "bidirectional"))
    )
    (net (code "265") (name "unconnected-(U9-PC1-Pad36)") (class "Default")
      (node (ref "U9") (pin "36") (pinfunction "PC1_36") (pintype "bidirectional"))
    )
    (net (code "266") (name "unconnected-(U9-PC4-Pad57)") (class "Default")
      (node (ref "U9") (pin "57") (pinfunction "PC4_57") (pintype "bidirectional"))
    )
    (net (code "267") (name "unconnected-(U9-PC5-Pad58)") (class "Default")
      (node (ref "U9") (pin "58") (pinfunction "PC5_58") (pintype "bidirectional"))
    )
    (net (code "268") (name "unconnected-(U9-PC6-Pad138)") (class "Default")
      (node (ref "U9") (pin "138") (pinfunction "PC6_138") (pintype "bidirectional"))
    )
    (net (code "269") (name "unconnected-(U9-PC7-Pad139)") (class "Default")
      (node (ref "U9") (pin "139") (pinfunction "PC7_139") (pintype "bidirectional"))
    )
    (net (code "270") (name "unconnected-(U9-PC8-Pad140)") (class "Default")
      (node (ref "U9") (pin "140") (pinfunction "PC8_140") (pintype "bidirectional"))
    )
    (net (code "271") (name "unconnected-(U9-PC9-Pad141)") (class "Default")
      (node (ref "U9") (pin "141") (pinfunction "PC9_141") (pintype "bidirectional"))
    )
    (net (code "272") (name "unconnected-(U9-PC13-Pad8)") (class "Default")
      (node (ref "U9") (pin "8") (pinfunction "PC13_8") (pintype "bidirectional"))
    )
    (net (code "273") (name "unconnected-(U9-PC14-Pad9)") (class "Default")
      (node (ref "U9") (pin "9") (pinfunction "PC14_9") (pintype "bidirectional"))
    )
    (net (code "274") (name "unconnected-(U9-PC15-Pad10)") (class "Default")
      (node (ref "U9") (pin "10") (pinfunction "PC15_10") (pintype "bidirectional"))
    )
    (net (code "275") (name "unconnected-(U9-PD0-Pad164)") (class "Default")
      (node (ref "U9") (pin "164") (pinfunction "PD0_164") (pintype "bidirectional"))
    )
    (net (code "276") (name "unconnected-(U9-PD1-Pad165)") (class "Default")
      (node (ref "U9") (pin "165") (pinfunction "PD1_165") (pintype "bidirectional"))
    )
    (net (code "277") (name "unconnected-(U9-PD3-Pad167)") (class "Default")
      (node (ref "U9") (pin "167") (pinfunction "PD3_167") (pintype "bidirectional"))
    )
    (net (code "278") (name "unconnected-(U9-PD4-Pad168)") (class "Default")
      (node (ref "U9") (pin "168") (pinfunction "PD4_168") (pintype "bidirectional"))
    )
    (net (code "279") (name "unconnected-(U9-PD5-Pad169)") (class "Default")
      (node (ref "U9") (pin "169") (pinfunction "PD5_169") (pintype "bidirectional"))
    )
    (net (code "280") (name "unconnected-(U9-PD6-Pad172)") (class "Default")
      (node (ref "U9") (pin "172") (pinfunction "PD6_172") (pintype "bidirectional"))
    )
    (net (code "281") (name "unconnected-(U9-PD7-Pad173)") (class "Default")
      (node (ref "U9") (pin "173") (pinfunction "PD7_173") (pintype "bidirectional"))
    )
    (net (code "282") (name "unconnected-(U9-PD13-Pad113)") (class "Default")
      (node (ref "U9") (pin "113") (pinfunction "PD13_113") (pintype "bidirectional"))
    )
    (net (code "283") (name "unconnected-(U9-PD14-Pad116)") (class "Default")
      (node (ref "U9") (pin "116") (pinfunction "PD14_116") (pintype "bidirectional"))
    )
    (net (code "284") (name "unconnected-(U9-PD15-Pad117)") (class "Default")
      (node (ref "U9") (pin "117") (pinfunction "PD15_117") (pintype "bidirectional"))
    )
    (net (code "285") (name "unconnected-(U9-PE3-Pad2)") (class "Default")
      (node (ref "U9") (pin "2") (pinfunction "PE3_2") (pintype "bidirectional"))
    )
    (net (code "286") (name "unconnected-(U9-PE4-Pad3)") (class "Default")
      (node (ref "U9") (pin "3") (pinfunction "PE4_3") (pintype "bidirectional"))
    )
    (net (code "287") (name "unconnected-(U9-PE7-Pad79)") (class "Default")
      (node (ref "U9") (pin "79") (pinfunction "PE7_79") (pintype "bidirectional"))
    )
    (net (code "288") (name "unconnected-(U9-PE8-Pad80)") (class "Default")
      (node (ref "U9") (pin "80") (pinfunction "PE8_80") (pintype "bidirectional"))
    )
    (net (code "289") (name "unconnected-(U9-PE9-Pad81)") (class "Default")
      (node (ref "U9") (pin "81") (pinfunction "PE9_81") (pintype "bidirectional"))
    )
    (net (code "290") (name "unconnected-(U9-PE10-Pad84)") (class "Default")
      (node (ref "U9") (pin "84") (pinfunction "PE10_84") (pintype "bidirectional"))
    )
    (net (code "291") (name "unconnected-(U9-PE11-Pad85)") (class "Default")
      (node (ref "U9") (pin "85") (pinfunction "PE11_85") (pintype "bidirectional"))
    )
    (net (code "292") (name "unconnected-(U9-PE12-Pad86)") (class "Default")
      (node (ref "U9") (pin "86") (pinfunction "PE12_86") (pintype "bidirectional"))
    )
    (net (code "293") (name "unconnected-(U9-PE13-Pad87)") (class "Default")
      (node (ref "U9") (pin "87") (pinfunction "PE13_87") (pintype "bidirectional"))
    )
    (net (code "294") (name "unconnected-(U9-PE14-Pad88)") (class "Default")
      (node (ref "U9") (pin "88") (pinfunction "PE14_88") (pintype "bidirectional"))
    )
    (net (code "295") (name "unconnected-(U9-PE15-Pad89)") (class "Default")
      (node (ref "U9") (pin "89") (pinfunction "PE15_89") (pintype "bidirectional"))
    )
    (net (code "296") (name "unconnected-(U9-PF0-Pad16)") (class "Default")
      (node (ref "U9") (pin "16") (pinfunction "PF0_16") (pintype "bidirectional"))
    )
    (net (code "297") (name "unconnected-(U9-PF1-Pad17)") (class "Default")
      (node (ref "U9") (pin "17") (pinfunction "PF1_17") (pintype "bidirectional"))
    )
    (net (code "298") (name "unconnected-(U9-PF6-Pad27)") (class "Default")
      (node (ref "U9") (pin "27") (pinfunction "PF6_27") (pintype "bidirectional"))
    )
    (net (code "299") (name "unconnected-(U9-PG0-Pad77)") (class "Default")
      (node (ref "U9") (pin "77") (pinfunction "PG0_77") (pintype "bidirectional"))
    )
    (net (code "300") (name "unconnected-(U9-PG1-Pad78)") (class "Default")
      (node (ref "U9") (pin "78") (pinfunction "PG1_78") (pintype "bidirectional"))
    )
    (net (code "301") (name "unconnected-(U9-PG3-Pad130)") (class "Default")
      (node (ref "U9") (pin "130") (pinfunction "PG3_130") (pintype "bidirectional"))
    )
    (net (code "302") (name "unconnected-(U9-PG4-Pad131)") (class "Default")
      (node (ref "U9") (pin "131") (pinfunction "PG4_131") (pintype "bidirectional"))
    )
    (net (code "303") (name "unconnected-(U9-PG5-Pad132)") (class "Default")
      (node (ref "U9") (pin "132") (pinfunction "PG5_132") (pintype "bidirectional"))
    )
    (net (code "304") (name "unconnected-(U9-PG6-Pad133)") (class "Default")
      (node (ref "U9") (pin "133") (pinfunction "PG6_133") (pintype "bidirectional"))
    )
    (net (code "305") (name "unconnected-(U9-PG7-Pad134)") (class "Default")
      (node (ref "U9") (pin "134") (pinfunction "PG7_134") (pintype "bidirectional"))
    )
    (net (code "306") (name "unconnected-(U9-PG8-Pad135)") (class "Default")
      (node (ref "U9") (pin "135") (pinfunction "PG8_135") (pintype "bidirectional"))
    )
    (net (code "307") (name "unconnected-(U9-PG9-Pad178)") (class "Default")
      (node (ref "U9") (pin "178") (pinfunction "PG9_178") (pintype "bidirectional"))
    )
    (net (code "308") (name "unconnected-(U9-PG10-Pad179)") (class "Default")
      (node (ref "U9") (pin "179") (pinfunction "PG10_179") (pintype "bidirectional"))
    )
    (net (code "309") (name "unconnected-(U9-PG11-Pad180)") (class "Default")
      (node (ref "U9") (pin "180") (pinfunction "PG11_180") (pintype "bidirectional"))
    )
    (net (code "310") (name "unconnected-(U9-PG12-Pad181)") (class "Default")
      (node (ref "U9") (pin "181") (pinfunction "PG12_181") (pintype "bidirectional"))
    )
    (net (code "311") (name "unconnected-(U9-PG13-Pad182)") (class "Default")
      (node (ref "U9") (pin "182") (pinfunction "PG13_182") (pintype "bidirectional"))
    )
    (net (code "312") (name "unconnected-(U9-PG14-Pad183)") (class "Default")
      (node (ref "U9") (pin "183") (pinfunction "PG14_183") (pintype "bidirectional"))
    )
    (net (code "313") (name "unconnected-(U9-PG15-Pad191)") (class "Default")
      (node (ref "U9") (pin "191") (pinfunction "PG15_191") (pintype "bidirectional"))
    )
    (net (code "314") (name "unconnected-(U9-PH2-Pad46)") (class "Default")
      (node (ref "U9") (pin "46") (pinfunction "PH2_46") (pintype "bidirectional"))
    )
    (net (code "315") (name "unconnected-(U9-PH6-Pad96)") (class "Default")
      (node (ref "U9") (pin "96") (pinfunction "PH6_96") (pintype "bidirectional"))
    )
    (net (code "316") (name "unconnected-(U9-PH7-Pad97)") (class "Default")
      (node (ref "U9") (pin "97") (pinfunction "PH7_97") (pintype "bidirectional"))
    )
    (net (code "317") (name "unconnected-(U9-PH8-Pad98)") (class "Default")
      (node (ref "U9") (pin "98") (pinfunction "PH8_98") (pintype "bidirectional"))
    )
    (net (code "318") (name "unconnected-(U9-PH13-Pad151)") (class "Default")
      (node (ref "U9") (pin "151") (pinfunction "PH13_151") (pintype "bidirectional"))
    )
    (net (code "319") (name "unconnected-(U9-PH14-Pad152)") (class "Default")
      (node (ref "U9") (pin "152") (pinfunction "PH14_152") (pintype "bidirectional"))
    )
    (net (code "320") (name "unconnected-(U9-PH15-Pad153)") (class "Default")
      (node (ref "U9") (pin "153") (pinfunction "PH15_153") (pintype "bidirectional"))
    )
    (net (code "321") (name "unconnected-(U9-PI0-Pad154)") (class "Default")
      (node (ref "U9") (pin "154") (pinfunction "PI0_154") (pintype "bidirectional"))
    )
    (net (code "322") (name "unconnected-(U9-PI1-Pad155)") (class "Default")
      (node (ref "U9") (pin "155") (pinfunction "PI1_155") (pintype "bidirectional"))
    )
    (net (code "323") (name "unconnected-(U9-PI2-Pad156)") (class "Default")
      (node (ref "U9") (pin "156") (pinfunction "PI2_156") (pintype "bidirectional"))
    )
    (net (code "324") (name "unconnected-(U9-PI3-Pad157)") (class "Default")
      (node (ref "U9") (pin "157") (pinfunction "PI3_157") (pintype "bidirectional"))
    )
    (net (code "325") (name "unconnected-(U9-PI4-Pad205)") (class "Default")
      (node (ref "U9") (pin "205") (pinfunction "PI4_205") (pintype "bidirectional"))
    )
    (net (code "326") (name "unconnected-(U9-PI8-Pad7)") (class "Default")
      (node (ref "U9") (pin "7") (pinfunction "PI8_7") (pintype "bidirectional"))
    )
    (net (code "327") (name "unconnected-(U9-PI10-Pad12)") (class "Default")
      (node (ref "U9") (pin "12") (pinfunction "PI10_12") (pintype "bidirectional"))
    )
    (net (code "328") (name "unconnected-(U9-PI11-Pad13)") (class "Default")
      (node (ref "U9") (pin "13") (pinfunction "PI11_13") (pintype "bidirectional"))
    )
    (net (code "329") (name "unconnected-(U9-PI15-Pad64)") (class "Default")
      (node (ref "U9") (pin "64") (pinfunction "PI15_64") (pintype "bidirectional"))
    )
    (net (code "330") (name "unconnected-(U9-PJ4-Pad69)") (class "Default")
      (node (ref "U9") (pin "69") (pinfunction "PJ4_69") (pintype "bidirectional"))
    )
    (net (code "331") (name "unconnected-(U9-PJ5-Pad95)") (class "Default")
      (node (ref "U9") (pin "95") (pinfunction "PJ5_95") (pintype "bidirectional"))
    )
    (net (code "332") (name "unconnected-(U9-PJ12-Pad174)") (class "Default")
      (node (ref "U9") (pin "174") (pinfunction "PJ12_174") (pintype "bidirectional"))
    )
    (net (code "333") (name "unconnected-(U9-PJ13-Pad175)") (class "Default")
      (node (ref "U9") (pin "175") (pinfunction "PJ13_175") (pintype "bidirectional"))
    )
    (net (code "334") (name "unconnected-(U9-PJ14-Pad176)") (class "Default")
      (node (ref "U9") (pin "176") (pinfunction "PJ14_176") (pintype "bidirectional"))
    )
    (net (code "335") (name "unconnected-(U9-PJ15-Pad177)") (class "Default")
      (node (ref "U9") (pin "177") (pinfunction "PJ15_177") (pintype "bidirectional"))
    )
    (net (code "336") (name "unconnected-(U9-PK3-Pad186)") (class "Default")
      (node (ref "U9") (pin "186") (pinfunction "PK3_186") (pintype "bidirectional"))
    )
    (net (code "337") (name "unconnected-(U9-PK4-Pad187)") (class "Default")
      (node (ref "U9") (pin "187") (pinfunction "PK4_187") (pintype "bidirectional"))
    )
    (net (code "338") (name "unconnected-(U9-PK5-Pad188)") (class "Default")
      (node (ref "U9") (pin "188") (pinfunction "PK5_188") (pintype "bidirectional"))
    )
    (net (code "339") (name "unconnected-(U9-PK6-Pad189)") (class "Default")
      (node (ref "U9") (pin "189") (pinfunction "PK6_189") (pintype "bidirectional"))
    )
    (net (code "340") (name "unconnected-(U9-PK7-Pad190)") (class "Default")
      (node (ref "U9") (pin "190") (pinfunction "PK7_190") (pintype "bidirectional"))
    )
    (net (code "341") (name "unconnected-(U10-AIN1{slash}IEXC-Pad12)") (class "Default")
      (node (ref "U10") (pin "12") (pinfunction "AIN1/IEXC_12") (pintype "bidirectional"))
    )
    (net (code "342") (name "unconnected-(U10-AIN3{slash}IEXC{slash}GPIO3-Pad18)") (class "Default")
      (node (ref "U10") (pin "18") (pinfunction "AIN3/IEXC/GPIO3_18") (pintype "bidirectional"))
    )
    (net (code "343") (name "unconnected-(U10-AIN4{slash}IECG{slash}GPIO4-Pad13)") (class "Default")
      (node (ref "U10") (pin "13") (pinfunction "AIN4/IECG/GPIO4_13") (pintype "bidirectional"))
    )
    (net (code "344") (name "unconnected-(U10-AIN5{slash}IEXC{slash}GPIO5-Pad14)") (class "Default")
      (node (ref "U10") (pin "14") (pinfunction "AIN5/IEXC/GPIO5_14") (pintype "bidirectional"))
    )
    (net (code "345") (name "unconnected-(U10-AIN6{slash}IEXC{slash}GPIO6-Pad15)") (class "Default")
      (node (ref "U10") (pin "15") (pinfunction "AIN6/IEXC/GPIO6_15") (pintype "bidirectional"))
    )
    (net (code "346") (name "unconnected-(U10-AIN7{slash}IEXC{slash}GPIO7-Pad16)") (class "Default")
      (node (ref "U10") (pin "16") (pinfunction "AIN7/IEXC/GPIO7_16") (pintype "bidirectional"))
    )
    (net (code "347") (name "unconnected-(U10-IEXC1-Pad20)") (class "Default")
      (node (ref "U10") (pin "20") (pinfunction "IEXC1_20") (pintype "bidirectional"))
    )
    (net (code "348") (name "unconnected-(U10-IEXC2-Pad19)") (class "Default")
      (node (ref "U10") (pin "19") (pinfunction "IEXC2_19") (pintype "bidirectional"))
    )
    (net (code "349") (name "unconnected-(U10-REFN0{slash}GPIO1-Pad6)") (class "Default")
      (node (ref "U10") (pin "6") (pinfunction "REFN0/GPIO1_6") (pintype "bidirectional"))
    )
    (net (code "350") (name "unconnected-(U10-REFN1-Pad8)") (class "Default")
      (node (ref "U10") (pin "8") (pinfunction "REFN1_8") (pintype "bidirectional"))
    )
    (net (code "351") (name "unconnected-(U10-REFP0{slash}GPIO0-Pad5)") (class "Default")
      (node (ref "U10") (pin "5") (pinfunction "REFP0/GPIO0_5") (pintype "bidirectional"))
    )
    (net (code "352") (name "unconnected-(U10-REFP1-Pad7)") (class "Default")
      (node (ref "U10") (pin "7") (pinfunction "REFP1_7") (pintype "bidirectional"))
    )
    (net (code "353") (name "unconnected-(U11-AIN1{slash}IEXC-Pad12)") (class "Default")
      (node (ref "U11") (pin "12") (pinfunction "AIN1/IEXC_12") (pintype "bidirectional"))
    )
    (net (code "354") (name "unconnected-(U11-AIN3{slash}IEXC{slash}GPIO3-Pad18)") (class "Default")
      (node (ref "U11") (pin "18") (pinfunction "AIN3/IEXC/GPIO3_18") (pintype "bidirectional"))
    )
    (net (code "355") (name "unconnected-(U11-AIN4{slash}IECG{slash}GPIO4-Pad13)") (class "Default")
      (node (ref "U11") (pin "13") (pinfunction "AIN4/IECG/GPIO4_13") (pintype "bidirectional"))
    )
    (net (code "356") (name "unconnected-(U11-AIN5{slash}IEXC{slash}GPIO5-Pad14)") (class "Default")
      (node (ref "U11") (pin "14") (pinfunction "AIN5/IEXC/GPIO5_14") (pintype "bidirectional"))
    )
    (net (code "357") (name "unconnected-(U11-AIN6{slash}IEXC{slash}GPIO6-Pad15)") (class "Default")
      (node (ref "U11") (pin "15") (pinfunction "AIN6/IEXC/GPIO6_15") (pintype "bidirectional"))
    )
    (net (code "358") (name "unconnected-(U11-AIN7{slash}IEXC{slash}GPIO7-Pad16)") (class "Default")
      (node (ref "U11") (pin "16") (pinfunction "AIN7/IEXC/GPIO7_16") (pintype "bidirectional"))
    )
    (net (code "359") (name "unconnected-(U11-IEXC1-Pad20)") (class "Default")
      (node (ref "U11") (pin "20") (pinfunction "IEXC1_20") (pintype "bidirectional"))
    )
    (net (code "360") (name "unconnected-(U11-IEXC2-Pad19)") (class "Default")
      (node (ref "U11") (pin "19") (pinfunction "IEXC2_19") (pintype "bidirectional"))
    )
    (net (code "361") (name "unconnected-(U11-REFN0{slash}GPIO1-Pad6)") (class "Default")
      (node (ref "U11") (pin "6") (pinfunction "REFN0/GPIO1_6") (pintype "bidirectional"))
    )
    (net (code "362") (name "unconnected-(U11-REFN1-Pad8)") (class "Default")
      (node (ref "U11") (pin "8") (pinfunction "REFN1_8") (pintype "bidirectional"))
    )
    (net (code "363") (name "unconnected-(U11-REFP0{slash}GPIO0-Pad5)") (class "Default")
      (node (ref "U11") (pin "5") (pinfunction "REFP0/GPIO0_5") (pintype "bidirectional"))
    )
    (net (code "364") (name "unconnected-(U11-REFP1-Pad7)") (class "Default")
      (node (ref "U11") (pin "7") (pinfunction "REFP1_7") (pintype "bidirectional"))
    )
    (net (code "365") (name "unconnected-(U12-AIN1{slash}IEXC-Pad12)") (class "Default")
      (node (ref "U12") (pin "12") (pinfunction "AIN1/IEXC_12") (pintype "bidirectional"))
    )
    (net (code "366") (name "unconnected-(U12-AIN3{slash}IEXC{slash}GPIO3-Pad18)") (class "Default")
      (node (ref "U12") (pin "18") (pinfunction "AIN3/IEXC/GPIO3_18") (pintype "bidirectional"))
    )
    (net (code "367") (name "unconnected-(U12-AIN4{slash}IECG{slash}GPIO4-Pad13)") (class "Default")
      (node (ref "U12") (pin "13") (pinfunction "AIN4/IECG/GPIO4_13") (pintype "bidirectional"))
    )
    (net (code "368") (name "unconnected-(U12-AIN5{slash}IEXC{slash}GPIO5-Pad14)") (class "Default")
      (node (ref "U12") (pin "14") (pinfunction "AIN5/IEXC/GPIO5_14") (pintype "bidirectional"))
    )
    (net (code "369") (name "unconnected-(U12-AIN6{slash}IEXC{slash}GPIO6-Pad15)") (class "Default")
      (node (ref "U12") (pin "15") (pinfunction "AIN6/IEXC/GPIO6_15") (pintype "bidirectional"))
    )
    (net (code "370") (name "unconnected-(U12-AIN7{slash}IEXC{slash}GPIO7-Pad16)") (class "Default")
      (node (ref "U12") (pin "16") (pinfunction "AIN7/IEXC/GPIO7_16") (pintype "bidirectional"))
    )
    (net (code "371") (name "unconnected-(U12-IEXC1-Pad20)") (class "Default")
      (node (ref "U12") (pin "20") (pinfunction "IEXC1_20") (pintype "bidirectional"))
    )
    (net (code "372") (name "unconnected-(U12-IEXC2-Pad19)") (class "Default")
      (node (ref "U12") (pin "19") (pinfunction "IEXC2_19") (pintype "bidirectional"))
    )
    (net (code "373") (name "unconnected-(U12-REFN0{slash}GPIO1-Pad6)") (class "Default")
      (node (ref "U12") (pin "6") (pinfunction "REFN0/GPIO1_6") (pintype "bidirectional"))
    )
    (net (code "374") (name "unconnected-(U12-REFN1-Pad8)") (class "Default")
      (node (ref "U12") (pin "8") (pinfunction "REFN1_8") (pintype "bidirectional"))
    )
    (net (code "375") (name "unconnected-(U12-REFP0{slash}GPIO0-Pad5)") (class "Default")
      (node (ref "U12") (pin "5") (pinfunction "REFP0/GPIO0_5") (pintype "bidirectional"))
    )
    (net (code "376") (name "unconnected-(U12-REFP1-Pad7)") (class "Default")
      (node (ref "U12") (pin "7") (pinfunction "REFP1_7") (pintype "bidirectional"))
    )
    (net (code "377") (name "unconnected-(X1B-F-Pad2)") (class "Default")
      (node (ref "X1") (pin "2") (pinfunction "F_2") (pintype "passive"))
    )
    (net (code "378") (name "unconnected-(X2B-F-Pad10)") (class "Default")
      (node (ref "X2") (pin "10") (pinfunction "F_10") (pintype "passive"))
    )
    (net (code "379") (name "unconnected-(X2C-F-Pad11)") (class "Default")
      (node (ref "X2") (pin "11") (pinfunction "F_11") (pintype "passive"))
    )
    (net (code "380") (name "unconnected-(X2D-F-Pad12)") (class "Default")
      (node (ref "X2") (pin "12") (pinfunction "F_12") (pintype "passive"))
    )
    (net (code "381") (name "unconnected-(X2H-F-Pad2)") (class "Default")
      (node (ref "X2") (pin "2") (pinfunction "F_2") (pintype "passive"))
    )
    (net (code "382") (name "unconnected-(X_PROG-Pad11)") (class "Default")
      (node (ref "X_PROG") (pin "11") (pinfunction "11_11") (pintype "passive"))
    )
    (net (code "383") (name "unconnected-(X_PROG-Pad12)") (class "Default")
      (node (ref "X_PROG") (pin "12") (pinfunction "12_12") (pintype "passive"))
    )
  )
)
